# AutoPad-R1-RevA.net
KiCad netlist of a schematic drawn in EAGLE
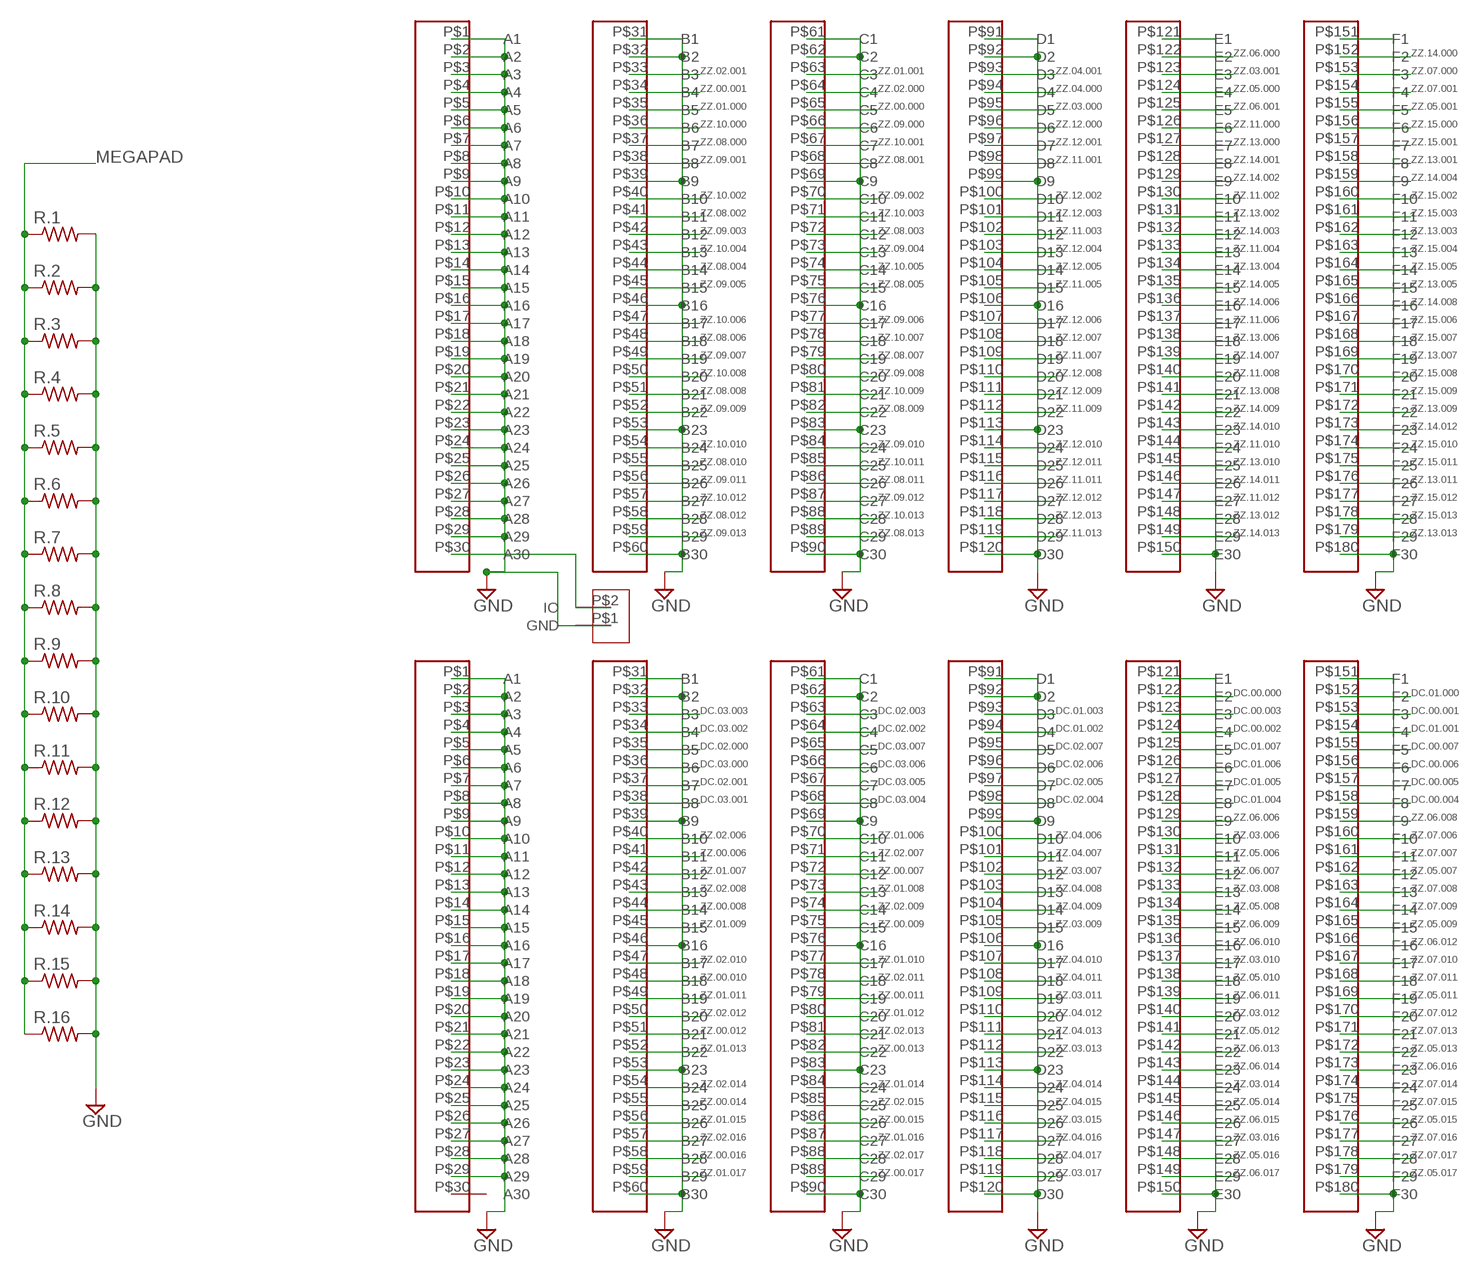
[diagram p0: schematic, sheet 1]
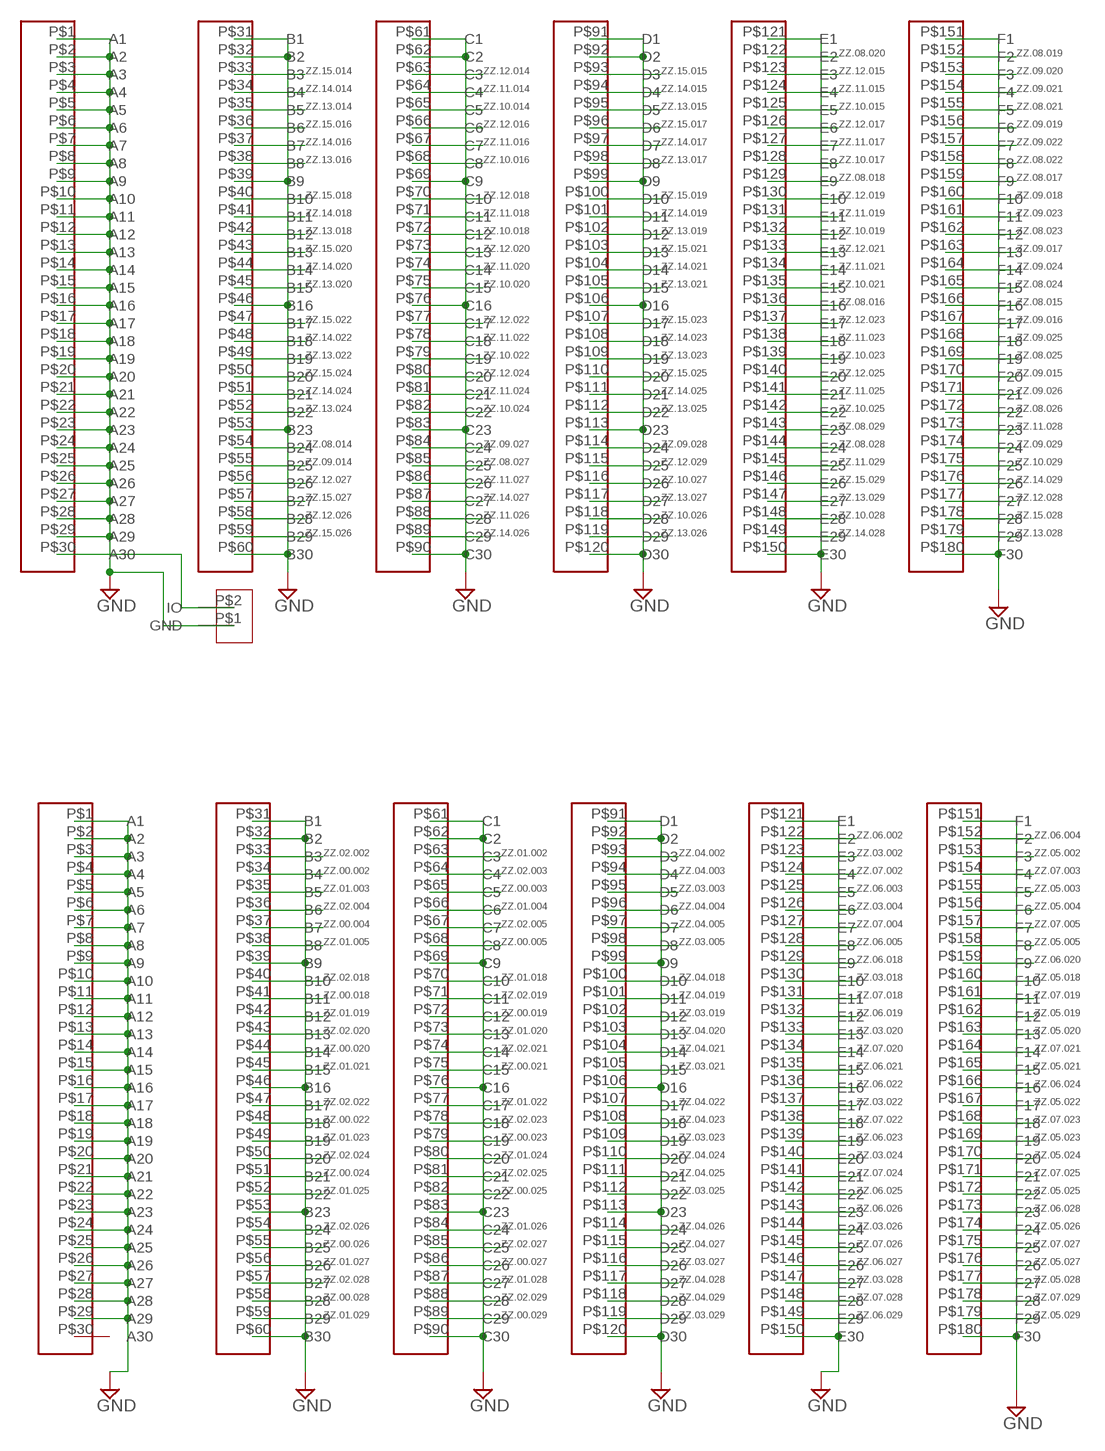
[diagram p1: schematic, sheet 2]
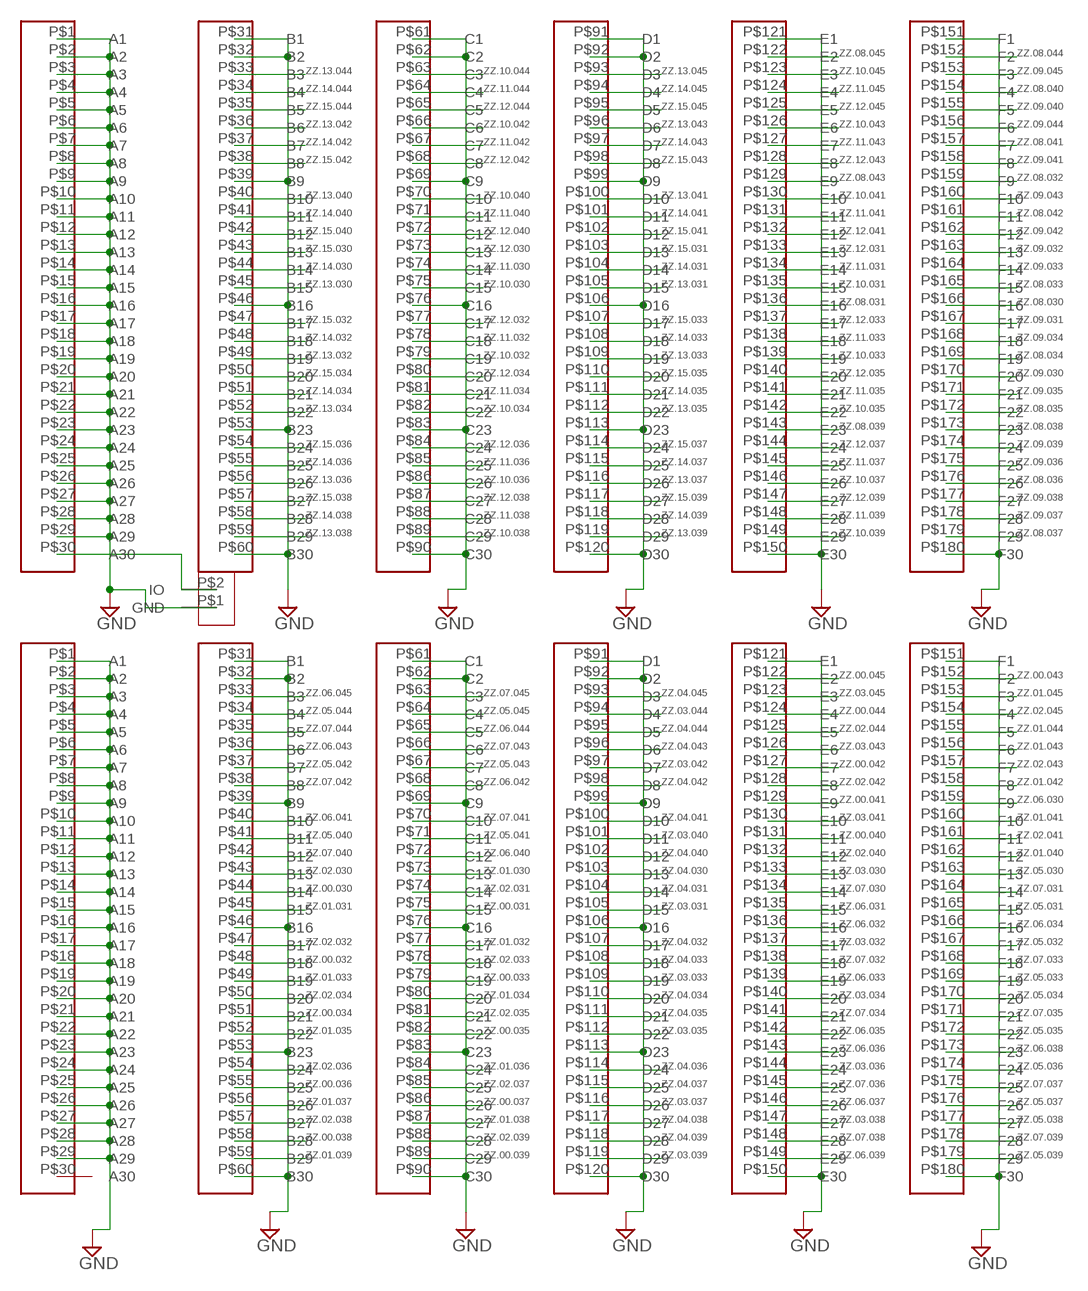
[diagram p2: schematic, sheet 3]
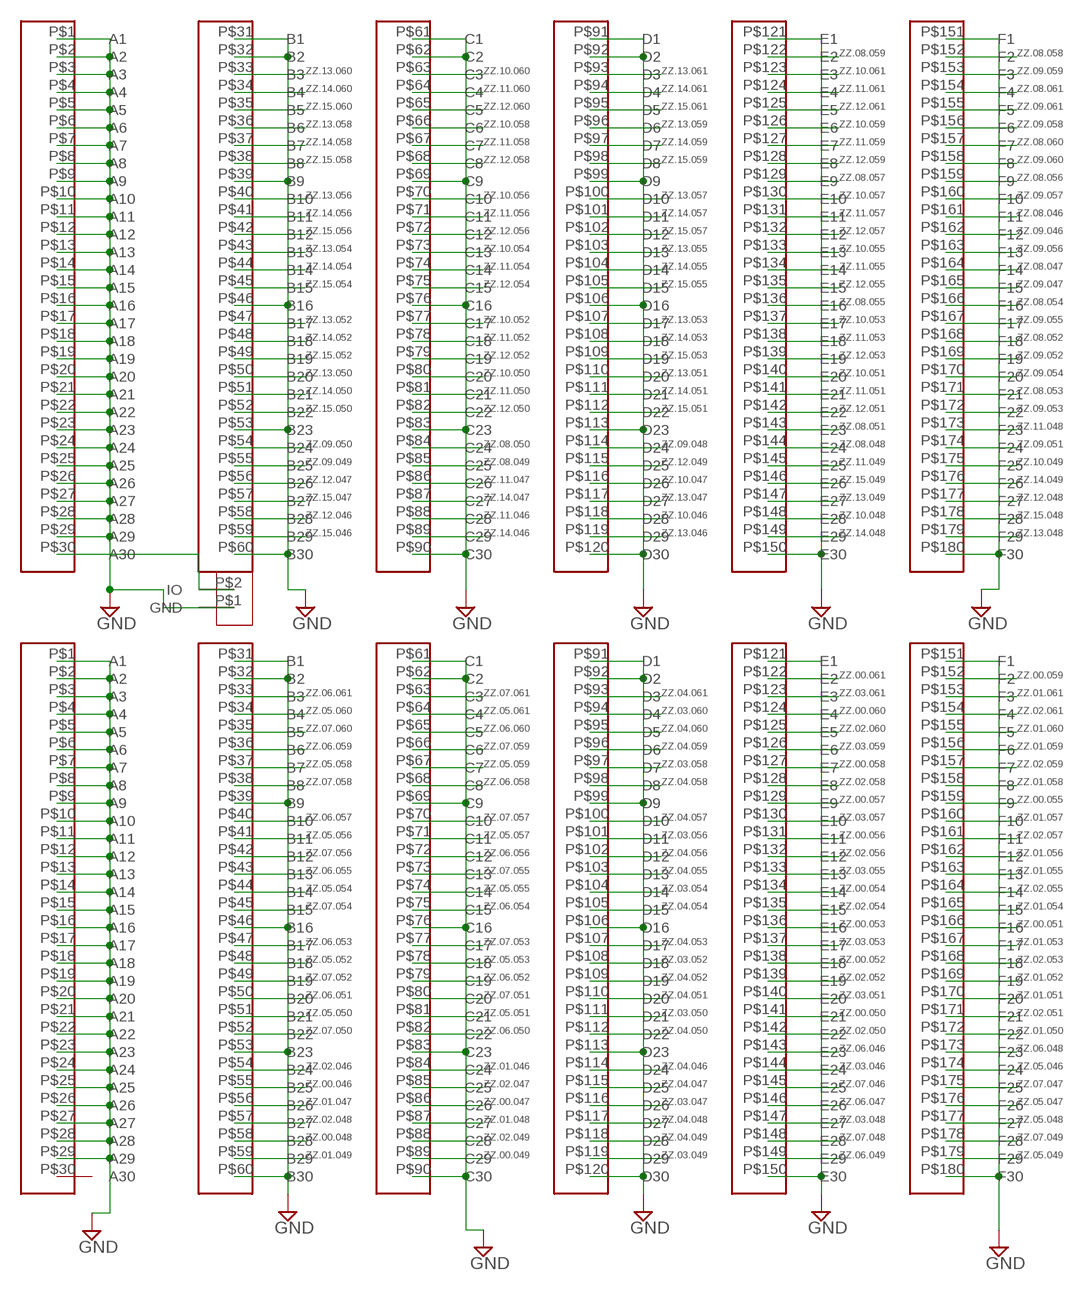
[diagram p3: schematic, sheet 4]
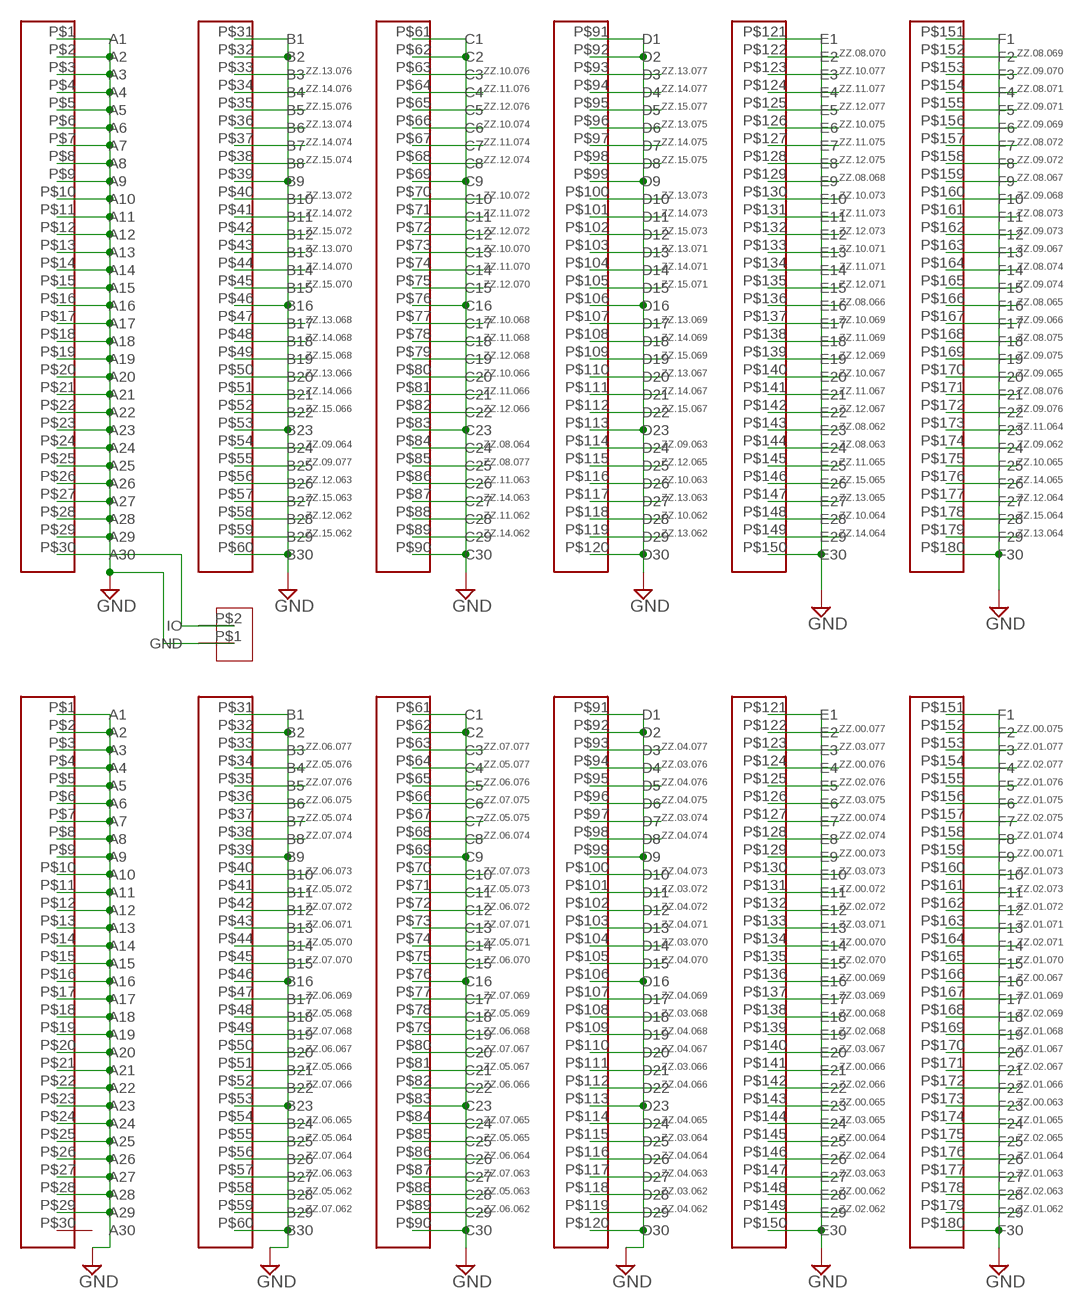
[diagram p4: schematic, sheet 5]
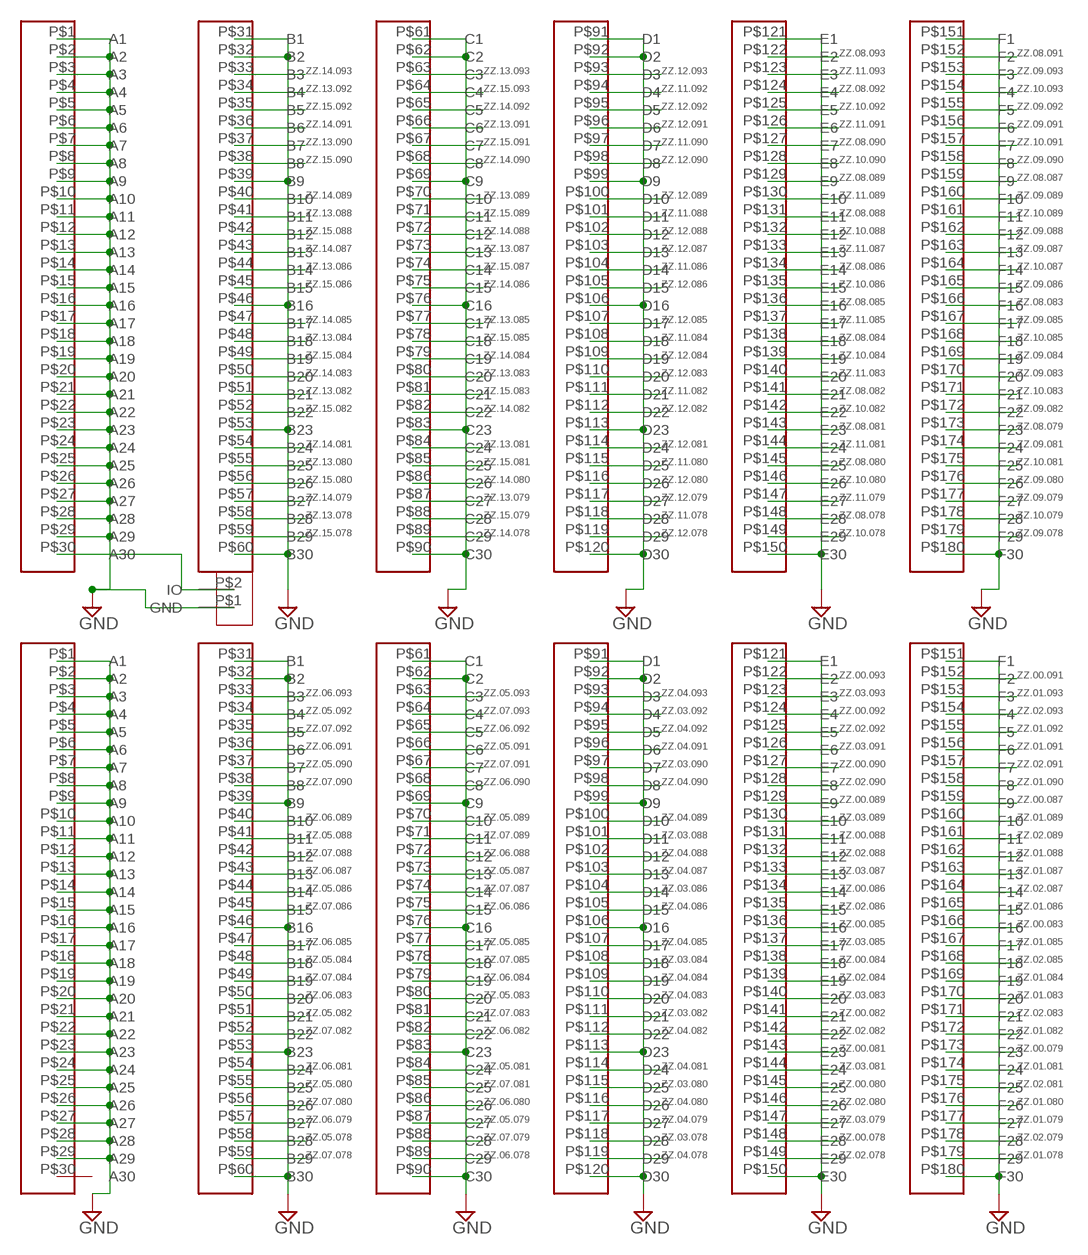
[diagram p5: schematic, sheet 6]

(export (version "E")
  (design (tool "Eeschema 10.0.6"))
  (components
    (comp (ref "U$5")
      (value "SEAM-30-02.0-L-06-1-A-K-TR")
      (footprint "eagle-import:SEAM-30-02.0-L-06-1-A-K-TR")
      (libsource (lib "eagle-import") (part "SEAM-30-02.0-L-06-1-A-K-TR"))
    )
    (comp (ref "U$6")
      (value "SEAM-30-02.0-L-06-1-A-K-TR")
      (footprint "eagle-import:SEAM-30-02.0-L-06-1-A-K-TR")
      (libsource (lib "eagle-import") (part "SEAM-30-02.0-L-06-1-A-K-TR"))
    )
    (comp (ref "U$15")
      (value "DS2431")
      (footprint "eagle-import:SD2431")
      (libsource (lib "eagle-import") (part "DS2431"))
    )
    (comp (ref "R.1")
      (value "R-US_R1206")
      (footprint "eagle-import:R1206")
      (libsource (lib "eagle-import") (part "R-US_R1206"))
    )
    (comp (ref "R.2")
      (value "R-US_R1206")
      (footprint "eagle-import:R1206")
      (libsource (lib "eagle-import") (part "R-US_R1206"))
    )
    (comp (ref "R.3")
      (value "R-US_R1206")
      (footprint "eagle-import:R1206")
      (libsource (lib "eagle-import") (part "R-US_R1206"))
    )
    (comp (ref "R.4")
      (value "R-US_R1206")
      (footprint "eagle-import:R1206")
      (libsource (lib "eagle-import") (part "R-US_R1206"))
    )
    (comp (ref "R.5")
      (value "R-US_R1206")
      (footprint "eagle-import:R1206")
      (libsource (lib "eagle-import") (part "R-US_R1206"))
    )
    (comp (ref "R.6")
      (value "R-US_R1206")
      (footprint "eagle-import:R1206")
      (libsource (lib "eagle-import") (part "R-US_R1206"))
    )
    (comp (ref "R.7")
      (value "R-US_R1206")
      (footprint "eagle-import:R1206")
      (libsource (lib "eagle-import") (part "R-US_R1206"))
    )
    (comp (ref "R.8")
      (value "R-US_R1206")
      (footprint "eagle-import:R1206")
      (libsource (lib "eagle-import") (part "R-US_R1206"))
    )
    (comp (ref "R.9")
      (value "R-US_R1206")
      (footprint "eagle-import:R1206")
      (libsource (lib "eagle-import") (part "R-US_R1206"))
    )
    (comp (ref "R.10")
      (value "R-US_R1206")
      (footprint "eagle-import:R1206")
      (libsource (lib "eagle-import") (part "R-US_R1206"))
    )
    (comp (ref "R.11")
      (value "R-US_R1206")
      (footprint "eagle-import:R1206")
      (libsource (lib "eagle-import") (part "R-US_R1206"))
    )
    (comp (ref "R.12")
      (value "R-US_R1206")
      (footprint "eagle-import:R1206")
      (libsource (lib "eagle-import") (part "R-US_R1206"))
    )
    (comp (ref "R.13")
      (value "R-US_R1206")
      (footprint "eagle-import:R1206")
      (libsource (lib "eagle-import") (part "R-US_R1206"))
    )
    (comp (ref "R.14")
      (value "R-US_R1206")
      (footprint "eagle-import:R1206")
      (libsource (lib "eagle-import") (part "R-US_R1206"))
    )
    (comp (ref "R.15")
      (value "R-US_R1206")
      (footprint "eagle-import:R1206")
      (libsource (lib "eagle-import") (part "R-US_R1206"))
    )
    (comp (ref "R.16")
      (value "R-US_R1206")
      (footprint "eagle-import:R1206")
      (libsource (lib "eagle-import") (part "R-US_R1206"))
    )
    (comp (ref "U$1")
      (value "SEAM-30-02.0-L-06-1-A-K-TR")
      (footprint "eagle-import:SEAM-30-02.0-L-06-1-A-K-TR")
      (libsource (lib "eagle-import") (part "SEAM-30-02.0-L-06-1-A-K-TR"))
    )
    (comp (ref "U$2")
      (value "SEAM-30-02.0-L-06-1-A-K-TR")
      (footprint "eagle-import:SEAM-30-02.0-L-06-1-A-K-TR")
      (libsource (lib "eagle-import") (part "SEAM-30-02.0-L-06-1-A-K-TR"))
    )
    (comp (ref "U$13")
      (value "DS2431")
      (footprint "eagle-import:SD2431")
      (libsource (lib "eagle-import") (part "DS2431"))
    )
    (comp (ref "U$3")
      (value "SEAM-30-02.0-L-06-1-A-K-TR")
      (footprint "eagle-import:SEAM-30-02.0-L-06-1-A-K-TR")
      (libsource (lib "eagle-import") (part "SEAM-30-02.0-L-06-1-A-K-TR"))
    )
    (comp (ref "U$4")
      (value "SEAM-30-02.0-L-06-1-A-K-TR")
      (footprint "eagle-import:SEAM-30-02.0-L-06-1-A-K-TR")
      (libsource (lib "eagle-import") (part "SEAM-30-02.0-L-06-1-A-K-TR"))
    )
    (comp (ref "U$14")
      (value "DS2431")
      (footprint "eagle-import:SD2431")
      (libsource (lib "eagle-import") (part "DS2431"))
    )
    (comp (ref "U$9")
      (value "SEAM-30-02.0-L-06-1-A-K-TR")
      (footprint "eagle-import:SEAM-30-02.0-L-06-1-A-K-TR")
      (libsource (lib "eagle-import") (part "SEAM-30-02.0-L-06-1-A-K-TR"))
    )
    (comp (ref "U$10")
      (value "SEAM-30-02.0-L-06-1-A-K-TR")
      (footprint "eagle-import:SEAM-30-02.0-L-06-1-A-K-TR")
      (libsource (lib "eagle-import") (part "SEAM-30-02.0-L-06-1-A-K-TR"))
    )
    (comp (ref "U$17")
      (value "DS2431")
      (footprint "eagle-import:SD2431")
      (libsource (lib "eagle-import") (part "DS2431"))
    )
    (comp (ref "U$7")
      (value "SEAM-30-02.0-L-06-1-A-K-TR")
      (footprint "eagle-import:SEAM-30-02.0-L-06-1-A-K-TR")
      (libsource (lib "eagle-import") (part "SEAM-30-02.0-L-06-1-A-K-TR"))
    )
    (comp (ref "U$8")
      (value "SEAM-30-02.0-L-06-1-A-K-TR")
      (footprint "eagle-import:SEAM-30-02.0-L-06-1-A-K-TR")
      (libsource (lib "eagle-import") (part "SEAM-30-02.0-L-06-1-A-K-TR"))
    )
    (comp (ref "U$16")
      (value "DS2431")
      (footprint "eagle-import:SD2431")
      (libsource (lib "eagle-import") (part "DS2431"))
    )
    (comp (ref "U$11")
      (value "SEAM-30-02.0-L-06-1-A-K-TR")
      (footprint "eagle-import:SEAM-30-02.0-L-06-1-A-K-TR")
      (libsource (lib "eagle-import") (part "SEAM-30-02.0-L-06-1-A-K-TR"))
    )
    (comp (ref "U$12")
      (value "SEAM-30-02.0-L-06-1-A-K-TR")
      (footprint "eagle-import:SEAM-30-02.0-L-06-1-A-K-TR")
      (libsource (lib "eagle-import") (part "SEAM-30-02.0-L-06-1-A-K-TR"))
    )
    (comp (ref "U$18")
      (value "DS2431")
      (footprint "eagle-import:SD2431")
      (libsource (lib "eagle-import") (part "DS2431"))
    )
  )
  (nets
    (net (code "1") (name "DC.00.000") (class "Default")
      (node (ref "U$2") (pin "P$122") (pinfunction "E2_P$122") (pintype "bidirectional"))
    )
    (net (code "2") (name "DC.00.001") (class "Default")
      (node (ref "U$2") (pin "P$153") (pinfunction "F3_P$153") (pintype "bidirectional"))
    )
    (net (code "3") (name "DC.00.002") (class "Default")
      (node (ref "U$2") (pin "P$124") (pinfunction "E4_P$124") (pintype "bidirectional"))
    )
    (net (code "4") (name "DC.00.003") (class "Default")
      (node (ref "U$2") (pin "P$123") (pinfunction "E3_P$123") (pintype "bidirectional"))
    )
    (net (code "5") (name "DC.00.004") (class "Default")
      (node (ref "U$2") (pin "P$158") (pinfunction "F8_P$158") (pintype "bidirectional"))
    )
    (net (code "6") (name "DC.00.005") (class "Default")
      (node (ref "U$2") (pin "P$157") (pinfunction "F7_P$157") (pintype "bidirectional"))
    )
    (net (code "7") (name "DC.00.006") (class "Default")
      (node (ref "U$2") (pin "P$156") (pinfunction "F6_P$156") (pintype "bidirectional"))
    )
    (net (code "8") (name "DC.00.007") (class "Default")
      (node (ref "U$2") (pin "P$155") (pinfunction "F5_P$155") (pintype "bidirectional"))
    )
    (net (code "9") (name "DC.01.000") (class "Default")
      (node (ref "U$2") (pin "P$152") (pinfunction "F2_P$152") (pintype "bidirectional"))
    )
    (net (code "10") (name "DC.01.001") (class "Default")
      (node (ref "U$2") (pin "P$154") (pinfunction "F4_P$154") (pintype "bidirectional"))
    )
    (net (code "11") (name "DC.01.002") (class "Default")
      (node (ref "U$2") (pin "P$94") (pinfunction "D4_P$94") (pintype "bidirectional"))
    )
    (net (code "12") (name "DC.01.003") (class "Default")
      (node (ref "U$2") (pin "P$93") (pinfunction "D3_P$93") (pintype "bidirectional"))
    )
    (net (code "13") (name "DC.01.004") (class "Default")
      (node (ref "U$2") (pin "P$128") (pinfunction "E8_P$128") (pintype "bidirectional"))
    )
    (net (code "14") (name "DC.01.005") (class "Default")
      (node (ref "U$2") (pin "P$127") (pinfunction "E7_P$127") (pintype "bidirectional"))
    )
    (net (code "15") (name "DC.01.006") (class "Default")
      (node (ref "U$2") (pin "P$126") (pinfunction "E6_P$126") (pintype "bidirectional"))
    )
    (net (code "16") (name "DC.01.007") (class "Default")
      (node (ref "U$2") (pin "P$125") (pinfunction "E5_P$125") (pintype "bidirectional"))
    )
    (net (code "17") (name "DC.02.000") (class "Default")
      (node (ref "U$2") (pin "P$35") (pinfunction "B5_P$35") (pintype "bidirectional"))
    )
    (net (code "18") (name "DC.02.001") (class "Default")
      (node (ref "U$2") (pin "P$37") (pinfunction "B7_P$37") (pintype "bidirectional"))
    )
    (net (code "19") (name "DC.02.002") (class "Default")
      (node (ref "U$2") (pin "P$64") (pinfunction "C4_P$64") (pintype "bidirectional"))
    )
    (net (code "20") (name "DC.02.003") (class "Default")
      (node (ref "U$2") (pin "P$63") (pinfunction "C3_P$63") (pintype "bidirectional"))
    )
    (net (code "21") (name "DC.02.004") (class "Default")
      (node (ref "U$2") (pin "P$98") (pinfunction "D8_P$98") (pintype "bidirectional"))
    )
    (net (code "22") (name "DC.02.005") (class "Default")
      (node (ref "U$2") (pin "P$97") (pinfunction "D7_P$97") (pintype "bidirectional"))
    )
    (net (code "23") (name "DC.02.006") (class "Default")
      (node (ref "U$2") (pin "P$96") (pinfunction "D6_P$96") (pintype "bidirectional"))
    )
    (net (code "24") (name "DC.02.007") (class "Default")
      (node (ref "U$2") (pin "P$95") (pinfunction "D5_P$95") (pintype "bidirectional"))
    )
    (net (code "25") (name "DC.03.000") (class "Default")
      (node (ref "U$2") (pin "P$36") (pinfunction "B6_P$36") (pintype "bidirectional"))
    )
    (net (code "26") (name "DC.03.001") (class "Default")
      (node (ref "U$2") (pin "P$38") (pinfunction "B8_P$38") (pintype "bidirectional"))
    )
    (net (code "27") (name "DC.03.002") (class "Default")
      (node (ref "U$2") (pin "P$34") (pinfunction "B4_P$34") (pintype "bidirectional"))
    )
    (net (code "28") (name "DC.03.003") (class "Default")
      (node (ref "U$2") (pin "P$33") (pinfunction "B3_P$33") (pintype "bidirectional"))
    )
    (net (code "29") (name "DC.03.004") (class "Default")
      (node (ref "U$2") (pin "P$68") (pinfunction "C8_P$68") (pintype "bidirectional"))
    )
    (net (code "30") (name "DC.03.005") (class "Default")
      (node (ref "U$2") (pin "P$67") (pinfunction "C7_P$67") (pintype "bidirectional"))
    )
    (net (code "31") (name "DC.03.006") (class "Default")
      (node (ref "U$2") (pin "P$66") (pinfunction "C6_P$66") (pintype "bidirectional"))
    )
    (net (code "32") (name "DC.03.007") (class "Default")
      (node (ref "U$2") (pin "P$65") (pinfunction "C5_P$65") (pintype "bidirectional"))
    )
    (net (code "33") (name "GND") (class "Default")
      (node (ref "R.1") (pin "2") (pinfunction "2_2") (pintype "passive"))
      (node (ref "R.10") (pin "2") (pinfunction "2_2") (pintype "passive"))
      (node (ref "R.11") (pin "2") (pinfunction "2_2") (pintype "passive"))
      (node (ref "R.12") (pin "2") (pinfunction "2_2") (pintype "passive"))
      (node (ref "R.13") (pin "2") (pinfunction "2_2") (pintype "passive"))
      (node (ref "R.14") (pin "2") (pinfunction "2_2") (pintype "passive"))
      (node (ref "R.15") (pin "2") (pinfunction "2_2") (pintype "passive"))
      (node (ref "R.16") (pin "2") (pinfunction "2_2") (pintype "passive"))
      (node (ref "R.2") (pin "2") (pinfunction "2_2") (pintype "passive"))
      (node (ref "R.3") (pin "2") (pinfunction "2_2") (pintype "passive"))
      (node (ref "R.4") (pin "2") (pinfunction "2_2") (pintype "passive"))
      (node (ref "R.5") (pin "2") (pinfunction "2_2") (pintype "passive"))
      (node (ref "R.6") (pin "2") (pinfunction "2_2") (pintype "passive"))
      (node (ref "R.7") (pin "2") (pinfunction "2_2") (pintype "passive"))
      (node (ref "R.8") (pin "2") (pinfunction "2_2") (pintype "passive"))
      (node (ref "R.9") (pin "2") (pinfunction "2_2") (pintype "passive"))
      (node (ref "U$1") (pin "P$1") (pinfunction "A1_P$1") (pintype "bidirectional"))
      (node (ref "U$1") (pin "P$10") (pinfunction "A10_P$10") (pintype "bidirectional"))
      (node (ref "U$1") (pin "P$106") (pinfunction "D16_P$106") (pintype "bidirectional"))
      (node (ref "U$1") (pin "P$11") (pinfunction "A11_P$11") (pintype "bidirectional"))
      (node (ref "U$1") (pin "P$113") (pinfunction "D23_P$113") (pintype "bidirectional"))
      (node (ref "U$1") (pin "P$12") (pinfunction "A12_P$12") (pintype "bidirectional"))
      (node (ref "U$1") (pin "P$120") (pinfunction "D30_P$120") (pintype "bidirectional"))
      (node (ref "U$1") (pin "P$121") (pinfunction "E1_P$121") (pintype "bidirectional"))
      (node (ref "U$1") (pin "P$13") (pinfunction "A13_P$13") (pintype "bidirectional"))
      (node (ref "U$1") (pin "P$14") (pinfunction "A14_P$14") (pintype "bidirectional"))
      (node (ref "U$1") (pin "P$15") (pinfunction "A15_P$15") (pintype "bidirectional"))
      (node (ref "U$1") (pin "P$150") (pinfunction "E30_P$150") (pintype "bidirectional"))
      (node (ref "U$1") (pin "P$151") (pinfunction "F1_P$151") (pintype "bidirectional"))
      (node (ref "U$1") (pin "P$16") (pinfunction "A16_P$16") (pintype "bidirectional"))
      (node (ref "U$1") (pin "P$17") (pinfunction "A17_P$17") (pintype "bidirectional"))
      (node (ref "U$1") (pin "P$18") (pinfunction "A18_P$18") (pintype "bidirectional"))
      (node (ref "U$1") (pin "P$180") (pinfunction "F30_P$180") (pintype "bidirectional"))
      (node (ref "U$1") (pin "P$19") (pinfunction "A19_P$19") (pintype "bidirectional"))
      (node (ref "U$1") (pin "P$2") (pinfunction "A2_P$2") (pintype "bidirectional"))
      (node (ref "U$1") (pin "P$20") (pinfunction "A20_P$20") (pintype "bidirectional"))
      (node (ref "U$1") (pin "P$21") (pinfunction "A21_P$21") (pintype "bidirectional"))
      (node (ref "U$1") (pin "P$22") (pinfunction "A22_P$22") (pintype "bidirectional"))
      (node (ref "U$1") (pin "P$23") (pinfunction "A23_P$23") (pintype "bidirectional"))
      (node (ref "U$1") (pin "P$24") (pinfunction "A24_P$24") (pintype "bidirectional"))
      (node (ref "U$1") (pin "P$25") (pinfunction "A25_P$25") (pintype "bidirectional"))
      (node (ref "U$1") (pin "P$26") (pinfunction "A26_P$26") (pintype "bidirectional"))
      (node (ref "U$1") (pin "P$27") (pinfunction "A27_P$27") (pintype "bidirectional"))
      (node (ref "U$1") (pin "P$28") (pinfunction "A28_P$28") (pintype "bidirectional"))
      (node (ref "U$1") (pin "P$29") (pinfunction "A29_P$29") (pintype "bidirectional"))
      (node (ref "U$1") (pin "P$3") (pinfunction "A3_P$3") (pintype "bidirectional"))
      (node (ref "U$1") (pin "P$31") (pinfunction "B1_P$31") (pintype "bidirectional"))
      (node (ref "U$1") (pin "P$32") (pinfunction "B2_P$32") (pintype "bidirectional"))
      (node (ref "U$1") (pin "P$39") (pinfunction "B9_P$39") (pintype "bidirectional"))
      (node (ref "U$1") (pin "P$4") (pinfunction "A4_P$4") (pintype "bidirectional"))
      (node (ref "U$1") (pin "P$46") (pinfunction "B16_P$46") (pintype "bidirectional"))
      (node (ref "U$1") (pin "P$5") (pinfunction "A5_P$5") (pintype "bidirectional"))
      (node (ref "U$1") (pin "P$53") (pinfunction "B23_P$53") (pintype "bidirectional"))
      (node (ref "U$1") (pin "P$6") (pinfunction "A6_P$6") (pintype "bidirectional"))
      (node (ref "U$1") (pin "P$60") (pinfunction "B30_P$60") (pintype "bidirectional"))
      (node (ref "U$1") (pin "P$61") (pinfunction "C1_P$61") (pintype "bidirectional"))
      (node (ref "U$1") (pin "P$62") (pinfunction "C2_P$62") (pintype "bidirectional"))
      (node (ref "U$1") (pin "P$69") (pinfunction "C9_P$69") (pintype "bidirectional"))
      (node (ref "U$1") (pin "P$7") (pinfunction "A7_P$7") (pintype "bidirectional"))
      (node (ref "U$1") (pin "P$76") (pinfunction "C16_P$76") (pintype "bidirectional"))
      (node (ref "U$1") (pin "P$8") (pinfunction "A8_P$8") (pintype "bidirectional"))
      (node (ref "U$1") (pin "P$83") (pinfunction "C23_P$83") (pintype "bidirectional"))
      (node (ref "U$1") (pin "P$9") (pinfunction "A9_P$9") (pintype "bidirectional"))
      (node (ref "U$1") (pin "P$90") (pinfunction "C30_P$90") (pintype "bidirectional"))
      (node (ref "U$1") (pin "P$91") (pinfunction "D1_P$91") (pintype "bidirectional"))
      (node (ref "U$1") (pin "P$92") (pinfunction "D2_P$92") (pintype "bidirectional"))
      (node (ref "U$1") (pin "P$99") (pinfunction "D9_P$99") (pintype "bidirectional"))
      (node (ref "U$10") (pin "P$1") (pinfunction "A1_P$1") (pintype "bidirectional"))
      (node (ref "U$10") (pin "P$10") (pinfunction "A10_P$10") (pintype "bidirectional"))
      (node (ref "U$10") (pin "P$106") (pinfunction "D16_P$106") (pintype "bidirectional"))
      (node (ref "U$10") (pin "P$11") (pinfunction "A11_P$11") (pintype "bidirectional"))
      (node (ref "U$10") (pin "P$113") (pinfunction "D23_P$113") (pintype "bidirectional"))
      (node (ref "U$10") (pin "P$12") (pinfunction "A12_P$12") (pintype "bidirectional"))
      (node (ref "U$10") (pin "P$120") (pinfunction "D30_P$120") (pintype "bidirectional"))
      (node (ref "U$10") (pin "P$121") (pinfunction "E1_P$121") (pintype "bidirectional"))
      (node (ref "U$10") (pin "P$13") (pinfunction "A13_P$13") (pintype "bidirectional"))
      (node (ref "U$10") (pin "P$14") (pinfunction "A14_P$14") (pintype "bidirectional"))
      (node (ref "U$10") (pin "P$15") (pinfunction "A15_P$15") (pintype "bidirectional"))
      (node (ref "U$10") (pin "P$150") (pinfunction "E30_P$150") (pintype "bidirectional"))
      (node (ref "U$10") (pin "P$151") (pinfunction "F1_P$151") (pintype "bidirectional"))
      (node (ref "U$10") (pin "P$16") (pinfunction "A16_P$16") (pintype "bidirectional"))
      (node (ref "U$10") (pin "P$17") (pinfunction "A17_P$17") (pintype "bidirectional"))
      (node (ref "U$10") (pin "P$18") (pinfunction "A18_P$18") (pintype "bidirectional"))
      (node (ref "U$10") (pin "P$180") (pinfunction "F30_P$180") (pintype "bidirectional"))
      (node (ref "U$10") (pin "P$19") (pinfunction "A19_P$19") (pintype "bidirectional"))
      (node (ref "U$10") (pin "P$2") (pinfunction "A2_P$2") (pintype "bidirectional"))
      (node (ref "U$10") (pin "P$20") (pinfunction "A20_P$20") (pintype "bidirectional"))
      (node (ref "U$10") (pin "P$21") (pinfunction "A21_P$21") (pintype "bidirectional"))
      (node (ref "U$10") (pin "P$22") (pinfunction "A22_P$22") (pintype "bidirectional"))
      (node (ref "U$10") (pin "P$23") (pinfunction "A23_P$23") (pintype "bidirectional"))
      (node (ref "U$10") (pin "P$24") (pinfunction "A24_P$24") (pintype "bidirectional"))
      (node (ref "U$10") (pin "P$25") (pinfunction "A25_P$25") (pintype "bidirectional"))
      (node (ref "U$10") (pin "P$26") (pinfunction "A26_P$26") (pintype "bidirectional"))
      (node (ref "U$10") (pin "P$27") (pinfunction "A27_P$27") (pintype "bidirectional"))
      (node (ref "U$10") (pin "P$28") (pinfunction "A28_P$28") (pintype "bidirectional"))
      (node (ref "U$10") (pin "P$29") (pinfunction "A29_P$29") (pintype "bidirectional"))
      (node (ref "U$10") (pin "P$3") (pinfunction "A3_P$3") (pintype "bidirectional"))
      (node (ref "U$10") (pin "P$31") (pinfunction "B1_P$31") (pintype "bidirectional"))
      (node (ref "U$10") (pin "P$32") (pinfunction "B2_P$32") (pintype "bidirectional"))
      (node (ref "U$10") (pin "P$39") (pinfunction "B9_P$39") (pintype "bidirectional"))
      (node (ref "U$10") (pin "P$4") (pinfunction "A4_P$4") (pintype "bidirectional"))
      (node (ref "U$10") (pin "P$46") (pinfunction "B16_P$46") (pintype "bidirectional"))
      (node (ref "U$10") (pin "P$5") (pinfunction "A5_P$5") (pintype "bidirectional"))
      (node (ref "U$10") (pin "P$53") (pinfunction "B23_P$53") (pintype "bidirectional"))
      (node (ref "U$10") (pin "P$6") (pinfunction "A6_P$6") (pintype "bidirectional"))
      (node (ref "U$10") (pin "P$60") (pinfunction "B30_P$60") (pintype "bidirectional"))
      (node (ref "U$10") (pin "P$61") (pinfunction "C1_P$61") (pintype "bidirectional"))
      (node (ref "U$10") (pin "P$62") (pinfunction "C2_P$62") (pintype "bidirectional"))
      (node (ref "U$10") (pin "P$69") (pinfunction "C9_P$69") (pintype "bidirectional"))
      (node (ref "U$10") (pin "P$7") (pinfunction "A7_P$7") (pintype "bidirectional"))
      (node (ref "U$10") (pin "P$76") (pinfunction "C16_P$76") (pintype "bidirectional"))
      (node (ref "U$10") (pin "P$8") (pinfunction "A8_P$8") (pintype "bidirectional"))
      (node (ref "U$10") (pin "P$83") (pinfunction "C23_P$83") (pintype "bidirectional"))
      (node (ref "U$10") (pin "P$9") (pinfunction "A9_P$9") (pintype "bidirectional"))
      (node (ref "U$10") (pin "P$90") (pinfunction "C30_P$90") (pintype "bidirectional"))
      (node (ref "U$10") (pin "P$91") (pinfunction "D1_P$91") (pintype "bidirectional"))
      (node (ref "U$10") (pin "P$92") (pinfunction "D2_P$92") (pintype "bidirectional"))
      (node (ref "U$10") (pin "P$99") (pinfunction "D9_P$99") (pintype "bidirectional"))
      (node (ref "U$11") (pin "P$1") (pinfunction "A1_P$1") (pintype "bidirectional"))
      (node (ref "U$11") (pin "P$10") (pinfunction "A10_P$10") (pintype "bidirectional"))
      (node (ref "U$11") (pin "P$106") (pinfunction "D16_P$106") (pintype "bidirectional"))
      (node (ref "U$11") (pin "P$11") (pinfunction "A11_P$11") (pintype "bidirectional"))
      (node (ref "U$11") (pin "P$113") (pinfunction "D23_P$113") (pintype "bidirectional"))
      (node (ref "U$11") (pin "P$12") (pinfunction "A12_P$12") (pintype "bidirectional"))
      (node (ref "U$11") (pin "P$120") (pinfunction "D30_P$120") (pintype "bidirectional"))
      (node (ref "U$11") (pin "P$121") (pinfunction "E1_P$121") (pintype "bidirectional"))
      (node (ref "U$11") (pin "P$13") (pinfunction "A13_P$13") (pintype "bidirectional"))
      (node (ref "U$11") (pin "P$14") (pinfunction "A14_P$14") (pintype "bidirectional"))
      (node (ref "U$11") (pin "P$15") (pinfunction "A15_P$15") (pintype "bidirectional"))
      (node (ref "U$11") (pin "P$150") (pinfunction "E30_P$150") (pintype "bidirectional"))
      (node (ref "U$11") (pin "P$151") (pinfunction "F1_P$151") (pintype "bidirectional"))
      (node (ref "U$11") (pin "P$16") (pinfunction "A16_P$16") (pintype "bidirectional"))
      (node (ref "U$11") (pin "P$17") (pinfunction "A17_P$17") (pintype "bidirectional"))
      (node (ref "U$11") (pin "P$18") (pinfunction "A18_P$18") (pintype "bidirectional"))
      (node (ref "U$11") (pin "P$180") (pinfunction "F30_P$180") (pintype "bidirectional"))
      (node (ref "U$11") (pin "P$19") (pinfunction "A19_P$19") (pintype "bidirectional"))
      (node (ref "U$11") (pin "P$2") (pinfunction "A2_P$2") (pintype "bidirectional"))
      (node (ref "U$11") (pin "P$20") (pinfunction "A20_P$20") (pintype "bidirectional"))
      (node (ref "U$11") (pin "P$21") (pinfunction "A21_P$21") (pintype "bidirectional"))
      (node (ref "U$11") (pin "P$22") (pinfunction "A22_P$22") (pintype "bidirectional"))
      (node (ref "U$11") (pin "P$23") (pinfunction "A23_P$23") (pintype "bidirectional"))
      (node (ref "U$11") (pin "P$24") (pinfunction "A24_P$24") (pintype "bidirectional"))
      (node (ref "U$11") (pin "P$25") (pinfunction "A25_P$25") (pintype "bidirectional"))
      (node (ref "U$11") (pin "P$26") (pinfunction "A26_P$26") (pintype "bidirectional"))
      (node (ref "U$11") (pin "P$27") (pinfunction "A27_P$27") (pintype "bidirectional"))
      (node (ref "U$11") (pin "P$28") (pinfunction "A28_P$28") (pintype "bidirectional"))
      (node (ref "U$11") (pin "P$29") (pinfunction "A29_P$29") (pintype "bidirectional"))
      (node (ref "U$11") (pin "P$3") (pinfunction "A3_P$3") (pintype "bidirectional"))
      (node (ref "U$11") (pin "P$31") (pinfunction "B1_P$31") (pintype "bidirectional"))
      (node (ref "U$11") (pin "P$32") (pinfunction "B2_P$32") (pintype "bidirectional"))
      (node (ref "U$11") (pin "P$39") (pinfunction "B9_P$39") (pintype "bidirectional"))
      (node (ref "U$11") (pin "P$4") (pinfunction "A4_P$4") (pintype "bidirectional"))
      (node (ref "U$11") (pin "P$46") (pinfunction "B16_P$46") (pintype "bidirectional"))
      (node (ref "U$11") (pin "P$5") (pinfunction "A5_P$5") (pintype "bidirectional"))
      (node (ref "U$11") (pin "P$53") (pinfunction "B23_P$53") (pintype "bidirectional"))
      (node (ref "U$11") (pin "P$6") (pinfunction "A6_P$6") (pintype "bidirectional"))
      (node (ref "U$11") (pin "P$60") (pinfunction "B30_P$60") (pintype "bidirectional"))
      (node (ref "U$11") (pin "P$61") (pinfunction "C1_P$61") (pintype "bidirectional"))
      (node (ref "U$11") (pin "P$62") (pinfunction "C2_P$62") (pintype "bidirectional"))
      (node (ref "U$11") (pin "P$69") (pinfunction "C9_P$69") (pintype "bidirectional"))
      (node (ref "U$11") (pin "P$7") (pinfunction "A7_P$7") (pintype "bidirectional"))
      (node (ref "U$11") (pin "P$76") (pinfunction "C16_P$76") (pintype "bidirectional"))
      (node (ref "U$11") (pin "P$8") (pinfunction "A8_P$8") (pintype "bidirectional"))
      (node (ref "U$11") (pin "P$83") (pinfunction "C23_P$83") (pintype "bidirectional"))
      (node (ref "U$11") (pin "P$9") (pinfunction "A9_P$9") (pintype "bidirectional"))
      (node (ref "U$11") (pin "P$90") (pinfunction "C30_P$90") (pintype "bidirectional"))
      (node (ref "U$11") (pin "P$91") (pinfunction "D1_P$91") (pintype "bidirectional"))
      (node (ref "U$11") (pin "P$92") (pinfunction "D2_P$92") (pintype "bidirectional"))
      (node (ref "U$11") (pin "P$99") (pinfunction "D9_P$99") (pintype "bidirectional"))
      (node (ref "U$12") (pin "P$1") (pinfunction "A1_P$1") (pintype "bidirectional"))
      (node (ref "U$12") (pin "P$10") (pinfunction "A10_P$10") (pintype "bidirectional"))
      (node (ref "U$12") (pin "P$106") (pinfunction "D16_P$106") (pintype "bidirectional"))
      (node (ref "U$12") (pin "P$11") (pinfunction "A11_P$11") (pintype "bidirectional"))
      (node (ref "U$12") (pin "P$113") (pinfunction "D23_P$113") (pintype "bidirectional"))
      (node (ref "U$12") (pin "P$12") (pinfunction "A12_P$12") (pintype "bidirectional"))
      (node (ref "U$12") (pin "P$120") (pinfunction "D30_P$120") (pintype "bidirectional"))
      (node (ref "U$12") (pin "P$121") (pinfunction "E1_P$121") (pintype "bidirectional"))
      (node (ref "U$12") (pin "P$13") (pinfunction "A13_P$13") (pintype "bidirectional"))
      (node (ref "U$12") (pin "P$14") (pinfunction "A14_P$14") (pintype "bidirectional"))
      (node (ref "U$12") (pin "P$15") (pinfunction "A15_P$15") (pintype "bidirectional"))
      (node (ref "U$12") (pin "P$150") (pinfunction "E30_P$150") (pintype "bidirectional"))
      (node (ref "U$12") (pin "P$151") (pinfunction "F1_P$151") (pintype "bidirectional"))
      (node (ref "U$12") (pin "P$16") (pinfunction "A16_P$16") (pintype "bidirectional"))
      (node (ref "U$12") (pin "P$17") (pinfunction "A17_P$17") (pintype "bidirectional"))
      (node (ref "U$12") (pin "P$18") (pinfunction "A18_P$18") (pintype "bidirectional"))
      (node (ref "U$12") (pin "P$180") (pinfunction "F30_P$180") (pintype "bidirectional"))
      (node (ref "U$12") (pin "P$19") (pinfunction "A19_P$19") (pintype "bidirectional"))
      (node (ref "U$12") (pin "P$2") (pinfunction "A2_P$2") (pintype "bidirectional"))
      (node (ref "U$12") (pin "P$20") (pinfunction "A20_P$20") (pintype "bidirectional"))
      (node (ref "U$12") (pin "P$21") (pinfunction "A21_P$21") (pintype "bidirectional"))
      (node (ref "U$12") (pin "P$22") (pinfunction "A22_P$22") (pintype "bidirectional"))
      (node (ref "U$12") (pin "P$23") (pinfunction "A23_P$23") (pintype "bidirectional"))
      (node (ref "U$12") (pin "P$24") (pinfunction "A24_P$24") (pintype "bidirectional"))
      (node (ref "U$12") (pin "P$25") (pinfunction "A25_P$25") (pintype "bidirectional"))
      (node (ref "U$12") (pin "P$26") (pinfunction "A26_P$26") (pintype "bidirectional"))
      (node (ref "U$12") (pin "P$27") (pinfunction "A27_P$27") (pintype "bidirectional"))
      (node (ref "U$12") (pin "P$28") (pinfunction "A28_P$28") (pintype "bidirectional"))
      (node (ref "U$12") (pin "P$29") (pinfunction "A29_P$29") (pintype "bidirectional"))
      (node (ref "U$12") (pin "P$3") (pinfunction "A3_P$3") (pintype "bidirectional"))
      (node (ref "U$12") (pin "P$31") (pinfunction "B1_P$31") (pintype "bidirectional"))
      (node (ref "U$12") (pin "P$32") (pinfunction "B2_P$32") (pintype "bidirectional"))
      (node (ref "U$12") (pin "P$39") (pinfunction "B9_P$39") (pintype "bidirectional"))
      (node (ref "U$12") (pin "P$4") (pinfunction "A4_P$4") (pintype "bidirectional"))
      (node (ref "U$12") (pin "P$46") (pinfunction "B16_P$46") (pintype "bidirectional"))
      (node (ref "U$12") (pin "P$5") (pinfunction "A5_P$5") (pintype "bidirectional"))
      (node (ref "U$12") (pin "P$53") (pinfunction "B23_P$53") (pintype "bidirectional"))
      (node (ref "U$12") (pin "P$6") (pinfunction "A6_P$6") (pintype "bidirectional"))
      (node (ref "U$12") (pin "P$60") (pinfunction "B30_P$60") (pintype "bidirectional"))
      (node (ref "U$12") (pin "P$61") (pinfunction "C1_P$61") (pintype "bidirectional"))
      (node (ref "U$12") (pin "P$62") (pinfunction "C2_P$62") (pintype "bidirectional"))
      (node (ref "U$12") (pin "P$69") (pinfunction "C9_P$69") (pintype "bidirectional"))
      (node (ref "U$12") (pin "P$7") (pinfunction "A7_P$7") (pintype "bidirectional"))
      (node (ref "U$12") (pin "P$76") (pinfunction "C16_P$76") (pintype "bidirectional"))
      (node (ref "U$12") (pin "P$8") (pinfunction "A8_P$8") (pintype "bidirectional"))
      (node (ref "U$12") (pin "P$83") (pinfunction "C23_P$83") (pintype "bidirectional"))
      (node (ref "U$12") (pin "P$9") (pinfunction "A9_P$9") (pintype "bidirectional"))
      (node (ref "U$12") (pin "P$90") (pinfunction "C30_P$90") (pintype "bidirectional"))
      (node (ref "U$12") (pin "P$91") (pinfunction "D1_P$91") (pintype "bidirectional"))
      (node (ref "U$12") (pin "P$92") (pinfunction "D2_P$92") (pintype "bidirectional"))
      (node (ref "U$12") (pin "P$99") (pinfunction "D9_P$99") (pintype "bidirectional"))
      (node (ref "U$13") (pin "P$1") (pinfunction "GND_P$1") (pintype "bidirectional"))
      (node (ref "U$14") (pin "P$1") (pinfunction "GND_P$1") (pintype "bidirectional"))
      (node (ref "U$15") (pin "P$1") (pinfunction "GND_P$1") (pintype "bidirectional"))
      (node (ref "U$16") (pin "P$1") (pinfunction "GND_P$1") (pintype "bidirectional"))
      (node (ref "U$17") (pin "P$1") (pinfunction "GND_P$1") (pintype "bidirectional"))
      (node (ref "U$18") (pin "P$1") (pinfunction "GND_P$1") (pintype "bidirectional"))
      (node (ref "U$2") (pin "P$1") (pinfunction "A1_P$1") (pintype "bidirectional"))
      (node (ref "U$2") (pin "P$10") (pinfunction "A10_P$10") (pintype "bidirectional"))
      (node (ref "U$2") (pin "P$106") (pinfunction "D16_P$106") (pintype "bidirectional"))
      (node (ref "U$2") (pin "P$11") (pinfunction "A11_P$11") (pintype "bidirectional"))
      (node (ref "U$2") (pin "P$113") (pinfunction "D23_P$113") (pintype "bidirectional"))
      (node (ref "U$2") (pin "P$12") (pinfunction "A12_P$12") (pintype "bidirectional"))
      (node (ref "U$2") (pin "P$120") (pinfunction "D30_P$120") (pintype "bidirectional"))
      (node (ref "U$2") (pin "P$121") (pinfunction "E1_P$121") (pintype "bidirectional"))
      (node (ref "U$2") (pin "P$13") (pinfunction "A13_P$13") (pintype "bidirectional"))
      (node (ref "U$2") (pin "P$14") (pinfunction "A14_P$14") (pintype "bidirectional"))
      (node (ref "U$2") (pin "P$15") (pinfunction "A15_P$15") (pintype "bidirectional"))
      (node (ref "U$2") (pin "P$150") (pinfunction "E30_P$150") (pintype "bidirectional"))
      (node (ref "U$2") (pin "P$151") (pinfunction "F1_P$151") (pintype "bidirectional"))
      (node (ref "U$2") (pin "P$16") (pinfunction "A16_P$16") (pintype "bidirectional"))
      (node (ref "U$2") (pin "P$17") (pinfunction "A17_P$17") (pintype "bidirectional"))
      (node (ref "U$2") (pin "P$18") (pinfunction "A18_P$18") (pintype "bidirectional"))
      (node (ref "U$2") (pin "P$180") (pinfunction "F30_P$180") (pintype "bidirectional"))
      (node (ref "U$2") (pin "P$19") (pinfunction "A19_P$19") (pintype "bidirectional"))
      (node (ref "U$2") (pin "P$2") (pinfunction "A2_P$2") (pintype "bidirectional"))
      (node (ref "U$2") (pin "P$20") (pinfunction "A20_P$20") (pintype "bidirectional"))
      (node (ref "U$2") (pin "P$21") (pinfunction "A21_P$21") (pintype "bidirectional"))
      (node (ref "U$2") (pin "P$22") (pinfunction "A22_P$22") (pintype "bidirectional"))
      (node (ref "U$2") (pin "P$23") (pinfunction "A23_P$23") (pintype "bidirectional"))
      (node (ref "U$2") (pin "P$24") (pinfunction "A24_P$24") (pintype "bidirectional"))
      (node (ref "U$2") (pin "P$25") (pinfunction "A25_P$25") (pintype "bidirectional"))
      (node (ref "U$2") (pin "P$26") (pinfunction "A26_P$26") (pintype "bidirectional"))
      (node (ref "U$2") (pin "P$27") (pinfunction "A27_P$27") (pintype "bidirectional"))
      (node (ref "U$2") (pin "P$28") (pinfunction "A28_P$28") (pintype "bidirectional"))
      (node (ref "U$2") (pin "P$29") (pinfunction "A29_P$29") (pintype "bidirectional"))
      (node (ref "U$2") (pin "P$3") (pinfunction "A3_P$3") (pintype "bidirectional"))
      (node (ref "U$2") (pin "P$31") (pinfunction "B1_P$31") (pintype "bidirectional"))
      (node (ref "U$2") (pin "P$32") (pinfunction "B2_P$32") (pintype "bidirectional"))
      (node (ref "U$2") (pin "P$39") (pinfunction "B9_P$39") (pintype "bidirectional"))
      (node (ref "U$2") (pin "P$4") (pinfunction "A4_P$4") (pintype "bidirectional"))
      (node (ref "U$2") (pin "P$46") (pinfunction "B16_P$46") (pintype "bidirectional"))
      (node (ref "U$2") (pin "P$5") (pinfunction "A5_P$5") (pintype "bidirectional"))
      (node (ref "U$2") (pin "P$53") (pinfunction "B23_P$53") (pintype "bidirectional"))
      (node (ref "U$2") (pin "P$6") (pinfunction "A6_P$6") (pintype "bidirectional"))
      (node (ref "U$2") (pin "P$60") (pinfunction "B30_P$60") (pintype "bidirectional"))
      (node (ref "U$2") (pin "P$61") (pinfunction "C1_P$61") (pintype "bidirectional"))
      (node (ref "U$2") (pin "P$62") (pinfunction "C2_P$62") (pintype "bidirectional"))
      (node (ref "U$2") (pin "P$69") (pinfunction "C9_P$69") (pintype "bidirectional"))
      (node (ref "U$2") (pin "P$7") (pinfunction "A7_P$7") (pintype "bidirectional"))
      (node (ref "U$2") (pin "P$76") (pinfunction "C16_P$76") (pintype "bidirectional"))
      (node (ref "U$2") (pin "P$8") (pinfunction "A8_P$8") (pintype "bidirectional"))
      (node (ref "U$2") (pin "P$83") (pinfunction "C23_P$83") (pintype "bidirectional"))
      (node (ref "U$2") (pin "P$9") (pinfunction "A9_P$9") (pintype "bidirectional"))
      (node (ref "U$2") (pin "P$90") (pinfunction "C30_P$90") (pintype "bidirectional"))
      (node (ref "U$2") (pin "P$91") (pinfunction "D1_P$91") (pintype "bidirectional"))
      (node (ref "U$2") (pin "P$92") (pinfunction "D2_P$92") (pintype "bidirectional"))
      (node (ref "U$2") (pin "P$99") (pinfunction "D9_P$99") (pintype "bidirectional"))
      (node (ref "U$3") (pin "P$1") (pinfunction "A1_P$1") (pintype "bidirectional"))
      (node (ref "U$3") (pin "P$10") (pinfunction "A10_P$10") (pintype "bidirectional"))
      (node (ref "U$3") (pin "P$106") (pinfunction "D16_P$106") (pintype "bidirectional"))
      (node (ref "U$3") (pin "P$11") (pinfunction "A11_P$11") (pintype "bidirectional"))
      (node (ref "U$3") (pin "P$113") (pinfunction "D23_P$113") (pintype "bidirectional"))
      (node (ref "U$3") (pin "P$12") (pinfunction "A12_P$12") (pintype "bidirectional"))
      (node (ref "U$3") (pin "P$120") (pinfunction "D30_P$120") (pintype "bidirectional"))
      (node (ref "U$3") (pin "P$121") (pinfunction "E1_P$121") (pintype "bidirectional"))
      (node (ref "U$3") (pin "P$13") (pinfunction "A13_P$13") (pintype "bidirectional"))
      (node (ref "U$3") (pin "P$14") (pinfunction "A14_P$14") (pintype "bidirectional"))
      (node (ref "U$3") (pin "P$15") (pinfunction "A15_P$15") (pintype "bidirectional"))
      (node (ref "U$3") (pin "P$150") (pinfunction "E30_P$150") (pintype "bidirectional"))
      (node (ref "U$3") (pin "P$151") (pinfunction "F1_P$151") (pintype "bidirectional"))
      (node (ref "U$3") (pin "P$16") (pinfunction "A16_P$16") (pintype "bidirectional"))
      (node (ref "U$3") (pin "P$17") (pinfunction "A17_P$17") (pintype "bidirectional"))
      (node (ref "U$3") (pin "P$18") (pinfunction "A18_P$18") (pintype "bidirectional"))
      (node (ref "U$3") (pin "P$180") (pinfunction "F30_P$180") (pintype "bidirectional"))
      (node (ref "U$3") (pin "P$19") (pinfunction "A19_P$19") (pintype "bidirectional"))
      (node (ref "U$3") (pin "P$2") (pinfunction "A2_P$2") (pintype "bidirectional"))
      (node (ref "U$3") (pin "P$20") (pinfunction "A20_P$20") (pintype "bidirectional"))
      (node (ref "U$3") (pin "P$21") (pinfunction "A21_P$21") (pintype "bidirectional"))
      (node (ref "U$3") (pin "P$22") (pinfunction "A22_P$22") (pintype "bidirectional"))
      (node (ref "U$3") (pin "P$23") (pinfunction "A23_P$23") (pintype "bidirectional"))
      (node (ref "U$3") (pin "P$24") (pinfunction "A24_P$24") (pintype "bidirectional"))
      (node (ref "U$3") (pin "P$25") (pinfunction "A25_P$25") (pintype "bidirectional"))
      (node (ref "U$3") (pin "P$26") (pinfunction "A26_P$26") (pintype "bidirectional"))
      (node (ref "U$3") (pin "P$27") (pinfunction "A27_P$27") (pintype "bidirectional"))
      (node (ref "U$3") (pin "P$28") (pinfunction "A28_P$28") (pintype "bidirectional"))
      (node (ref "U$3") (pin "P$29") (pinfunction "A29_P$29") (pintype "bidirectional"))
      (node (ref "U$3") (pin "P$3") (pinfunction "A3_P$3") (pintype "bidirectional"))
      (node (ref "U$3") (pin "P$31") (pinfunction "B1_P$31") (pintype "bidirectional"))
      (node (ref "U$3") (pin "P$32") (pinfunction "B2_P$32") (pintype "bidirectional"))
      (node (ref "U$3") (pin "P$39") (pinfunction "B9_P$39") (pintype "bidirectional"))
      (node (ref "U$3") (pin "P$4") (pinfunction "A4_P$4") (pintype "bidirectional"))
      (node (ref "U$3") (pin "P$46") (pinfunction "B16_P$46") (pintype "bidirectional"))
      (node (ref "U$3") (pin "P$5") (pinfunction "A5_P$5") (pintype "bidirectional"))
      (node (ref "U$3") (pin "P$53") (pinfunction "B23_P$53") (pintype "bidirectional"))
      (node (ref "U$3") (pin "P$6") (pinfunction "A6_P$6") (pintype "bidirectional"))
      (node (ref "U$3") (pin "P$60") (pinfunction "B30_P$60") (pintype "bidirectional"))
      (node (ref "U$3") (pin "P$61") (pinfunction "C1_P$61") (pintype "bidirectional"))
      (node (ref "U$3") (pin "P$62") (pinfunction "C2_P$62") (pintype "bidirectional"))
      (node (ref "U$3") (pin "P$69") (pinfunction "C9_P$69") (pintype "bidirectional"))
      (node (ref "U$3") (pin "P$7") (pinfunction "A7_P$7") (pintype "bidirectional"))
      (node (ref "U$3") (pin "P$76") (pinfunction "C16_P$76") (pintype "bidirectional"))
      (node (ref "U$3") (pin "P$8") (pinfunction "A8_P$8") (pintype "bidirectional"))
      (node (ref "U$3") (pin "P$83") (pinfunction "C23_P$83") (pintype "bidirectional"))
      (node (ref "U$3") (pin "P$9") (pinfunction "A9_P$9") (pintype "bidirectional"))
      (node (ref "U$3") (pin "P$90") (pinfunction "C30_P$90") (pintype "bidirectional"))
      (node (ref "U$3") (pin "P$91") (pinfunction "D1_P$91") (pintype "bidirectional"))
      (node (ref "U$3") (pin "P$92") (pinfunction "D2_P$92") (pintype "bidirectional"))
      (node (ref "U$3") (pin "P$99") (pinfunction "D9_P$99") (pintype "bidirectional"))
      (node (ref "U$4") (pin "P$1") (pinfunction "A1_P$1") (pintype "bidirectional"))
      (node (ref "U$4") (pin "P$10") (pinfunction "A10_P$10") (pintype "bidirectional"))
      (node (ref "U$4") (pin "P$106") (pinfunction "D16_P$106") (pintype "bidirectional"))
      (node (ref "U$4") (pin "P$11") (pinfunction "A11_P$11") (pintype "bidirectional"))
      (node (ref "U$4") (pin "P$113") (pinfunction "D23_P$113") (pintype "bidirectional"))
      (node (ref "U$4") (pin "P$12") (pinfunction "A12_P$12") (pintype "bidirectional"))
      (node (ref "U$4") (pin "P$120") (pinfunction "D30_P$120") (pintype "bidirectional"))
      (node (ref "U$4") (pin "P$121") (pinfunction "E1_P$121") (pintype "bidirectional"))
      (node (ref "U$4") (pin "P$13") (pinfunction "A13_P$13") (pintype "bidirectional"))
      (node (ref "U$4") (pin "P$14") (pinfunction "A14_P$14") (pintype "bidirectional"))
      (node (ref "U$4") (pin "P$15") (pinfunction "A15_P$15") (pintype "bidirectional"))
      (node (ref "U$4") (pin "P$150") (pinfunction "E30_P$150") (pintype "bidirectional"))
      (node (ref "U$4") (pin "P$151") (pinfunction "F1_P$151") (pintype "bidirectional"))
      (node (ref "U$4") (pin "P$16") (pinfunction "A16_P$16") (pintype "bidirectional"))
      (node (ref "U$4") (pin "P$17") (pinfunction "A17_P$17") (pintype "bidirectional"))
      (node (ref "U$4") (pin "P$18") (pinfunction "A18_P$18") (pintype "bidirectional"))
      (node (ref "U$4") (pin "P$180") (pinfunction "F30_P$180") (pintype "bidirectional"))
      (node (ref "U$4") (pin "P$19") (pinfunction "A19_P$19") (pintype "bidirectional"))
      (node (ref "U$4") (pin "P$2") (pinfunction "A2_P$2") (pintype "bidirectional"))
      (node (ref "U$4") (pin "P$20") (pinfunction "A20_P$20") (pintype "bidirectional"))
      (node (ref "U$4") (pin "P$21") (pinfunction "A21_P$21") (pintype "bidirectional"))
      (node (ref "U$4") (pin "P$22") (pinfunction "A22_P$22") (pintype "bidirectional"))
      (node (ref "U$4") (pin "P$23") (pinfunction "A23_P$23") (pintype "bidirectional"))
      (node (ref "U$4") (pin "P$24") (pinfunction "A24_P$24") (pintype "bidirectional"))
      (node (ref "U$4") (pin "P$25") (pinfunction "A25_P$25") (pintype "bidirectional"))
      (node (ref "U$4") (pin "P$26") (pinfunction "A26_P$26") (pintype "bidirectional"))
      (node (ref "U$4") (pin "P$27") (pinfunction "A27_P$27") (pintype "bidirectional"))
      (node (ref "U$4") (pin "P$28") (pinfunction "A28_P$28") (pintype "bidirectional"))
      (node (ref "U$4") (pin "P$29") (pinfunction "A29_P$29") (pintype "bidirectional"))
      (node (ref "U$4") (pin "P$3") (pinfunction "A3_P$3") (pintype "bidirectional"))
      (node (ref "U$4") (pin "P$31") (pinfunction "B1_P$31") (pintype "bidirectional"))
      (node (ref "U$4") (pin "P$32") (pinfunction "B2_P$32") (pintype "bidirectional"))
      (node (ref "U$4") (pin "P$39") (pinfunction "B9_P$39") (pintype "bidirectional"))
      (node (ref "U$4") (pin "P$4") (pinfunction "A4_P$4") (pintype "bidirectional"))
      (node (ref "U$4") (pin "P$46") (pinfunction "B16_P$46") (pintype "bidirectional"))
      (node (ref "U$4") (pin "P$5") (pinfunction "A5_P$5") (pintype "bidirectional"))
      (node (ref "U$4") (pin "P$53") (pinfunction "B23_P$53") (pintype "bidirectional"))
      (node (ref "U$4") (pin "P$6") (pinfunction "A6_P$6") (pintype "bidirectional"))
      (node (ref "U$4") (pin "P$60") (pinfunction "B30_P$60") (pintype "bidirectional"))
      (node (ref "U$4") (pin "P$61") (pinfunction "C1_P$61") (pintype "bidirectional"))
      (node (ref "U$4") (pin "P$62") (pinfunction "C2_P$62") (pintype "bidirectional"))
      (node (ref "U$4") (pin "P$69") (pinfunction "C9_P$69") (pintype "bidirectional"))
      (node (ref "U$4") (pin "P$7") (pinfunction "A7_P$7") (pintype "bidirectional"))
      (node (ref "U$4") (pin "P$76") (pinfunction "C16_P$76") (pintype "bidirectional"))
      (node (ref "U$4") (pin "P$8") (pinfunction "A8_P$8") (pintype "bidirectional"))
      (node (ref "U$4") (pin "P$83") (pinfunction "C23_P$83") (pintype "bidirectional"))
      (node (ref "U$4") (pin "P$9") (pinfunction "A9_P$9") (pintype "bidirectional"))
      (node (ref "U$4") (pin "P$90") (pinfunction "C30_P$90") (pintype "bidirectional"))
      (node (ref "U$4") (pin "P$91") (pinfunction "D1_P$91") (pintype "bidirectional"))
      (node (ref "U$4") (pin "P$92") (pinfunction "D2_P$92") (pintype "bidirectional"))
      (node (ref "U$4") (pin "P$99") (pinfunction "D9_P$99") (pintype "bidirectional"))
      (node (ref "U$5") (pin "P$1") (pinfunction "A1_P$1") (pintype "bidirectional"))
      (node (ref "U$5") (pin "P$10") (pinfunction "A10_P$10") (pintype "bidirectional"))
      (node (ref "U$5") (pin "P$106") (pinfunction "D16_P$106") (pintype "bidirectional"))
      (node (ref "U$5") (pin "P$11") (pinfunction "A11_P$11") (pintype "bidirectional"))
      (node (ref "U$5") (pin "P$113") (pinfunction "D23_P$113") (pintype "bidirectional"))
      (node (ref "U$5") (pin "P$12") (pinfunction "A12_P$12") (pintype "bidirectional"))
      (node (ref "U$5") (pin "P$120") (pinfunction "D30_P$120") (pintype "bidirectional"))
      (node (ref "U$5") (pin "P$121") (pinfunction "E1_P$121") (pintype "bidirectional"))
      (node (ref "U$5") (pin "P$13") (pinfunction "A13_P$13") (pintype "bidirectional"))
      (node (ref "U$5") (pin "P$14") (pinfunction "A14_P$14") (pintype "bidirectional"))
      (node (ref "U$5") (pin "P$15") (pinfunction "A15_P$15") (pintype "bidirectional"))
      (node (ref "U$5") (pin "P$150") (pinfunction "E30_P$150") (pintype "bidirectional"))
      (node (ref "U$5") (pin "P$151") (pinfunction "F1_P$151") (pintype "bidirectional"))
      (node (ref "U$5") (pin "P$16") (pinfunction "A16_P$16") (pintype "bidirectional"))
      (node (ref "U$5") (pin "P$17") (pinfunction "A17_P$17") (pintype "bidirectional"))
      (node (ref "U$5") (pin "P$18") (pinfunction "A18_P$18") (pintype "bidirectional"))
      (node (ref "U$5") (pin "P$180") (pinfunction "F30_P$180") (pintype "bidirectional"))
      (node (ref "U$5") (pin "P$19") (pinfunction "A19_P$19") (pintype "bidirectional"))
      (node (ref "U$5") (pin "P$2") (pinfunction "A2_P$2") (pintype "bidirectional"))
      (node (ref "U$5") (pin "P$20") (pinfunction "A20_P$20") (pintype "bidirectional"))
      (node (ref "U$5") (pin "P$21") (pinfunction "A21_P$21") (pintype "bidirectional"))
      (node (ref "U$5") (pin "P$22") (pinfunction "A22_P$22") (pintype "bidirectional"))
      (node (ref "U$5") (pin "P$23") (pinfunction "A23_P$23") (pintype "bidirectional"))
      (node (ref "U$5") (pin "P$24") (pinfunction "A24_P$24") (pintype "bidirectional"))
      (node (ref "U$5") (pin "P$25") (pinfunction "A25_P$25") (pintype "bidirectional"))
      (node (ref "U$5") (pin "P$26") (pinfunction "A26_P$26") (pintype "bidirectional"))
      (node (ref "U$5") (pin "P$27") (pinfunction "A27_P$27") (pintype "bidirectional"))
      (node (ref "U$5") (pin "P$28") (pinfunction "A28_P$28") (pintype "bidirectional"))
      (node (ref "U$5") (pin "P$29") (pinfunction "A29_P$29") (pintype "bidirectional"))
      (node (ref "U$5") (pin "P$3") (pinfunction "A3_P$3") (pintype "bidirectional"))
      (node (ref "U$5") (pin "P$31") (pinfunction "B1_P$31") (pintype "bidirectional"))
      (node (ref "U$5") (pin "P$32") (pinfunction "B2_P$32") (pintype "bidirectional"))
      (node (ref "U$5") (pin "P$39") (pinfunction "B9_P$39") (pintype "bidirectional"))
      (node (ref "U$5") (pin "P$4") (pinfunction "A4_P$4") (pintype "bidirectional"))
      (node (ref "U$5") (pin "P$46") (pinfunction "B16_P$46") (pintype "bidirectional"))
      (node (ref "U$5") (pin "P$5") (pinfunction "A5_P$5") (pintype "bidirectional"))
      (node (ref "U$5") (pin "P$53") (pinfunction "B23_P$53") (pintype "bidirectional"))
      (node (ref "U$5") (pin "P$6") (pinfunction "A6_P$6") (pintype "bidirectional"))
      (node (ref "U$5") (pin "P$60") (pinfunction "B30_P$60") (pintype "bidirectional"))
      (node (ref "U$5") (pin "P$61") (pinfunction "C1_P$61") (pintype "bidirectional"))
      (node (ref "U$5") (pin "P$62") (pinfunction "C2_P$62") (pintype "bidirectional"))
      (node (ref "U$5") (pin "P$69") (pinfunction "C9_P$69") (pintype "bidirectional"))
      (node (ref "U$5") (pin "P$7") (pinfunction "A7_P$7") (pintype "bidirectional"))
      (node (ref "U$5") (pin "P$76") (pinfunction "C16_P$76") (pintype "bidirectional"))
      (node (ref "U$5") (pin "P$8") (pinfunction "A8_P$8") (pintype "bidirectional"))
      (node (ref "U$5") (pin "P$83") (pinfunction "C23_P$83") (pintype "bidirectional"))
      (node (ref "U$5") (pin "P$9") (pinfunction "A9_P$9") (pintype "bidirectional"))
      (node (ref "U$5") (pin "P$90") (pinfunction "C30_P$90") (pintype "bidirectional"))
      (node (ref "U$5") (pin "P$91") (pinfunction "D1_P$91") (pintype "bidirectional"))
      (node (ref "U$5") (pin "P$92") (pinfunction "D2_P$92") (pintype "bidirectional"))
      (node (ref "U$5") (pin "P$99") (pinfunction "D9_P$99") (pintype "bidirectional"))
      (node (ref "U$6") (pin "P$1") (pinfunction "A1_P$1") (pintype "bidirectional"))
      (node (ref "U$6") (pin "P$10") (pinfunction "A10_P$10") (pintype "bidirectional"))
      (node (ref "U$6") (pin "P$106") (pinfunction "D16_P$106") (pintype "bidirectional"))
      (node (ref "U$6") (pin "P$11") (pinfunction "A11_P$11") (pintype "bidirectional"))
      (node (ref "U$6") (pin "P$113") (pinfunction "D23_P$113") (pintype "bidirectional"))
      (node (ref "U$6") (pin "P$12") (pinfunction "A12_P$12") (pintype "bidirectional"))
      (node (ref "U$6") (pin "P$120") (pinfunction "D30_P$120") (pintype "bidirectional"))
      (node (ref "U$6") (pin "P$121") (pinfunction "E1_P$121") (pintype "bidirectional"))
      (node (ref "U$6") (pin "P$13") (pinfunction "A13_P$13") (pintype "bidirectional"))
      (node (ref "U$6") (pin "P$14") (pinfunction "A14_P$14") (pintype "bidirectional"))
      (node (ref "U$6") (pin "P$15") (pinfunction "A15_P$15") (pintype "bidirectional"))
      (node (ref "U$6") (pin "P$150") (pinfunction "E30_P$150") (pintype "bidirectional"))
      (node (ref "U$6") (pin "P$151") (pinfunction "F1_P$151") (pintype "bidirectional"))
      (node (ref "U$6") (pin "P$16") (pinfunction "A16_P$16") (pintype "bidirectional"))
      (node (ref "U$6") (pin "P$17") (pinfunction "A17_P$17") (pintype "bidirectional"))
      (node (ref "U$6") (pin "P$18") (pinfunction "A18_P$18") (pintype "bidirectional"))
      (node (ref "U$6") (pin "P$180") (pinfunction "F30_P$180") (pintype "bidirectional"))
      (node (ref "U$6") (pin "P$19") (pinfunction "A19_P$19") (pintype "bidirectional"))
      (node (ref "U$6") (pin "P$2") (pinfunction "A2_P$2") (pintype "bidirectional"))
      (node (ref "U$6") (pin "P$20") (pinfunction "A20_P$20") (pintype "bidirectional"))
      (node (ref "U$6") (pin "P$21") (pinfunction "A21_P$21") (pintype "bidirectional"))
      (node (ref "U$6") (pin "P$22") (pinfunction "A22_P$22") (pintype "bidirectional"))
      (node (ref "U$6") (pin "P$23") (pinfunction "A23_P$23") (pintype "bidirectional"))
      (node (ref "U$6") (pin "P$24") (pinfunction "A24_P$24") (pintype "bidirectional"))
      (node (ref "U$6") (pin "P$25") (pinfunction "A25_P$25") (pintype "bidirectional"))
      (node (ref "U$6") (pin "P$26") (pinfunction "A26_P$26") (pintype "bidirectional"))
      (node (ref "U$6") (pin "P$27") (pinfunction "A27_P$27") (pintype "bidirectional"))
      (node (ref "U$6") (pin "P$28") (pinfunction "A28_P$28") (pintype "bidirectional"))
      (node (ref "U$6") (pin "P$29") (pinfunction "A29_P$29") (pintype "bidirectional"))
      (node (ref "U$6") (pin "P$3") (pinfunction "A3_P$3") (pintype "bidirectional"))
      (node (ref "U$6") (pin "P$31") (pinfunction "B1_P$31") (pintype "bidirectional"))
      (node (ref "U$6") (pin "P$32") (pinfunction "B2_P$32") (pintype "bidirectional"))
      (node (ref "U$6") (pin "P$39") (pinfunction "B9_P$39") (pintype "bidirectional"))
      (node (ref "U$6") (pin "P$4") (pinfunction "A4_P$4") (pintype "bidirectional"))
      (node (ref "U$6") (pin "P$46") (pinfunction "B16_P$46") (pintype "bidirectional"))
      (node (ref "U$6") (pin "P$5") (pinfunction "A5_P$5") (pintype "bidirectional"))
      (node (ref "U$6") (pin "P$53") (pinfunction "B23_P$53") (pintype "bidirectional"))
      (node (ref "U$6") (pin "P$6") (pinfunction "A6_P$6") (pintype "bidirectional"))
      (node (ref "U$6") (pin "P$60") (pinfunction "B30_P$60") (pintype "bidirectional"))
      (node (ref "U$6") (pin "P$61") (pinfunction "C1_P$61") (pintype "bidirectional"))
      (node (ref "U$6") (pin "P$62") (pinfunction "C2_P$62") (pintype "bidirectional"))
      (node (ref "U$6") (pin "P$69") (pinfunction "C9_P$69") (pintype "bidirectional"))
      (node (ref "U$6") (pin "P$7") (pinfunction "A7_P$7") (pintype "bidirectional"))
      (node (ref "U$6") (pin "P$76") (pinfunction "C16_P$76") (pintype "bidirectional"))
      (node (ref "U$6") (pin "P$8") (pinfunction "A8_P$8") (pintype "bidirectional"))
      (node (ref "U$6") (pin "P$83") (pinfunction "C23_P$83") (pintype "bidirectional"))
      (node (ref "U$6") (pin "P$9") (pinfunction "A9_P$9") (pintype "bidirectional"))
      (node (ref "U$6") (pin "P$90") (pinfunction "C30_P$90") (pintype "bidirectional"))
      (node (ref "U$6") (pin "P$91") (pinfunction "D1_P$91") (pintype "bidirectional"))
      (node (ref "U$6") (pin "P$92") (pinfunction "D2_P$92") (pintype "bidirectional"))
      (node (ref "U$6") (pin "P$99") (pinfunction "D9_P$99") (pintype "bidirectional"))
      (node (ref "U$7") (pin "P$1") (pinfunction "A1_P$1") (pintype "bidirectional"))
      (node (ref "U$7") (pin "P$10") (pinfunction "A10_P$10") (pintype "bidirectional"))
      (node (ref "U$7") (pin "P$106") (pinfunction "D16_P$106") (pintype "bidirectional"))
      (node (ref "U$7") (pin "P$11") (pinfunction "A11_P$11") (pintype "bidirectional"))
      (node (ref "U$7") (pin "P$113") (pinfunction "D23_P$113") (pintype "bidirectional"))
      (node (ref "U$7") (pin "P$12") (pinfunction "A12_P$12") (pintype "bidirectional"))
      (node (ref "U$7") (pin "P$120") (pinfunction "D30_P$120") (pintype "bidirectional"))
      (node (ref "U$7") (pin "P$121") (pinfunction "E1_P$121") (pintype "bidirectional"))
      (node (ref "U$7") (pin "P$13") (pinfunction "A13_P$13") (pintype "bidirectional"))
      (node (ref "U$7") (pin "P$14") (pinfunction "A14_P$14") (pintype "bidirectional"))
      (node (ref "U$7") (pin "P$15") (pinfunction "A15_P$15") (pintype "bidirectional"))
      (node (ref "U$7") (pin "P$150") (pinfunction "E30_P$150") (pintype "bidirectional"))
      (node (ref "U$7") (pin "P$151") (pinfunction "F1_P$151") (pintype "bidirectional"))
      (node (ref "U$7") (pin "P$16") (pinfunction "A16_P$16") (pintype "bidirectional"))
      (node (ref "U$7") (pin "P$17") (pinfunction "A17_P$17") (pintype "bidirectional"))
      (node (ref "U$7") (pin "P$18") (pinfunction "A18_P$18") (pintype "bidirectional"))
      (node (ref "U$7") (pin "P$180") (pinfunction "F30_P$180") (pintype "bidirectional"))
      (node (ref "U$7") (pin "P$19") (pinfunction "A19_P$19") (pintype "bidirectional"))
      (node (ref "U$7") (pin "P$2") (pinfunction "A2_P$2") (pintype "bidirectional"))
      (node (ref "U$7") (pin "P$20") (pinfunction "A20_P$20") (pintype "bidirectional"))
      (node (ref "U$7") (pin "P$21") (pinfunction "A21_P$21") (pintype "bidirectional"))
      (node (ref "U$7") (pin "P$22") (pinfunction "A22_P$22") (pintype "bidirectional"))
      (node (ref "U$7") (pin "P$23") (pinfunction "A23_P$23") (pintype "bidirectional"))
      (node (ref "U$7") (pin "P$24") (pinfunction "A24_P$24") (pintype "bidirectional"))
      (node (ref "U$7") (pin "P$25") (pinfunction "A25_P$25") (pintype "bidirectional"))
      (node (ref "U$7") (pin "P$26") (pinfunction "A26_P$26") (pintype "bidirectional"))
      (node (ref "U$7") (pin "P$27") (pinfunction "A27_P$27") (pintype "bidirectional"))
      (node (ref "U$7") (pin "P$28") (pinfunction "A28_P$28") (pintype "bidirectional"))
      (node (ref "U$7") (pin "P$29") (pinfunction "A29_P$29") (pintype "bidirectional"))
      (node (ref "U$7") (pin "P$3") (pinfunction "A3_P$3") (pintype "bidirectional"))
      (node (ref "U$7") (pin "P$31") (pinfunction "B1_P$31") (pintype "bidirectional"))
      (node (ref "U$7") (pin "P$32") (pinfunction "B2_P$32") (pintype "bidirectional"))
      (node (ref "U$7") (pin "P$39") (pinfunction "B9_P$39") (pintype "bidirectional"))
      (node (ref "U$7") (pin "P$4") (pinfunction "A4_P$4") (pintype "bidirectional"))
      (node (ref "U$7") (pin "P$46") (pinfunction "B16_P$46") (pintype "bidirectional"))
      (node (ref "U$7") (pin "P$5") (pinfunction "A5_P$5") (pintype "bidirectional"))
      (node (ref "U$7") (pin "P$53") (pinfunction "B23_P$53") (pintype "bidirectional"))
      (node (ref "U$7") (pin "P$6") (pinfunction "A6_P$6") (pintype "bidirectional"))
      (node (ref "U$7") (pin "P$60") (pinfunction "B30_P$60") (pintype "bidirectional"))
      (node (ref "U$7") (pin "P$61") (pinfunction "C1_P$61") (pintype "bidirectional"))
      (node (ref "U$7") (pin "P$62") (pinfunction "C2_P$62") (pintype "bidirectional"))
      (node (ref "U$7") (pin "P$69") (pinfunction "C9_P$69") (pintype "bidirectional"))
      (node (ref "U$7") (pin "P$7") (pinfunction "A7_P$7") (pintype "bidirectional"))
      (node (ref "U$7") (pin "P$76") (pinfunction "C16_P$76") (pintype "bidirectional"))
      (node (ref "U$7") (pin "P$8") (pinfunction "A8_P$8") (pintype "bidirectional"))
      (node (ref "U$7") (pin "P$83") (pinfunction "C23_P$83") (pintype "bidirectional"))
      (node (ref "U$7") (pin "P$9") (pinfunction "A9_P$9") (pintype "bidirectional"))
      (node (ref "U$7") (pin "P$90") (pinfunction "C30_P$90") (pintype "bidirectional"))
      (node (ref "U$7") (pin "P$91") (pinfunction "D1_P$91") (pintype "bidirectional"))
      (node (ref "U$7") (pin "P$92") (pinfunction "D2_P$92") (pintype "bidirectional"))
      (node (ref "U$7") (pin "P$99") (pinfunction "D9_P$99") (pintype "bidirectional"))
      (node (ref "U$8") (pin "P$1") (pinfunction "A1_P$1") (pintype "bidirectional"))
      (node (ref "U$8") (pin "P$10") (pinfunction "A10_P$10") (pintype "bidirectional"))
      (node (ref "U$8") (pin "P$106") (pinfunction "D16_P$106") (pintype "bidirectional"))
      (node (ref "U$8") (pin "P$11") (pinfunction "A11_P$11") (pintype "bidirectional"))
      (node (ref "U$8") (pin "P$113") (pinfunction "D23_P$113") (pintype "bidirectional"))
      (node (ref "U$8") (pin "P$12") (pinfunction "A12_P$12") (pintype "bidirectional"))
      (node (ref "U$8") (pin "P$120") (pinfunction "D30_P$120") (pintype "bidirectional"))
      (node (ref "U$8") (pin "P$121") (pinfunction "E1_P$121") (pintype "bidirectional"))
      (node (ref "U$8") (pin "P$13") (pinfunction "A13_P$13") (pintype "bidirectional"))
      (node (ref "U$8") (pin "P$14") (pinfunction "A14_P$14") (pintype "bidirectional"))
      (node (ref "U$8") (pin "P$15") (pinfunction "A15_P$15") (pintype "bidirectional"))
      (node (ref "U$8") (pin "P$150") (pinfunction "E30_P$150") (pintype "bidirectional"))
      (node (ref "U$8") (pin "P$151") (pinfunction "F1_P$151") (pintype "bidirectional"))
      (node (ref "U$8") (pin "P$16") (pinfunction "A16_P$16") (pintype "bidirectional"))
      (node (ref "U$8") (pin "P$17") (pinfunction "A17_P$17") (pintype "bidirectional"))
      (node (ref "U$8") (pin "P$18") (pinfunction "A18_P$18") (pintype "bidirectional"))
      (node (ref "U$8") (pin "P$180") (pinfunction "F30_P$180") (pintype "bidirectional"))
      (node (ref "U$8") (pin "P$19") (pinfunction "A19_P$19") (pintype "bidirectional"))
      (node (ref "U$8") (pin "P$2") (pinfunction "A2_P$2") (pintype "bidirectional"))
      (node (ref "U$8") (pin "P$20") (pinfunction "A20_P$20") (pintype "bidirectional"))
      (node (ref "U$8") (pin "P$21") (pinfunction "A21_P$21") (pintype "bidirectional"))
      (node (ref "U$8") (pin "P$22") (pinfunction "A22_P$22") (pintype "bidirectional"))
      (node (ref "U$8") (pin "P$23") (pinfunction "A23_P$23") (pintype "bidirectional"))
      (node (ref "U$8") (pin "P$24") (pinfunction "A24_P$24") (pintype "bidirectional"))
      (node (ref "U$8") (pin "P$25") (pinfunction "A25_P$25") (pintype "bidirectional"))
      (node (ref "U$8") (pin "P$26") (pinfunction "A26_P$26") (pintype "bidirectional"))
      (node (ref "U$8") (pin "P$27") (pinfunction "A27_P$27") (pintype "bidirectional"))
      (node (ref "U$8") (pin "P$28") (pinfunction "A28_P$28") (pintype "bidirectional"))
      (node (ref "U$8") (pin "P$29") (pinfunction "A29_P$29") (pintype "bidirectional"))
      (node (ref "U$8") (pin "P$3") (pinfunction "A3_P$3") (pintype "bidirectional"))
      (node (ref "U$8") (pin "P$31") (pinfunction "B1_P$31") (pintype "bidirectional"))
      (node (ref "U$8") (pin "P$32") (pinfunction "B2_P$32") (pintype "bidirectional"))
      (node (ref "U$8") (pin "P$39") (pinfunction "B9_P$39") (pintype "bidirectional"))
      (node (ref "U$8") (pin "P$4") (pinfunction "A4_P$4") (pintype "bidirectional"))
      (node (ref "U$8") (pin "P$46") (pinfunction "B16_P$46") (pintype "bidirectional"))
      (node (ref "U$8") (pin "P$5") (pinfunction "A5_P$5") (pintype "bidirectional"))
      (node (ref "U$8") (pin "P$53") (pinfunction "B23_P$53") (pintype "bidirectional"))
      (node (ref "U$8") (pin "P$6") (pinfunction "A6_P$6") (pintype "bidirectional"))
      (node (ref "U$8") (pin "P$60") (pinfunction "B30_P$60") (pintype "bidirectional"))
      (node (ref "U$8") (pin "P$61") (pinfunction "C1_P$61") (pintype "bidirectional"))
      (node (ref "U$8") (pin "P$62") (pinfunction "C2_P$62") (pintype "bidirectional"))
      (node (ref "U$8") (pin "P$69") (pinfunction "C9_P$69") (pintype "bidirectional"))
      (node (ref "U$8") (pin "P$7") (pinfunction "A7_P$7") (pintype "bidirectional"))
      (node (ref "U$8") (pin "P$76") (pinfunction "C16_P$76") (pintype "bidirectional"))
      (node (ref "U$8") (pin "P$8") (pinfunction "A8_P$8") (pintype "bidirectional"))
      (node (ref "U$8") (pin "P$83") (pinfunction "C23_P$83") (pintype "bidirectional"))
      (node (ref "U$8") (pin "P$9") (pinfunction "A9_P$9") (pintype "bidirectional"))
      (node (ref "U$8") (pin "P$90") (pinfunction "C30_P$90") (pintype "bidirectional"))
      (node (ref "U$8") (pin "P$91") (pinfunction "D1_P$91") (pintype "bidirectional"))
      (node (ref "U$8") (pin "P$92") (pinfunction "D2_P$92") (pintype "bidirectional"))
      (node (ref "U$8") (pin "P$99") (pinfunction "D9_P$99") (pintype "bidirectional"))
      (node (ref "U$9") (pin "P$1") (pinfunction "A1_P$1") (pintype "bidirectional"))
      (node (ref "U$9") (pin "P$10") (pinfunction "A10_P$10") (pintype "bidirectional"))
      (node (ref "U$9") (pin "P$106") (pinfunction "D16_P$106") (pintype "bidirectional"))
      (node (ref "U$9") (pin "P$11") (pinfunction "A11_P$11") (pintype "bidirectional"))
      (node (ref "U$9") (pin "P$113") (pinfunction "D23_P$113") (pintype "bidirectional"))
      (node (ref "U$9") (pin "P$12") (pinfunction "A12_P$12") (pintype "bidirectional"))
      (node (ref "U$9") (pin "P$120") (pinfunction "D30_P$120") (pintype "bidirectional"))
      (node (ref "U$9") (pin "P$121") (pinfunction "E1_P$121") (pintype "bidirectional"))
      (node (ref "U$9") (pin "P$13") (pinfunction "A13_P$13") (pintype "bidirectional"))
      (node (ref "U$9") (pin "P$14") (pinfunction "A14_P$14") (pintype "bidirectional"))
      (node (ref "U$9") (pin "P$15") (pinfunction "A15_P$15") (pintype "bidirectional"))
      (node (ref "U$9") (pin "P$150") (pinfunction "E30_P$150") (pintype "bidirectional"))
      (node (ref "U$9") (pin "P$151") (pinfunction "F1_P$151") (pintype "bidirectional"))
      (node (ref "U$9") (pin "P$16") (pinfunction "A16_P$16") (pintype "bidirectional"))
      (node (ref "U$9") (pin "P$17") (pinfunction "A17_P$17") (pintype "bidirectional"))
      (node (ref "U$9") (pin "P$18") (pinfunction "A18_P$18") (pintype "bidirectional"))
      (node (ref "U$9") (pin "P$180") (pinfunction "F30_P$180") (pintype "bidirectional"))
      (node (ref "U$9") (pin "P$19") (pinfunction "A19_P$19") (pintype "bidirectional"))
      (node (ref "U$9") (pin "P$2") (pinfunction "A2_P$2") (pintype "bidirectional"))
      (node (ref "U$9") (pin "P$20") (pinfunction "A20_P$20") (pintype "bidirectional"))
      (node (ref "U$9") (pin "P$21") (pinfunction "A21_P$21") (pintype "bidirectional"))
      (node (ref "U$9") (pin "P$22") (pinfunction "A22_P$22") (pintype "bidirectional"))
      (node (ref "U$9") (pin "P$23") (pinfunction "A23_P$23") (pintype "bidirectional"))
      (node (ref "U$9") (pin "P$24") (pinfunction "A24_P$24") (pintype "bidirectional"))
      (node (ref "U$9") (pin "P$25") (pinfunction "A25_P$25") (pintype "bidirectional"))
      (node (ref "U$9") (pin "P$26") (pinfunction "A26_P$26") (pintype "bidirectional"))
      (node (ref "U$9") (pin "P$27") (pinfunction "A27_P$27") (pintype "bidirectional"))
      (node (ref "U$9") (pin "P$28") (pinfunction "A28_P$28") (pintype "bidirectional"))
      (node (ref "U$9") (pin "P$29") (pinfunction "A29_P$29") (pintype "bidirectional"))
      (node (ref "U$9") (pin "P$3") (pinfunction "A3_P$3") (pintype "bidirectional"))
      (node (ref "U$9") (pin "P$31") (pinfunction "B1_P$31") (pintype "bidirectional"))
      (node (ref "U$9") (pin "P$32") (pinfunction "B2_P$32") (pintype "bidirectional"))
      (node (ref "U$9") (pin "P$39") (pinfunction "B9_P$39") (pintype "bidirectional"))
      (node (ref "U$9") (pin "P$4") (pinfunction "A4_P$4") (pintype "bidirectional"))
      (node (ref "U$9") (pin "P$46") (pinfunction "B16_P$46") (pintype "bidirectional"))
      (node (ref "U$9") (pin "P$5") (pinfunction "A5_P$5") (pintype "bidirectional"))
      (node (ref "U$9") (pin "P$53") (pinfunction "B23_P$53") (pintype "bidirectional"))
      (node (ref "U$9") (pin "P$6") (pinfunction "A6_P$6") (pintype "bidirectional"))
      (node (ref "U$9") (pin "P$60") (pinfunction "B30_P$60") (pintype "bidirectional"))
      (node (ref "U$9") (pin "P$61") (pinfunction "C1_P$61") (pintype "bidirectional"))
      (node (ref "U$9") (pin "P$62") (pinfunction "C2_P$62") (pintype "bidirectional"))
      (node (ref "U$9") (pin "P$69") (pinfunction "C9_P$69") (pintype "bidirectional"))
      (node (ref "U$9") (pin "P$7") (pinfunction "A7_P$7") (pintype "bidirectional"))
      (node (ref "U$9") (pin "P$76") (pinfunction "C16_P$76") (pintype "bidirectional"))
      (node (ref "U$9") (pin "P$8") (pinfunction "A8_P$8") (pintype "bidirectional"))
      (node (ref "U$9") (pin "P$83") (pinfunction "C23_P$83") (pintype "bidirectional"))
      (node (ref "U$9") (pin "P$9") (pinfunction "A9_P$9") (pintype "bidirectional"))
      (node (ref "U$9") (pin "P$90") (pinfunction "C30_P$90") (pintype "bidirectional"))
      (node (ref "U$9") (pin "P$91") (pinfunction "D1_P$91") (pintype "bidirectional"))
      (node (ref "U$9") (pin "P$92") (pinfunction "D2_P$92") (pintype "bidirectional"))
      (node (ref "U$9") (pin "P$99") (pinfunction "D9_P$99") (pintype "bidirectional"))
    )
    (net (code "34") (name "MEGAPAD") (class "Default")
      (node (ref "R.1") (pin "1") (pinfunction "1_1") (pintype "passive"))
      (node (ref "R.10") (pin "1") (pinfunction "1_1") (pintype "passive"))
      (node (ref "R.11") (pin "1") (pinfunction "1_1") (pintype "passive"))
      (node (ref "R.12") (pin "1") (pinfunction "1_1") (pintype "passive"))
      (node (ref "R.13") (pin "1") (pinfunction "1_1") (pintype "passive"))
      (node (ref "R.14") (pin "1") (pinfunction "1_1") (pintype "passive"))
      (node (ref "R.15") (pin "1") (pinfunction "1_1") (pintype "passive"))
      (node (ref "R.16") (pin "1") (pinfunction "1_1") (pintype "passive"))
      (node (ref "R.2") (pin "1") (pinfunction "1_1") (pintype "passive"))
      (node (ref "R.3") (pin "1") (pinfunction "1_1") (pintype "passive"))
      (node (ref "R.4") (pin "1") (pinfunction "1_1") (pintype "passive"))
      (node (ref "R.5") (pin "1") (pinfunction "1_1") (pintype "passive"))
      (node (ref "R.6") (pin "1") (pinfunction "1_1") (pintype "passive"))
      (node (ref "R.7") (pin "1") (pinfunction "1_1") (pintype "passive"))
      (node (ref "R.8") (pin "1") (pinfunction "1_1") (pintype "passive"))
      (node (ref "R.9") (pin "1") (pinfunction "1_1") (pintype "passive"))
    )
    (net (code "35") (name "Net-(U$1-A30)") (class "Default")
      (node (ref "U$1") (pin "P$30") (pinfunction "A30_P$30") (pintype "bidirectional"))
      (node (ref "U$13") (pin "P$2") (pinfunction "IO_P$2") (pintype "bidirectional"))
    )
    (net (code "36") (name "Net-(U$11-A30)") (class "Default")
      (node (ref "U$11") (pin "P$30") (pinfunction "A30_P$30") (pintype "bidirectional"))
      (node (ref "U$18") (pin "P$2") (pinfunction "IO_P$2") (pintype "bidirectional"))
    )
    (net (code "37") (name "Net-(U$14-IO)") (class "Default")
      (node (ref "U$14") (pin "P$2") (pinfunction "IO_P$2") (pintype "bidirectional"))
      (node (ref "U$3") (pin "P$30") (pinfunction "A30_P$30") (pintype "bidirectional"))
    )
    (net (code "38") (name "Net-(U$15-IO)") (class "Default")
      (node (ref "U$15") (pin "P$2") (pinfunction "IO_P$2") (pintype "bidirectional"))
      (node (ref "U$5") (pin "P$30") (pinfunction "A30_P$30") (pintype "bidirectional"))
    )
    (net (code "39") (name "Net-(U$16-IO)") (class "Default")
      (node (ref "U$16") (pin "P$2") (pinfunction "IO_P$2") (pintype "bidirectional"))
      (node (ref "U$7") (pin "P$30") (pinfunction "A30_P$30") (pintype "bidirectional"))
    )
    (net (code "40") (name "Net-(U$17-IO)") (class "Default")
      (node (ref "U$17") (pin "P$2") (pinfunction "IO_P$2") (pintype "bidirectional"))
      (node (ref "U$9") (pin "P$30") (pinfunction "A30_P$30") (pintype "bidirectional"))
    )
    (net (code "41") (name "ZZ.00.000") (class "Default")
      (node (ref "U$1") (pin "P$65") (pinfunction "C5_P$65") (pintype "bidirectional"))
    )
    (net (code "42") (name "ZZ.00.001") (class "Default")
      (node (ref "U$1") (pin "P$34") (pinfunction "B4_P$34") (pintype "bidirectional"))
    )
    (net (code "43") (name "ZZ.00.002") (class "Default")
      (node (ref "U$4") (pin "P$34") (pinfunction "B4_P$34") (pintype "bidirectional"))
    )
    (net (code "44") (name "ZZ.00.003") (class "Default")
      (node (ref "U$4") (pin "P$65") (pinfunction "C5_P$65") (pintype "bidirectional"))
    )
    (net (code "45") (name "ZZ.00.004") (class "Default")
      (node (ref "U$4") (pin "P$37") (pinfunction "B7_P$37") (pintype "bidirectional"))
    )
    (net (code "46") (name "ZZ.00.005") (class "Default")
      (node (ref "U$4") (pin "P$68") (pinfunction "C8_P$68") (pintype "bidirectional"))
    )
    (net (code "47") (name "ZZ.00.006") (class "Default")
      (node (ref "U$2") (pin "P$41") (pinfunction "B11_P$41") (pintype "bidirectional"))
    )
    (net (code "48") (name "ZZ.00.007") (class "Default")
      (node (ref "U$2") (pin "P$72") (pinfunction "C12_P$72") (pintype "bidirectional"))
    )
    (net (code "49") (name "ZZ.00.008") (class "Default")
      (node (ref "U$2") (pin "P$44") (pinfunction "B14_P$44") (pintype "bidirectional"))
    )
    (net (code "50") (name "ZZ.00.009") (class "Default")
      (node (ref "U$2") (pin "P$75") (pinfunction "C15_P$75") (pintype "bidirectional"))
    )
    (net (code "51") (name "ZZ.00.010") (class "Default")
      (node (ref "U$2") (pin "P$48") (pinfunction "B18_P$48") (pintype "bidirectional"))
    )
    (net (code "52") (name "ZZ.00.011") (class "Default")
      (node (ref "U$2") (pin "P$79") (pinfunction "C19_P$79") (pintype "bidirectional"))
    )
    (net (code "53") (name "ZZ.00.012") (class "Default")
      (node (ref "U$2") (pin "P$51") (pinfunction "B21_P$51") (pintype "bidirectional"))
    )
    (net (code "54") (name "ZZ.00.013") (class "Default")
      (node (ref "U$2") (pin "P$82") (pinfunction "C22_P$82") (pintype "bidirectional"))
    )
    (net (code "55") (name "ZZ.00.014") (class "Default")
      (node (ref "U$2") (pin "P$55") (pinfunction "B25_P$55") (pintype "bidirectional"))
    )
    (net (code "56") (name "ZZ.00.015") (class "Default")
      (node (ref "U$2") (pin "P$86") (pinfunction "C26_P$86") (pintype "bidirectional"))
    )
    (net (code "57") (name "ZZ.00.016") (class "Default")
      (node (ref "U$2") (pin "P$58") (pinfunction "B28_P$58") (pintype "bidirectional"))
    )
    (net (code "58") (name "ZZ.00.017") (class "Default")
      (node (ref "U$2") (pin "P$89") (pinfunction "C29_P$89") (pintype "bidirectional"))
    )
    (net (code "59") (name "ZZ.00.018") (class "Default")
      (node (ref "U$4") (pin "P$41") (pinfunction "B11_P$41") (pintype "bidirectional"))
    )
    (net (code "60") (name "ZZ.00.019") (class "Default")
      (node (ref "U$4") (pin "P$72") (pinfunction "C12_P$72") (pintype "bidirectional"))
    )
    (net (code "61") (name "ZZ.00.020") (class "Default")
      (node (ref "U$4") (pin "P$44") (pinfunction "B14_P$44") (pintype "bidirectional"))
    )
    (net (code "62") (name "ZZ.00.021") (class "Default")
      (node (ref "U$4") (pin "P$75") (pinfunction "C15_P$75") (pintype "bidirectional"))
    )
    (net (code "63") (name "ZZ.00.022") (class "Default")
      (node (ref "U$4") (pin "P$48") (pinfunction "B18_P$48") (pintype "bidirectional"))
    )
    (net (code "64") (name "ZZ.00.023") (class "Default")
      (node (ref "U$4") (pin "P$79") (pinfunction "C19_P$79") (pintype "bidirectional"))
    )
    (net (code "65") (name "ZZ.00.024") (class "Default")
      (node (ref "U$4") (pin "P$51") (pinfunction "B21_P$51") (pintype "bidirectional"))
    )
    (net (code "66") (name "ZZ.00.025") (class "Default")
      (node (ref "U$4") (pin "P$82") (pinfunction "C22_P$82") (pintype "bidirectional"))
    )
    (net (code "67") (name "ZZ.00.026") (class "Default")
      (node (ref "U$4") (pin "P$55") (pinfunction "B25_P$55") (pintype "bidirectional"))
    )
    (net (code "68") (name "ZZ.00.027") (class "Default")
      (node (ref "U$4") (pin "P$86") (pinfunction "C26_P$86") (pintype "bidirectional"))
    )
    (net (code "69") (name "ZZ.00.028") (class "Default")
      (node (ref "U$4") (pin "P$58") (pinfunction "B28_P$58") (pintype "bidirectional"))
    )
    (net (code "70") (name "ZZ.00.029") (class "Default")
      (node (ref "U$4") (pin "P$89") (pinfunction "C29_P$89") (pintype "bidirectional"))
    )
    (net (code "71") (name "ZZ.00.030") (class "Default")
      (node (ref "U$6") (pin "P$44") (pinfunction "B14_P$44") (pintype "bidirectional"))
    )
    (net (code "72") (name "ZZ.00.031") (class "Default")
      (node (ref "U$6") (pin "P$75") (pinfunction "C15_P$75") (pintype "bidirectional"))
    )
    (net (code "73") (name "ZZ.00.032") (class "Default")
      (node (ref "U$6") (pin "P$48") (pinfunction "B18_P$48") (pintype "bidirectional"))
    )
    (net (code "74") (name "ZZ.00.033") (class "Default")
      (node (ref "U$6") (pin "P$79") (pinfunction "C19_P$79") (pintype "bidirectional"))
    )
    (net (code "75") (name "ZZ.00.034") (class "Default")
      (node (ref "U$6") (pin "P$51") (pinfunction "B21_P$51") (pintype "bidirectional"))
    )
    (net (code "76") (name "ZZ.00.035") (class "Default")
      (node (ref "U$6") (pin "P$82") (pinfunction "C22_P$82") (pintype "bidirectional"))
    )
    (net (code "77") (name "ZZ.00.036") (class "Default")
      (node (ref "U$6") (pin "P$55") (pinfunction "B25_P$55") (pintype "bidirectional"))
    )
    (net (code "78") (name "ZZ.00.037") (class "Default")
      (node (ref "U$6") (pin "P$86") (pinfunction "C26_P$86") (pintype "bidirectional"))
    )
    (net (code "79") (name "ZZ.00.038") (class "Default")
      (node (ref "U$6") (pin "P$58") (pinfunction "B28_P$58") (pintype "bidirectional"))
    )
    (net (code "80") (name "ZZ.00.039") (class "Default")
      (node (ref "U$6") (pin "P$89") (pinfunction "C29_P$89") (pintype "bidirectional"))
    )
    (net (code "81") (name "ZZ.00.040") (class "Default")
      (node (ref "U$6") (pin "P$131") (pinfunction "E11_P$131") (pintype "bidirectional"))
    )
    (net (code "82") (name "ZZ.00.041") (class "Default")
      (node (ref "U$6") (pin "P$129") (pinfunction "E9_P$129") (pintype "bidirectional"))
    )
    (net (code "83") (name "ZZ.00.042") (class "Default")
      (node (ref "U$6") (pin "P$127") (pinfunction "E7_P$127") (pintype "bidirectional"))
    )
    (net (code "84") (name "ZZ.00.043") (class "Default")
      (node (ref "U$6") (pin "P$152") (pinfunction "F2_P$152") (pintype "bidirectional"))
    )
    (net (code "85") (name "ZZ.00.044") (class "Default")
      (node (ref "U$6") (pin "P$124") (pinfunction "E4_P$124") (pintype "bidirectional"))
    )
    (net (code "86") (name "ZZ.00.045") (class "Default")
      (node (ref "U$6") (pin "P$122") (pinfunction "E2_P$122") (pintype "bidirectional"))
    )
    (net (code "87") (name "ZZ.00.046") (class "Default")
      (node (ref "U$8") (pin "P$55") (pinfunction "B25_P$55") (pintype "bidirectional"))
    )
    (net (code "88") (name "ZZ.00.047") (class "Default")
      (node (ref "U$8") (pin "P$86") (pinfunction "C26_P$86") (pintype "bidirectional"))
    )
    (net (code "89") (name "ZZ.00.048") (class "Default")
      (node (ref "U$8") (pin "P$58") (pinfunction "B28_P$58") (pintype "bidirectional"))
    )
    (net (code "90") (name "ZZ.00.049") (class "Default")
      (node (ref "U$8") (pin "P$89") (pinfunction "C29_P$89") (pintype "bidirectional"))
    )
    (net (code "91") (name "ZZ.00.050") (class "Default")
      (node (ref "U$8") (pin "P$141") (pinfunction "E21_P$141") (pintype "bidirectional"))
    )
    (net (code "92") (name "ZZ.00.051") (class "Default")
      (node (ref "U$8") (pin "P$166") (pinfunction "F16_P$166") (pintype "bidirectional"))
    )
    (net (code "93") (name "ZZ.00.052") (class "Default")
      (node (ref "U$8") (pin "P$138") (pinfunction "E18_P$138") (pintype "bidirectional"))
    )
    (net (code "94") (name "ZZ.00.053") (class "Default")
      (node (ref "U$8") (pin "P$136") (pinfunction "E16_P$136") (pintype "bidirectional"))
    )
    (net (code "95") (name "ZZ.00.054") (class "Default")
      (node (ref "U$8") (pin "P$134") (pinfunction "E14_P$134") (pintype "bidirectional"))
    )
    (net (code "96") (name "ZZ.00.055") (class "Default")
      (node (ref "U$8") (pin "P$159") (pinfunction "F9_P$159") (pintype "bidirectional"))
    )
    (net (code "97") (name "ZZ.00.056") (class "Default")
      (node (ref "U$8") (pin "P$131") (pinfunction "E11_P$131") (pintype "bidirectional"))
    )
    (net (code "98") (name "ZZ.00.057") (class "Default")
      (node (ref "U$8") (pin "P$129") (pinfunction "E9_P$129") (pintype "bidirectional"))
    )
    (net (code "99") (name "ZZ.00.058") (class "Default")
      (node (ref "U$8") (pin "P$127") (pinfunction "E7_P$127") (pintype "bidirectional"))
    )
    (net (code "100") (name "ZZ.00.059") (class "Default")
      (node (ref "U$8") (pin "P$152") (pinfunction "F2_P$152") (pintype "bidirectional"))
    )
    (net (code "101") (name "ZZ.00.060") (class "Default")
      (node (ref "U$8") (pin "P$124") (pinfunction "E4_P$124") (pintype "bidirectional"))
    )
    (net (code "102") (name "ZZ.00.061") (class "Default")
      (node (ref "U$8") (pin "P$122") (pinfunction "E2_P$122") (pintype "bidirectional"))
    )
    (net (code "103") (name "ZZ.00.062") (class "Default")
      (node (ref "U$10") (pin "P$148") (pinfunction "E28_P$148") (pintype "bidirectional"))
    )
    (net (code "104") (name "ZZ.00.063") (class "Default")
      (node (ref "U$10") (pin "P$173") (pinfunction "F23_P$173") (pintype "bidirectional"))
    )
    (net (code "105") (name "ZZ.00.064") (class "Default")
      (node (ref "U$10") (pin "P$145") (pinfunction "E25_P$145") (pintype "bidirectional"))
    )
    (net (code "106") (name "ZZ.00.065") (class "Default")
      (node (ref "U$10") (pin "P$143") (pinfunction "E23_P$143") (pintype "bidirectional"))
    )
    (net (code "107") (name "ZZ.00.066") (class "Default")
      (node (ref "U$10") (pin "P$141") (pinfunction "E21_P$141") (pintype "bidirectional"))
    )
    (net (code "108") (name "ZZ.00.067") (class "Default")
      (node (ref "U$10") (pin "P$166") (pinfunction "F16_P$166") (pintype "bidirectional"))
    )
    (net (code "109") (name "ZZ.00.068") (class "Default")
      (node (ref "U$10") (pin "P$138") (pinfunction "E18_P$138") (pintype "bidirectional"))
    )
    (net (code "110") (name "ZZ.00.069") (class "Default")
      (node (ref "U$10") (pin "P$136") (pinfunction "E16_P$136") (pintype "bidirectional"))
    )
    (net (code "111") (name "ZZ.00.070") (class "Default")
      (node (ref "U$10") (pin "P$134") (pinfunction "E14_P$134") (pintype "bidirectional"))
    )
    (net (code "112") (name "ZZ.00.071") (class "Default")
      (node (ref "U$10") (pin "P$159") (pinfunction "F9_P$159") (pintype "bidirectional"))
    )
    (net (code "113") (name "ZZ.00.072") (class "Default")
      (node (ref "U$10") (pin "P$131") (pinfunction "E11_P$131") (pintype "bidirectional"))
    )
    (net (code "114") (name "ZZ.00.073") (class "Default")
      (node (ref "U$10") (pin "P$129") (pinfunction "E9_P$129") (pintype "bidirectional"))
    )
    (net (code "115") (name "ZZ.00.074") (class "Default")
      (node (ref "U$10") (pin "P$127") (pinfunction "E7_P$127") (pintype "bidirectional"))
    )
    (net (code "116") (name "ZZ.00.075") (class "Default")
      (node (ref "U$10") (pin "P$152") (pinfunction "F2_P$152") (pintype "bidirectional"))
    )
    (net (code "117") (name "ZZ.00.076") (class "Default")
      (node (ref "U$10") (pin "P$124") (pinfunction "E4_P$124") (pintype "bidirectional"))
    )
    (net (code "118") (name "ZZ.00.077") (class "Default")
      (node (ref "U$10") (pin "P$122") (pinfunction "E2_P$122") (pintype "bidirectional"))
    )
    (net (code "119") (name "ZZ.00.078") (class "Default")
      (node (ref "U$12") (pin "P$148") (pinfunction "E28_P$148") (pintype "bidirectional"))
    )
    (net (code "120") (name "ZZ.00.079") (class "Default")
      (node (ref "U$12") (pin "P$173") (pinfunction "F23_P$173") (pintype "bidirectional"))
    )
    (net (code "121") (name "ZZ.00.080") (class "Default")
      (node (ref "U$12") (pin "P$145") (pinfunction "E25_P$145") (pintype "bidirectional"))
    )
    (net (code "122") (name "ZZ.00.081") (class "Default")
      (node (ref "U$12") (pin "P$143") (pinfunction "E23_P$143") (pintype "bidirectional"))
    )
    (net (code "123") (name "ZZ.00.082") (class "Default")
      (node (ref "U$12") (pin "P$141") (pinfunction "E21_P$141") (pintype "bidirectional"))
    )
    (net (code "124") (name "ZZ.00.083") (class "Default")
      (node (ref "U$12") (pin "P$166") (pinfunction "F16_P$166") (pintype "bidirectional"))
    )
    (net (code "125") (name "ZZ.00.084") (class "Default")
      (node (ref "U$12") (pin "P$138") (pinfunction "E18_P$138") (pintype "bidirectional"))
    )
    (net (code "126") (name "ZZ.00.085") (class "Default")
      (node (ref "U$12") (pin "P$136") (pinfunction "E16_P$136") (pintype "bidirectional"))
    )
    (net (code "127") (name "ZZ.00.086") (class "Default")
      (node (ref "U$12") (pin "P$134") (pinfunction "E14_P$134") (pintype "bidirectional"))
    )
    (net (code "128") (name "ZZ.00.087") (class "Default")
      (node (ref "U$12") (pin "P$159") (pinfunction "F9_P$159") (pintype "bidirectional"))
    )
    (net (code "129") (name "ZZ.00.088") (class "Default")
      (node (ref "U$12") (pin "P$131") (pinfunction "E11_P$131") (pintype "bidirectional"))
    )
    (net (code "130") (name "ZZ.00.089") (class "Default")
      (node (ref "U$12") (pin "P$129") (pinfunction "E9_P$129") (pintype "bidirectional"))
    )
    (net (code "131") (name "ZZ.00.090") (class "Default")
      (node (ref "U$12") (pin "P$127") (pinfunction "E7_P$127") (pintype "bidirectional"))
    )
    (net (code "132") (name "ZZ.00.091") (class "Default")
      (node (ref "U$12") (pin "P$152") (pinfunction "F2_P$152") (pintype "bidirectional"))
    )
    (net (code "133") (name "ZZ.00.092") (class "Default")
      (node (ref "U$12") (pin "P$124") (pinfunction "E4_P$124") (pintype "bidirectional"))
    )
    (net (code "134") (name "ZZ.00.093") (class "Default")
      (node (ref "U$12") (pin "P$122") (pinfunction "E2_P$122") (pintype "bidirectional"))
    )
    (net (code "135") (name "ZZ.01.000") (class "Default")
      (node (ref "U$1") (pin "P$35") (pinfunction "B5_P$35") (pintype "bidirectional"))
    )
    (net (code "136") (name "ZZ.01.001") (class "Default")
      (node (ref "U$1") (pin "P$63") (pinfunction "C3_P$63") (pintype "bidirectional"))
    )
    (net (code "137") (name "ZZ.01.002") (class "Default")
      (node (ref "U$4") (pin "P$63") (pinfunction "C3_P$63") (pintype "bidirectional"))
    )
    (net (code "138") (name "ZZ.01.003") (class "Default")
      (node (ref "U$4") (pin "P$35") (pinfunction "B5_P$35") (pintype "bidirectional"))
    )
    (net (code "139") (name "ZZ.01.004") (class "Default")
      (node (ref "U$4") (pin "P$66") (pinfunction "C6_P$66") (pintype "bidirectional"))
    )
    (net (code "140") (name "ZZ.01.005") (class "Default")
      (node (ref "U$4") (pin "P$38") (pinfunction "B8_P$38") (pintype "bidirectional"))
    )
    (net (code "141") (name "ZZ.01.006") (class "Default")
      (node (ref "U$2") (pin "P$70") (pinfunction "C10_P$70") (pintype "bidirectional"))
    )
    (net (code "142") (name "ZZ.01.007") (class "Default")
      (node (ref "U$2") (pin "P$42") (pinfunction "B12_P$42") (pintype "bidirectional"))
    )
    (net (code "143") (name "ZZ.01.008") (class "Default")
      (node (ref "U$2") (pin "P$73") (pinfunction "C13_P$73") (pintype "bidirectional"))
    )
    (net (code "144") (name "ZZ.01.009") (class "Default")
      (node (ref "U$2") (pin "P$45") (pinfunction "B15_P$45") (pintype "bidirectional"))
    )
    (net (code "145") (name "ZZ.01.010") (class "Default")
      (node (ref "U$2") (pin "P$77") (pinfunction "C17_P$77") (pintype "bidirectional"))
    )
    (net (code "146") (name "ZZ.01.011") (class "Default")
      (node (ref "U$2") (pin "P$49") (pinfunction "B19_P$49") (pintype "bidirectional"))
    )
    (net (code "147") (name "ZZ.01.012") (class "Default")
      (node (ref "U$2") (pin "P$80") (pinfunction "C20_P$80") (pintype "bidirectional"))
    )
    (net (code "148") (name "ZZ.01.013") (class "Default")
      (node (ref "U$2") (pin "P$52") (pinfunction "B22_P$52") (pintype "bidirectional"))
    )
    (net (code "149") (name "ZZ.01.014") (class "Default")
      (node (ref "U$2") (pin "P$84") (pinfunction "C24_P$84") (pintype "bidirectional"))
    )
    (net (code "150") (name "ZZ.01.015") (class "Default")
      (node (ref "U$2") (pin "P$56") (pinfunction "B26_P$56") (pintype "bidirectional"))
    )
    (net (code "151") (name "ZZ.01.016") (class "Default")
      (node (ref "U$2") (pin "P$87") (pinfunction "C27_P$87") (pintype "bidirectional"))
    )
    (net (code "152") (name "ZZ.01.017") (class "Default")
      (node (ref "U$2") (pin "P$59") (pinfunction "B29_P$59") (pintype "bidirectional"))
    )
    (net (code "153") (name "ZZ.01.018") (class "Default")
      (node (ref "U$4") (pin "P$70") (pinfunction "C10_P$70") (pintype "bidirectional"))
    )
    (net (code "154") (name "ZZ.01.019") (class "Default")
      (node (ref "U$4") (pin "P$42") (pinfunction "B12_P$42") (pintype "bidirectional"))
    )
    (net (code "155") (name "ZZ.01.020") (class "Default")
      (node (ref "U$4") (pin "P$73") (pinfunction "C13_P$73") (pintype "bidirectional"))
    )
    (net (code "156") (name "ZZ.01.021") (class "Default")
      (node (ref "U$4") (pin "P$45") (pinfunction "B15_P$45") (pintype "bidirectional"))
    )
    (net (code "157") (name "ZZ.01.022") (class "Default")
      (node (ref "U$4") (pin "P$77") (pinfunction "C17_P$77") (pintype "bidirectional"))
    )
    (net (code "158") (name "ZZ.01.023") (class "Default")
      (node (ref "U$4") (pin "P$49") (pinfunction "B19_P$49") (pintype "bidirectional"))
    )
    (net (code "159") (name "ZZ.01.024") (class "Default")
      (node (ref "U$4") (pin "P$80") (pinfunction "C20_P$80") (pintype "bidirectional"))
    )
    (net (code "160") (name "ZZ.01.025") (class "Default")
      (node (ref "U$4") (pin "P$52") (pinfunction "B22_P$52") (pintype "bidirectional"))
    )
    (net (code "161") (name "ZZ.01.026") (class "Default")
      (node (ref "U$4") (pin "P$84") (pinfunction "C24_P$84") (pintype "bidirectional"))
    )
    (net (code "162") (name "ZZ.01.027") (class "Default")
      (node (ref "U$4") (pin "P$56") (pinfunction "B26_P$56") (pintype "bidirectional"))
    )
    (net (code "163") (name "ZZ.01.028") (class "Default")
      (node (ref "U$4") (pin "P$87") (pinfunction "C27_P$87") (pintype "bidirectional"))
    )
    (net (code "164") (name "ZZ.01.029") (class "Default")
      (node (ref "U$4") (pin "P$59") (pinfunction "B29_P$59") (pintype "bidirectional"))
    )
    (net (code "165") (name "ZZ.01.030") (class "Default")
      (node (ref "U$6") (pin "P$73") (pinfunction "C13_P$73") (pintype "bidirectional"))
    )
    (net (code "166") (name "ZZ.01.031") (class "Default")
      (node (ref "U$6") (pin "P$45") (pinfunction "B15_P$45") (pintype "bidirectional"))
    )
    (net (code "167") (name "ZZ.01.032") (class "Default")
      (node (ref "U$6") (pin "P$77") (pinfunction "C17_P$77") (pintype "bidirectional"))
    )
    (net (code "168") (name "ZZ.01.033") (class "Default")
      (node (ref "U$6") (pin "P$49") (pinfunction "B19_P$49") (pintype "bidirectional"))
    )
    (net (code "169") (name "ZZ.01.034") (class "Default")
      (node (ref "U$6") (pin "P$80") (pinfunction "C20_P$80") (pintype "bidirectional"))
    )
    (net (code "170") (name "ZZ.01.035") (class "Default")
      (node (ref "U$6") (pin "P$52") (pinfunction "B22_P$52") (pintype "bidirectional"))
    )
    (net (code "171") (name "ZZ.01.036") (class "Default")
      (node (ref "U$6") (pin "P$84") (pinfunction "C24_P$84") (pintype "bidirectional"))
    )
    (net (code "172") (name "ZZ.01.037") (class "Default")
      (node (ref "U$6") (pin "P$56") (pinfunction "B26_P$56") (pintype "bidirectional"))
    )
    (net (code "173") (name "ZZ.01.038") (class "Default")
      (node (ref "U$6") (pin "P$87") (pinfunction "C27_P$87") (pintype "bidirectional"))
    )
    (net (code "174") (name "ZZ.01.039") (class "Default")
      (node (ref "U$6") (pin "P$59") (pinfunction "B29_P$59") (pintype "bidirectional"))
    )
    (net (code "175") (name "ZZ.01.040") (class "Default")
      (node (ref "U$6") (pin "P$162") (pinfunction "F12_P$162") (pintype "bidirectional"))
    )
    (net (code "176") (name "ZZ.01.041") (class "Default")
      (node (ref "U$6") (pin "P$160") (pinfunction "F10_P$160") (pintype "bidirectional"))
    )
    (net (code "177") (name "ZZ.01.042") (class "Default")
      (node (ref "U$6") (pin "P$158") (pinfunction "F8_P$158") (pintype "bidirectional"))
    )
    (net (code "178") (name "ZZ.01.043") (class "Default")
      (node (ref "U$6") (pin "P$156") (pinfunction "F6_P$156") (pintype "bidirectional"))
    )
    (net (code "179") (name "ZZ.01.044") (class "Default")
      (node (ref "U$6") (pin "P$155") (pinfunction "F5_P$155") (pintype "bidirectional"))
    )
    (net (code "180") (name "ZZ.01.045") (class "Default")
      (node (ref "U$6") (pin "P$153") (pinfunction "F3_P$153") (pintype "bidirectional"))
    )
    (net (code "181") (name "ZZ.01.046") (class "Default")
      (node (ref "U$8") (pin "P$84") (pinfunction "C24_P$84") (pintype "bidirectional"))
    )
    (net (code "182") (name "ZZ.01.047") (class "Default")
      (node (ref "U$8") (pin "P$56") (pinfunction "B26_P$56") (pintype "bidirectional"))
    )
    (net (code "183") (name "ZZ.01.048") (class "Default")
      (node (ref "U$8") (pin "P$87") (pinfunction "C27_P$87") (pintype "bidirectional"))
    )
    (net (code "184") (name "ZZ.01.049") (class "Default")
      (node (ref "U$8") (pin "P$59") (pinfunction "B29_P$59") (pintype "bidirectional"))
    )
    (net (code "185") (name "ZZ.01.050") (class "Default")
      (node (ref "U$8") (pin "P$172") (pinfunction "F22_P$172") (pintype "bidirectional"))
    )
    (net (code "186") (name "ZZ.01.051") (class "Default")
      (node (ref "U$8") (pin "P$170") (pinfunction "F20_P$170") (pintype "bidirectional"))
    )
    (net (code "187") (name "ZZ.01.052") (class "Default")
      (node (ref "U$8") (pin "P$169") (pinfunction "F19_P$169") (pintype "bidirectional"))
    )
    (net (code "188") (name "ZZ.01.053") (class "Default")
      (node (ref "U$8") (pin "P$167") (pinfunction "F17_P$167") (pintype "bidirectional"))
    )
    (net (code "189") (name "ZZ.01.054") (class "Default")
      (node (ref "U$8") (pin "P$165") (pinfunction "F15_P$165") (pintype "bidirectional"))
    )
    (net (code "190") (name "ZZ.01.055") (class "Default")
      (node (ref "U$8") (pin "P$163") (pinfunction "F13_P$163") (pintype "bidirectional"))
    )
    (net (code "191") (name "ZZ.01.056") (class "Default")
      (node (ref "U$8") (pin "P$162") (pinfunction "F12_P$162") (pintype "bidirectional"))
    )
    (net (code "192") (name "ZZ.01.057") (class "Default")
      (node (ref "U$8") (pin "P$160") (pinfunction "F10_P$160") (pintype "bidirectional"))
    )
    (net (code "193") (name "ZZ.01.058") (class "Default")
      (node (ref "U$8") (pin "P$158") (pinfunction "F8_P$158") (pintype "bidirectional"))
    )
    (net (code "194") (name "ZZ.01.059") (class "Default")
      (node (ref "U$8") (pin "P$156") (pinfunction "F6_P$156") (pintype "bidirectional"))
    )
    (net (code "195") (name "ZZ.01.060") (class "Default")
      (node (ref "U$8") (pin "P$155") (pinfunction "F5_P$155") (pintype "bidirectional"))
    )
    (net (code "196") (name "ZZ.01.061") (class "Default")
      (node (ref "U$8") (pin "P$153") (pinfunction "F3_P$153") (pintype "bidirectional"))
    )
    (net (code "197") (name "ZZ.01.062") (class "Default")
      (node (ref "U$10") (pin "P$179") (pinfunction "F29_P$179") (pintype "bidirectional"))
    )
    (net (code "198") (name "ZZ.01.063") (class "Default")
      (node (ref "U$10") (pin "P$177") (pinfunction "F27_P$177") (pintype "bidirectional"))
    )
    (net (code "199") (name "ZZ.01.064") (class "Default")
      (node (ref "U$10") (pin "P$176") (pinfunction "F26_P$176") (pintype "bidirectional"))
    )
    (net (code "200") (name "ZZ.01.065") (class "Default")
      (node (ref "U$10") (pin "P$174") (pinfunction "F24_P$174") (pintype "bidirectional"))
    )
    (net (code "201") (name "ZZ.01.066") (class "Default")
      (node (ref "U$10") (pin "P$172") (pinfunction "F22_P$172") (pintype "bidirectional"))
    )
    (net (code "202") (name "ZZ.01.067") (class "Default")
      (node (ref "U$10") (pin "P$170") (pinfunction "F20_P$170") (pintype "bidirectional"))
    )
    (net (code "203") (name "ZZ.01.068") (class "Default")
      (node (ref "U$10") (pin "P$169") (pinfunction "F19_P$169") (pintype "bidirectional"))
    )
    (net (code "204") (name "ZZ.01.069") (class "Default")
      (node (ref "U$10") (pin "P$167") (pinfunction "F17_P$167") (pintype "bidirectional"))
    )
    (net (code "205") (name "ZZ.01.070") (class "Default")
      (node (ref "U$10") (pin "P$165") (pinfunction "F15_P$165") (pintype "bidirectional"))
    )
    (net (code "206") (name "ZZ.01.071") (class "Default")
      (node (ref "U$10") (pin "P$163") (pinfunction "F13_P$163") (pintype "bidirectional"))
    )
    (net (code "207") (name "ZZ.01.072") (class "Default")
      (node (ref "U$10") (pin "P$162") (pinfunction "F12_P$162") (pintype "bidirectional"))
    )
    (net (code "208") (name "ZZ.01.073") (class "Default")
      (node (ref "U$10") (pin "P$160") (pinfunction "F10_P$160") (pintype "bidirectional"))
    )
    (net (code "209") (name "ZZ.01.074") (class "Default")
      (node (ref "U$10") (pin "P$158") (pinfunction "F8_P$158") (pintype "bidirectional"))
    )
    (net (code "210") (name "ZZ.01.075") (class "Default")
      (node (ref "U$10") (pin "P$156") (pinfunction "F6_P$156") (pintype "bidirectional"))
    )
    (net (code "211") (name "ZZ.01.076") (class "Default")
      (node (ref "U$10") (pin "P$155") (pinfunction "F5_P$155") (pintype "bidirectional"))
    )
    (net (code "212") (name "ZZ.01.077") (class "Default")
      (node (ref "U$10") (pin "P$153") (pinfunction "F3_P$153") (pintype "bidirectional"))
    )
    (net (code "213") (name "ZZ.01.078") (class "Default")
      (node (ref "U$12") (pin "P$179") (pinfunction "F29_P$179") (pintype "bidirectional"))
    )
    (net (code "214") (name "ZZ.01.079") (class "Default")
      (node (ref "U$12") (pin "P$177") (pinfunction "F27_P$177") (pintype "bidirectional"))
    )
    (net (code "215") (name "ZZ.01.080") (class "Default")
      (node (ref "U$12") (pin "P$176") (pinfunction "F26_P$176") (pintype "bidirectional"))
    )
    (net (code "216") (name "ZZ.01.081") (class "Default")
      (node (ref "U$12") (pin "P$174") (pinfunction "F24_P$174") (pintype "bidirectional"))
    )
    (net (code "217") (name "ZZ.01.082") (class "Default")
      (node (ref "U$12") (pin "P$172") (pinfunction "F22_P$172") (pintype "bidirectional"))
    )
    (net (code "218") (name "ZZ.01.083") (class "Default")
      (node (ref "U$12") (pin "P$170") (pinfunction "F20_P$170") (pintype "bidirectional"))
    )
    (net (code "219") (name "ZZ.01.084") (class "Default")
      (node (ref "U$12") (pin "P$169") (pinfunction "F19_P$169") (pintype "bidirectional"))
    )
    (net (code "220") (name "ZZ.01.085") (class "Default")
      (node (ref "U$12") (pin "P$167") (pinfunction "F17_P$167") (pintype "bidirectional"))
    )
    (net (code "221") (name "ZZ.01.086") (class "Default")
      (node (ref "U$12") (pin "P$165") (pinfunction "F15_P$165") (pintype "bidirectional"))
    )
    (net (code "222") (name "ZZ.01.087") (class "Default")
      (node (ref "U$12") (pin "P$163") (pinfunction "F13_P$163") (pintype "bidirectional"))
    )
    (net (code "223") (name "ZZ.01.088") (class "Default")
      (node (ref "U$12") (pin "P$162") (pinfunction "F12_P$162") (pintype "bidirectional"))
    )
    (net (code "224") (name "ZZ.01.089") (class "Default")
      (node (ref "U$12") (pin "P$160") (pinfunction "F10_P$160") (pintype "bidirectional"))
    )
    (net (code "225") (name "ZZ.01.090") (class "Default")
      (node (ref "U$12") (pin "P$158") (pinfunction "F8_P$158") (pintype "bidirectional"))
    )
    (net (code "226") (name "ZZ.01.091") (class "Default")
      (node (ref "U$12") (pin "P$156") (pinfunction "F6_P$156") (pintype "bidirectional"))
    )
    (net (code "227") (name "ZZ.01.092") (class "Default")
      (node (ref "U$12") (pin "P$155") (pinfunction "F5_P$155") (pintype "bidirectional"))
    )
    (net (code "228") (name "ZZ.01.093") (class "Default")
      (node (ref "U$12") (pin "P$153") (pinfunction "F3_P$153") (pintype "bidirectional"))
    )
    (net (code "229") (name "ZZ.02.000") (class "Default")
      (node (ref "U$1") (pin "P$64") (pinfunction "C4_P$64") (pintype "bidirectional"))
    )
    (net (code "230") (name "ZZ.02.001") (class "Default")
      (node (ref "U$1") (pin "P$33") (pinfunction "B3_P$33") (pintype "bidirectional"))
    )
    (net (code "231") (name "ZZ.02.002") (class "Default")
      (node (ref "U$4") (pin "P$33") (pinfunction "B3_P$33") (pintype "bidirectional"))
    )
    (net (code "232") (name "ZZ.02.003") (class "Default")
      (node (ref "U$4") (pin "P$64") (pinfunction "C4_P$64") (pintype "bidirectional"))
    )
    (net (code "233") (name "ZZ.02.004") (class "Default")
      (node (ref "U$4") (pin "P$36") (pinfunction "B6_P$36") (pintype "bidirectional"))
    )
    (net (code "234") (name "ZZ.02.005") (class "Default")
      (node (ref "U$4") (pin "P$67") (pinfunction "C7_P$67") (pintype "bidirectional"))
    )
    (net (code "235") (name "ZZ.02.006") (class "Default")
      (node (ref "U$2") (pin "P$40") (pinfunction "B10_P$40") (pintype "bidirectional"))
    )
    (net (code "236") (name "ZZ.02.007") (class "Default")
      (node (ref "U$2") (pin "P$71") (pinfunction "C11_P$71") (pintype "bidirectional"))
    )
    (net (code "237") (name "ZZ.02.008") (class "Default")
      (node (ref "U$2") (pin "P$43") (pinfunction "B13_P$43") (pintype "bidirectional"))
    )
    (net (code "238") (name "ZZ.02.009") (class "Default")
      (node (ref "U$2") (pin "P$74") (pinfunction "C14_P$74") (pintype "bidirectional"))
    )
    (net (code "239") (name "ZZ.02.010") (class "Default")
      (node (ref "U$2") (pin "P$47") (pinfunction "B17_P$47") (pintype "bidirectional"))
    )
    (net (code "240") (name "ZZ.02.011") (class "Default")
      (node (ref "U$2") (pin "P$78") (pinfunction "C18_P$78") (pintype "bidirectional"))
    )
    (net (code "241") (name "ZZ.02.012") (class "Default")
      (node (ref "U$2") (pin "P$50") (pinfunction "B20_P$50") (pintype "bidirectional"))
    )
    (net (code "242") (name "ZZ.02.013") (class "Default")
      (node (ref "U$2") (pin "P$81") (pinfunction "C21_P$81") (pintype "bidirectional"))
    )
    (net (code "243") (name "ZZ.02.014") (class "Default")
      (node (ref "U$2") (pin "P$54") (pinfunction "B24_P$54") (pintype "bidirectional"))
    )
    (net (code "244") (name "ZZ.02.015") (class "Default")
      (node (ref "U$2") (pin "P$85") (pinfunction "C25_P$85") (pintype "bidirectional"))
    )
    (net (code "245") (name "ZZ.02.016") (class "Default")
      (node (ref "U$2") (pin "P$57") (pinfunction "B27_P$57") (pintype "bidirectional"))
    )
    (net (code "246") (name "ZZ.02.017") (class "Default")
      (node (ref "U$2") (pin "P$88") (pinfunction "C28_P$88") (pintype "bidirectional"))
    )
    (net (code "247") (name "ZZ.02.018") (class "Default")
      (node (ref "U$4") (pin "P$40") (pinfunction "B10_P$40") (pintype "bidirectional"))
    )
    (net (code "248") (name "ZZ.02.019") (class "Default")
      (node (ref "U$4") (pin "P$71") (pinfunction "C11_P$71") (pintype "bidirectional"))
    )
    (net (code "249") (name "ZZ.02.020") (class "Default")
      (node (ref "U$4") (pin "P$43") (pinfunction "B13_P$43") (pintype "bidirectional"))
    )
    (net (code "250") (name "ZZ.02.021") (class "Default")
      (node (ref "U$4") (pin "P$74") (pinfunction "C14_P$74") (pintype "bidirectional"))
    )
    (net (code "251") (name "ZZ.02.022") (class "Default")
      (node (ref "U$4") (pin "P$47") (pinfunction "B17_P$47") (pintype "bidirectional"))
    )
    (net (code "252") (name "ZZ.02.023") (class "Default")
      (node (ref "U$4") (pin "P$78") (pinfunction "C18_P$78") (pintype "bidirectional"))
    )
    (net (code "253") (name "ZZ.02.024") (class "Default")
      (node (ref "U$4") (pin "P$50") (pinfunction "B20_P$50") (pintype "bidirectional"))
    )
    (net (code "254") (name "ZZ.02.025") (class "Default")
      (node (ref "U$4") (pin "P$81") (pinfunction "C21_P$81") (pintype "bidirectional"))
    )
    (net (code "255") (name "ZZ.02.026") (class "Default")
      (node (ref "U$4") (pin "P$54") (pinfunction "B24_P$54") (pintype "bidirectional"))
    )
    (net (code "256") (name "ZZ.02.027") (class "Default")
      (node (ref "U$4") (pin "P$85") (pinfunction "C25_P$85") (pintype "bidirectional"))
    )
    (net (code "257") (name "ZZ.02.028") (class "Default")
      (node (ref "U$4") (pin "P$57") (pinfunction "B27_P$57") (pintype "bidirectional"))
    )
    (net (code "258") (name "ZZ.02.029") (class "Default")
      (node (ref "U$4") (pin "P$88") (pinfunction "C28_P$88") (pintype "bidirectional"))
    )
    (net (code "259") (name "ZZ.02.030") (class "Default")
      (node (ref "U$6") (pin "P$43") (pinfunction "B13_P$43") (pintype "bidirectional"))
    )
    (net (code "260") (name "ZZ.02.031") (class "Default")
      (node (ref "U$6") (pin "P$74") (pinfunction "C14_P$74") (pintype "bidirectional"))
    )
    (net (code "261") (name "ZZ.02.032") (class "Default")
      (node (ref "U$6") (pin "P$47") (pinfunction "B17_P$47") (pintype "bidirectional"))
    )
    (net (code "262") (name "ZZ.02.033") (class "Default")
      (node (ref "U$6") (pin "P$78") (pinfunction "C18_P$78") (pintype "bidirectional"))
    )
    (net (code "263") (name "ZZ.02.034") (class "Default")
      (node (ref "U$6") (pin "P$50") (pinfunction "B20_P$50") (pintype "bidirectional"))
    )
    (net (code "264") (name "ZZ.02.035") (class "Default")
      (node (ref "U$6") (pin "P$81") (pinfunction "C21_P$81") (pintype "bidirectional"))
    )
    (net (code "265") (name "ZZ.02.036") (class "Default")
      (node (ref "U$6") (pin "P$54") (pinfunction "B24_P$54") (pintype "bidirectional"))
    )
    (net (code "266") (name "ZZ.02.037") (class "Default")
      (node (ref "U$6") (pin "P$85") (pinfunction "C25_P$85") (pintype "bidirectional"))
    )
    (net (code "267") (name "ZZ.02.038") (class "Default")
      (node (ref "U$6") (pin "P$57") (pinfunction "B27_P$57") (pintype "bidirectional"))
    )
    (net (code "268") (name "ZZ.02.039") (class "Default")
      (node (ref "U$6") (pin "P$88") (pinfunction "C28_P$88") (pintype "bidirectional"))
    )
    (net (code "269") (name "ZZ.02.040") (class "Default")
      (node (ref "U$6") (pin "P$132") (pinfunction "E12_P$132") (pintype "bidirectional"))
    )
    (net (code "270") (name "ZZ.02.041") (class "Default")
      (node (ref "U$6") (pin "P$161") (pinfunction "F11_P$161") (pintype "bidirectional"))
    )
    (net (code "271") (name "ZZ.02.042") (class "Default")
      (node (ref "U$6") (pin "P$128") (pinfunction "E8_P$128") (pintype "bidirectional"))
    )
    (net (code "272") (name "ZZ.02.043") (class "Default")
      (node (ref "U$6") (pin "P$157") (pinfunction "F7_P$157") (pintype "bidirectional"))
    )
    (net (code "273") (name "ZZ.02.044") (class "Default")
      (node (ref "U$6") (pin "P$125") (pinfunction "E5_P$125") (pintype "bidirectional"))
    )
    (net (code "274") (name "ZZ.02.045") (class "Default")
      (node (ref "U$6") (pin "P$154") (pinfunction "F4_P$154") (pintype "bidirectional"))
    )
    (net (code "275") (name "ZZ.02.046") (class "Default")
      (node (ref "U$8") (pin "P$54") (pinfunction "B24_P$54") (pintype "bidirectional"))
    )
    (net (code "276") (name "ZZ.02.047") (class "Default")
      (node (ref "U$8") (pin "P$85") (pinfunction "C25_P$85") (pintype "bidirectional"))
    )
    (net (code "277") (name "ZZ.02.048") (class "Default")
      (node (ref "U$8") (pin "P$57") (pinfunction "B27_P$57") (pintype "bidirectional"))
    )
    (net (code "278") (name "ZZ.02.049") (class "Default")
      (node (ref "U$8") (pin "P$88") (pinfunction "C28_P$88") (pintype "bidirectional"))
    )
    (net (code "279") (name "ZZ.02.050") (class "Default")
      (node (ref "U$8") (pin "P$142") (pinfunction "E22_P$142") (pintype "bidirectional"))
    )
    (net (code "280") (name "ZZ.02.051") (class "Default")
      (node (ref "U$8") (pin "P$171") (pinfunction "F21_P$171") (pintype "bidirectional"))
    )
    (net (code "281") (name "ZZ.02.052") (class "Default")
      (node (ref "U$8") (pin "P$139") (pinfunction "E19_P$139") (pintype "bidirectional"))
    )
    (net (code "282") (name "ZZ.02.053") (class "Default")
      (node (ref "U$8") (pin "P$168") (pinfunction "F18_P$168") (pintype "bidirectional"))
    )
    (net (code "283") (name "ZZ.02.054") (class "Default")
      (node (ref "U$8") (pin "P$135") (pinfunction "E15_P$135") (pintype "bidirectional"))
    )
    (net (code "284") (name "ZZ.02.055") (class "Default")
      (node (ref "U$8") (pin "P$164") (pinfunction "F14_P$164") (pintype "bidirectional"))
    )
    (net (code "285") (name "ZZ.02.056") (class "Default")
      (node (ref "U$8") (pin "P$132") (pinfunction "E12_P$132") (pintype "bidirectional"))
    )
    (net (code "286") (name "ZZ.02.057") (class "Default")
      (node (ref "U$8") (pin "P$161") (pinfunction "F11_P$161") (pintype "bidirectional"))
    )
    (net (code "287") (name "ZZ.02.058") (class "Default")
      (node (ref "U$8") (pin "P$128") (pinfunction "E8_P$128") (pintype "bidirectional"))
    )
    (net (code "288") (name "ZZ.02.059") (class "Default")
      (node (ref "U$8") (pin "P$157") (pinfunction "F7_P$157") (pintype "bidirectional"))
    )
    (net (code "289") (name "ZZ.02.060") (class "Default")
      (node (ref "U$8") (pin "P$125") (pinfunction "E5_P$125") (pintype "bidirectional"))
    )
    (net (code "290") (name "ZZ.02.061") (class "Default")
      (node (ref "U$8") (pin "P$154") (pinfunction "F4_P$154") (pintype "bidirectional"))
    )
    (net (code "291") (name "ZZ.02.062") (class "Default")
      (node (ref "U$10") (pin "P$149") (pinfunction "E29_P$149") (pintype "bidirectional"))
    )
    (net (code "292") (name "ZZ.02.063") (class "Default")
      (node (ref "U$10") (pin "P$178") (pinfunction "F28_P$178") (pintype "bidirectional"))
    )
    (net (code "293") (name "ZZ.02.064") (class "Default")
      (node (ref "U$10") (pin "P$146") (pinfunction "E26_P$146") (pintype "bidirectional"))
    )
    (net (code "294") (name "ZZ.02.065") (class "Default")
      (node (ref "U$10") (pin "P$175") (pinfunction "F25_P$175") (pintype "bidirectional"))
    )
    (net (code "295") (name "ZZ.02.066") (class "Default")
      (node (ref "U$10") (pin "P$142") (pinfunction "E22_P$142") (pintype "bidirectional"))
    )
    (net (code "296") (name "ZZ.02.067") (class "Default")
      (node (ref "U$10") (pin "P$171") (pinfunction "F21_P$171") (pintype "bidirectional"))
    )
    (net (code "297") (name "ZZ.02.068") (class "Default")
      (node (ref "U$10") (pin "P$139") (pinfunction "E19_P$139") (pintype "bidirectional"))
    )
    (net (code "298") (name "ZZ.02.069") (class "Default")
      (node (ref "U$10") (pin "P$168") (pinfunction "F18_P$168") (pintype "bidirectional"))
    )
    (net (code "299") (name "ZZ.02.070") (class "Default")
      (node (ref "U$10") (pin "P$135") (pinfunction "E15_P$135") (pintype "bidirectional"))
    )
    (net (code "300") (name "ZZ.02.071") (class "Default")
      (node (ref "U$10") (pin "P$164") (pinfunction "F14_P$164") (pintype "bidirectional"))
    )
    (net (code "301") (name "ZZ.02.072") (class "Default")
      (node (ref "U$10") (pin "P$132") (pinfunction "E12_P$132") (pintype "bidirectional"))
    )
    (net (code "302") (name "ZZ.02.073") (class "Default")
      (node (ref "U$10") (pin "P$161") (pinfunction "F11_P$161") (pintype "bidirectional"))
    )
    (net (code "303") (name "ZZ.02.074") (class "Default")
      (node (ref "U$10") (pin "P$128") (pinfunction "E8_P$128") (pintype "bidirectional"))
    )
    (net (code "304") (name "ZZ.02.075") (class "Default")
      (node (ref "U$10") (pin "P$157") (pinfunction "F7_P$157") (pintype "bidirectional"))
    )
    (net (code "305") (name "ZZ.02.076") (class "Default")
      (node (ref "U$10") (pin "P$125") (pinfunction "E5_P$125") (pintype "bidirectional"))
    )
    (net (code "306") (name "ZZ.02.077") (class "Default")
      (node (ref "U$10") (pin "P$154") (pinfunction "F4_P$154") (pintype "bidirectional"))
    )
    (net (code "307") (name "ZZ.02.078") (class "Default")
      (node (ref "U$12") (pin "P$149") (pinfunction "E29_P$149") (pintype "bidirectional"))
    )
    (net (code "308") (name "ZZ.02.079") (class "Default")
      (node (ref "U$12") (pin "P$178") (pinfunction "F28_P$178") (pintype "bidirectional"))
    )
    (net (code "309") (name "ZZ.02.080") (class "Default")
      (node (ref "U$12") (pin "P$146") (pinfunction "E26_P$146") (pintype "bidirectional"))
    )
    (net (code "310") (name "ZZ.02.081") (class "Default")
      (node (ref "U$12") (pin "P$175") (pinfunction "F25_P$175") (pintype "bidirectional"))
    )
    (net (code "311") (name "ZZ.02.082") (class "Default")
      (node (ref "U$12") (pin "P$142") (pinfunction "E22_P$142") (pintype "bidirectional"))
    )
    (net (code "312") (name "ZZ.02.083") (class "Default")
      (node (ref "U$12") (pin "P$171") (pinfunction "F21_P$171") (pintype "bidirectional"))
    )
    (net (code "313") (name "ZZ.02.084") (class "Default")
      (node (ref "U$12") (pin "P$139") (pinfunction "E19_P$139") (pintype "bidirectional"))
    )
    (net (code "314") (name "ZZ.02.085") (class "Default")
      (node (ref "U$12") (pin "P$168") (pinfunction "F18_P$168") (pintype "bidirectional"))
    )
    (net (code "315") (name "ZZ.02.086") (class "Default")
      (node (ref "U$12") (pin "P$135") (pinfunction "E15_P$135") (pintype "bidirectional"))
    )
    (net (code "316") (name "ZZ.02.087") (class "Default")
      (node (ref "U$12") (pin "P$164") (pinfunction "F14_P$164") (pintype "bidirectional"))
    )
    (net (code "317") (name "ZZ.02.088") (class "Default")
      (node (ref "U$12") (pin "P$132") (pinfunction "E12_P$132") (pintype "bidirectional"))
    )
    (net (code "318") (name "ZZ.02.089") (class "Default")
      (node (ref "U$12") (pin "P$161") (pinfunction "F11_P$161") (pintype "bidirectional"))
    )
    (net (code "319") (name "ZZ.02.090") (class "Default")
      (node (ref "U$12") (pin "P$128") (pinfunction "E8_P$128") (pintype "bidirectional"))
    )
    (net (code "320") (name "ZZ.02.091") (class "Default")
      (node (ref "U$12") (pin "P$157") (pinfunction "F7_P$157") (pintype "bidirectional"))
    )
    (net (code "321") (name "ZZ.02.092") (class "Default")
      (node (ref "U$12") (pin "P$125") (pinfunction "E5_P$125") (pintype "bidirectional"))
    )
    (net (code "322") (name "ZZ.02.093") (class "Default")
      (node (ref "U$12") (pin "P$154") (pinfunction "F4_P$154") (pintype "bidirectional"))
    )
    (net (code "323") (name "ZZ.03.000") (class "Default")
      (node (ref "U$1") (pin "P$95") (pinfunction "D5_P$95") (pintype "bidirectional"))
    )
    (net (code "324") (name "ZZ.03.001") (class "Default")
      (node (ref "U$1") (pin "P$123") (pinfunction "E3_P$123") (pintype "bidirectional"))
    )
    (net (code "325") (name "ZZ.03.002") (class "Default")
      (node (ref "U$4") (pin "P$123") (pinfunction "E3_P$123") (pintype "bidirectional"))
    )
    (net (code "326") (name "ZZ.03.003") (class "Default")
      (node (ref "U$4") (pin "P$95") (pinfunction "D5_P$95") (pintype "bidirectional"))
    )
    (net (code "327") (name "ZZ.03.004") (class "Default")
      (node (ref "U$4") (pin "P$126") (pinfunction "E6_P$126") (pintype "bidirectional"))
    )
    (net (code "328") (name "ZZ.03.005") (class "Default")
      (node (ref "U$4") (pin "P$98") (pinfunction "D8_P$98") (pintype "bidirectional"))
    )
    (net (code "329") (name "ZZ.03.006") (class "Default")
      (node (ref "U$2") (pin "P$130") (pinfunction "E10_P$130") (pintype "bidirectional"))
    )
    (net (code "330") (name "ZZ.03.007") (class "Default")
      (node (ref "U$2") (pin "P$102") (pinfunction "D12_P$102") (pintype "bidirectional"))
    )
    (net (code "331") (name "ZZ.03.008") (class "Default")
      (node (ref "U$2") (pin "P$133") (pinfunction "E13_P$133") (pintype "bidirectional"))
    )
    (net (code "332") (name "ZZ.03.009") (class "Default")
      (node (ref "U$2") (pin "P$105") (pinfunction "D15_P$105") (pintype "bidirectional"))
    )
    (net (code "333") (name "ZZ.03.010") (class "Default")
      (node (ref "U$2") (pin "P$137") (pinfunction "E17_P$137") (pintype "bidirectional"))
    )
    (net (code "334") (name "ZZ.03.011") (class "Default")
      (node (ref "U$2") (pin "P$109") (pinfunction "D19_P$109") (pintype "bidirectional"))
    )
    (net (code "335") (name "ZZ.03.012") (class "Default")
      (node (ref "U$2") (pin "P$140") (pinfunction "E20_P$140") (pintype "bidirectional"))
    )
    (net (code "336") (name "ZZ.03.013") (class "Default")
      (node (ref "U$2") (pin "P$112") (pinfunction "D22_P$112") (pintype "bidirectional"))
    )
    (net (code "337") (name "ZZ.03.014") (class "Default")
      (node (ref "U$2") (pin "P$144") (pinfunction "E24_P$144") (pintype "bidirectional"))
    )
    (net (code "338") (name "ZZ.03.015") (class "Default")
      (node (ref "U$2") (pin "P$116") (pinfunction "D26_P$116") (pintype "bidirectional"))
    )
    (net (code "339") (name "ZZ.03.016") (class "Default")
      (node (ref "U$2") (pin "P$147") (pinfunction "E27_P$147") (pintype "bidirectional"))
    )
    (net (code "340") (name "ZZ.03.017") (class "Default")
      (node (ref "U$2") (pin "P$119") (pinfunction "D29_P$119") (pintype "bidirectional"))
    )
    (net (code "341") (name "ZZ.03.018") (class "Default")
      (node (ref "U$4") (pin "P$130") (pinfunction "E10_P$130") (pintype "bidirectional"))
    )
    (net (code "342") (name "ZZ.03.019") (class "Default")
      (node (ref "U$4") (pin "P$102") (pinfunction "D12_P$102") (pintype "bidirectional"))
    )
    (net (code "343") (name "ZZ.03.020") (class "Default")
      (node (ref "U$4") (pin "P$133") (pinfunction "E13_P$133") (pintype "bidirectional"))
    )
    (net (code "344") (name "ZZ.03.021") (class "Default")
      (node (ref "U$4") (pin "P$105") (pinfunction "D15_P$105") (pintype "bidirectional"))
    )
    (net (code "345") (name "ZZ.03.022") (class "Default")
      (node (ref "U$4") (pin "P$137") (pinfunction "E17_P$137") (pintype "bidirectional"))
    )
    (net (code "346") (name "ZZ.03.023") (class "Default")
      (node (ref "U$4") (pin "P$109") (pinfunction "D19_P$109") (pintype "bidirectional"))
    )
    (net (code "347") (name "ZZ.03.024") (class "Default")
      (node (ref "U$4") (pin "P$140") (pinfunction "E20_P$140") (pintype "bidirectional"))
    )
    (net (code "348") (name "ZZ.03.025") (class "Default")
      (node (ref "U$4") (pin "P$112") (pinfunction "D22_P$112") (pintype "bidirectional"))
    )
    (net (code "349") (name "ZZ.03.026") (class "Default")
      (node (ref "U$4") (pin "P$144") (pinfunction "E24_P$144") (pintype "bidirectional"))
    )
    (net (code "350") (name "ZZ.03.027") (class "Default")
      (node (ref "U$4") (pin "P$116") (pinfunction "D26_P$116") (pintype "bidirectional"))
    )
    (net (code "351") (name "ZZ.03.028") (class "Default")
      (node (ref "U$4") (pin "P$147") (pinfunction "E27_P$147") (pintype "bidirectional"))
    )
    (net (code "352") (name "ZZ.03.029") (class "Default")
      (node (ref "U$4") (pin "P$119") (pinfunction "D29_P$119") (pintype "bidirectional"))
    )
    (net (code "353") (name "ZZ.03.030") (class "Default")
      (node (ref "U$6") (pin "P$133") (pinfunction "E13_P$133") (pintype "bidirectional"))
    )
    (net (code "354") (name "ZZ.03.031") (class "Default")
      (node (ref "U$6") (pin "P$105") (pinfunction "D15_P$105") (pintype "bidirectional"))
    )
    (net (code "355") (name "ZZ.03.032") (class "Default")
      (node (ref "U$6") (pin "P$137") (pinfunction "E17_P$137") (pintype "bidirectional"))
    )
    (net (code "356") (name "ZZ.03.033") (class "Default")
      (node (ref "U$6") (pin "P$109") (pinfunction "D19_P$109") (pintype "bidirectional"))
    )
    (net (code "357") (name "ZZ.03.034") (class "Default")
      (node (ref "U$6") (pin "P$140") (pinfunction "E20_P$140") (pintype "bidirectional"))
    )
    (net (code "358") (name "ZZ.03.035") (class "Default")
      (node (ref "U$6") (pin "P$112") (pinfunction "D22_P$112") (pintype "bidirectional"))
    )
    (net (code "359") (name "ZZ.03.036") (class "Default")
      (node (ref "U$6") (pin "P$144") (pinfunction "E24_P$144") (pintype "bidirectional"))
    )
    (net (code "360") (name "ZZ.03.037") (class "Default")
      (node (ref "U$6") (pin "P$116") (pinfunction "D26_P$116") (pintype "bidirectional"))
    )
    (net (code "361") (name "ZZ.03.038") (class "Default")
      (node (ref "U$6") (pin "P$147") (pinfunction "E27_P$147") (pintype "bidirectional"))
    )
    (net (code "362") (name "ZZ.03.039") (class "Default")
      (node (ref "U$6") (pin "P$119") (pinfunction "D29_P$119") (pintype "bidirectional"))
    )
    (net (code "363") (name "ZZ.03.040") (class "Default")
      (node (ref "U$6") (pin "P$101") (pinfunction "D11_P$101") (pintype "bidirectional"))
    )
    (net (code "364") (name "ZZ.03.041") (class "Default")
      (node (ref "U$6") (pin "P$130") (pinfunction "E10_P$130") (pintype "bidirectional"))
    )
    (net (code "365") (name "ZZ.03.042") (class "Default")
      (node (ref "U$6") (pin "P$97") (pinfunction "D7_P$97") (pintype "bidirectional"))
    )
    (net (code "366") (name "ZZ.03.043") (class "Default")
      (node (ref "U$6") (pin "P$126") (pinfunction "E6_P$126") (pintype "bidirectional"))
    )
    (net (code "367") (name "ZZ.03.044") (class "Default")
      (node (ref "U$6") (pin "P$94") (pinfunction "D4_P$94") (pintype "bidirectional"))
    )
    (net (code "368") (name "ZZ.03.045") (class "Default")
      (node (ref "U$6") (pin "P$123") (pinfunction "E3_P$123") (pintype "bidirectional"))
    )
    (net (code "369") (name "ZZ.03.046") (class "Default")
      (node (ref "U$8") (pin "P$144") (pinfunction "E24_P$144") (pintype "bidirectional"))
    )
    (net (code "370") (name "ZZ.03.047") (class "Default")
      (node (ref "U$8") (pin "P$116") (pinfunction "D26_P$116") (pintype "bidirectional"))
    )
    (net (code "371") (name "ZZ.03.048") (class "Default")
      (node (ref "U$8") (pin "P$147") (pinfunction "E27_P$147") (pintype "bidirectional"))
    )
    (net (code "372") (name "ZZ.03.049") (class "Default")
      (node (ref "U$8") (pin "P$119") (pinfunction "D29_P$119") (pintype "bidirectional"))
    )
    (net (code "373") (name "ZZ.03.050") (class "Default")
      (node (ref "U$8") (pin "P$111") (pinfunction "D21_P$111") (pintype "bidirectional"))
    )
    (net (code "374") (name "ZZ.03.051") (class "Default")
      (node (ref "U$8") (pin "P$140") (pinfunction "E20_P$140") (pintype "bidirectional"))
    )
    (net (code "375") (name "ZZ.03.052") (class "Default")
      (node (ref "U$8") (pin "P$108") (pinfunction "D18_P$108") (pintype "bidirectional"))
    )
    (net (code "376") (name "ZZ.03.053") (class "Default")
      (node (ref "U$8") (pin "P$137") (pinfunction "E17_P$137") (pintype "bidirectional"))
    )
    (net (code "377") (name "ZZ.03.054") (class "Default")
      (node (ref "U$8") (pin "P$104") (pinfunction "D14_P$104") (pintype "bidirectional"))
    )
    (net (code "378") (name "ZZ.03.055") (class "Default")
      (node (ref "U$8") (pin "P$133") (pinfunction "E13_P$133") (pintype "bidirectional"))
    )
    (net (code "379") (name "ZZ.03.056") (class "Default")
      (node (ref "U$8") (pin "P$101") (pinfunction "D11_P$101") (pintype "bidirectional"))
    )
    (net (code "380") (name "ZZ.03.057") (class "Default")
      (node (ref "U$8") (pin "P$130") (pinfunction "E10_P$130") (pintype "bidirectional"))
    )
    (net (code "381") (name "ZZ.03.058") (class "Default")
      (node (ref "U$8") (pin "P$97") (pinfunction "D7_P$97") (pintype "bidirectional"))
    )
    (net (code "382") (name "ZZ.03.059") (class "Default")
      (node (ref "U$8") (pin "P$126") (pinfunction "E6_P$126") (pintype "bidirectional"))
    )
    (net (code "383") (name "ZZ.03.060") (class "Default")
      (node (ref "U$8") (pin "P$94") (pinfunction "D4_P$94") (pintype "bidirectional"))
    )
    (net (code "384") (name "ZZ.03.061") (class "Default")
      (node (ref "U$8") (pin "P$123") (pinfunction "E3_P$123") (pintype "bidirectional"))
    )
    (net (code "385") (name "ZZ.03.062") (class "Default")
      (node (ref "U$10") (pin "P$118") (pinfunction "D28_P$118") (pintype "bidirectional"))
    )
    (net (code "386") (name "ZZ.03.063") (class "Default")
      (node (ref "U$10") (pin "P$147") (pinfunction "E27_P$147") (pintype "bidirectional"))
    )
    (net (code "387") (name "ZZ.03.064") (class "Default")
      (node (ref "U$10") (pin "P$115") (pinfunction "D25_P$115") (pintype "bidirectional"))
    )
    (net (code "388") (name "ZZ.03.065") (class "Default")
      (node (ref "U$10") (pin "P$144") (pinfunction "E24_P$144") (pintype "bidirectional"))
    )
    (net (code "389") (name "ZZ.03.066") (class "Default")
      (node (ref "U$10") (pin "P$111") (pinfunction "D21_P$111") (pintype "bidirectional"))
    )
    (net (code "390") (name "ZZ.03.067") (class "Default")
      (node (ref "U$10") (pin "P$140") (pinfunction "E20_P$140") (pintype "bidirectional"))
    )
    (net (code "391") (name "ZZ.03.068") (class "Default")
      (node (ref "U$10") (pin "P$108") (pinfunction "D18_P$108") (pintype "bidirectional"))
    )
    (net (code "392") (name "ZZ.03.069") (class "Default")
      (node (ref "U$10") (pin "P$137") (pinfunction "E17_P$137") (pintype "bidirectional"))
    )
    (net (code "393") (name "ZZ.03.070") (class "Default")
      (node (ref "U$10") (pin "P$104") (pinfunction "D14_P$104") (pintype "bidirectional"))
    )
    (net (code "394") (name "ZZ.03.071") (class "Default")
      (node (ref "U$10") (pin "P$133") (pinfunction "E13_P$133") (pintype "bidirectional"))
    )
    (net (code "395") (name "ZZ.03.072") (class "Default")
      (node (ref "U$10") (pin "P$101") (pinfunction "D11_P$101") (pintype "bidirectional"))
    )
    (net (code "396") (name "ZZ.03.073") (class "Default")
      (node (ref "U$10") (pin "P$130") (pinfunction "E10_P$130") (pintype "bidirectional"))
    )
    (net (code "397") (name "ZZ.03.074") (class "Default")
      (node (ref "U$10") (pin "P$97") (pinfunction "D7_P$97") (pintype "bidirectional"))
    )
    (net (code "398") (name "ZZ.03.075") (class "Default")
      (node (ref "U$10") (pin "P$126") (pinfunction "E6_P$126") (pintype "bidirectional"))
    )
    (net (code "399") (name "ZZ.03.076") (class "Default")
      (node (ref "U$10") (pin "P$94") (pinfunction "D4_P$94") (pintype "bidirectional"))
    )
    (net (code "400") (name "ZZ.03.077") (class "Default")
      (node (ref "U$10") (pin "P$123") (pinfunction "E3_P$123") (pintype "bidirectional"))
    )
    (net (code "401") (name "ZZ.03.078") (class "Default")
      (node (ref "U$12") (pin "P$118") (pinfunction "D28_P$118") (pintype "bidirectional"))
    )
    (net (code "402") (name "ZZ.03.079") (class "Default")
      (node (ref "U$12") (pin "P$147") (pinfunction "E27_P$147") (pintype "bidirectional"))
    )
    (net (code "403") (name "ZZ.03.080") (class "Default")
      (node (ref "U$12") (pin "P$115") (pinfunction "D25_P$115") (pintype "bidirectional"))
    )
    (net (code "404") (name "ZZ.03.081") (class "Default")
      (node (ref "U$12") (pin "P$144") (pinfunction "E24_P$144") (pintype "bidirectional"))
    )
    (net (code "405") (name "ZZ.03.082") (class "Default")
      (node (ref "U$12") (pin "P$111") (pinfunction "D21_P$111") (pintype "bidirectional"))
    )
    (net (code "406") (name "ZZ.03.083") (class "Default")
      (node (ref "U$12") (pin "P$140") (pinfunction "E20_P$140") (pintype "bidirectional"))
    )
    (net (code "407") (name "ZZ.03.084") (class "Default")
      (node (ref "U$12") (pin "P$108") (pinfunction "D18_P$108") (pintype "bidirectional"))
    )
    (net (code "408") (name "ZZ.03.085") (class "Default")
      (node (ref "U$12") (pin "P$137") (pinfunction "E17_P$137") (pintype "bidirectional"))
    )
    (net (code "409") (name "ZZ.03.086") (class "Default")
      (node (ref "U$12") (pin "P$104") (pinfunction "D14_P$104") (pintype "bidirectional"))
    )
    (net (code "410") (name "ZZ.03.087") (class "Default")
      (node (ref "U$12") (pin "P$133") (pinfunction "E13_P$133") (pintype "bidirectional"))
    )
    (net (code "411") (name "ZZ.03.088") (class "Default")
      (node (ref "U$12") (pin "P$101") (pinfunction "D11_P$101") (pintype "bidirectional"))
    )
    (net (code "412") (name "ZZ.03.089") (class "Default")
      (node (ref "U$12") (pin "P$130") (pinfunction "E10_P$130") (pintype "bidirectional"))
    )
    (net (code "413") (name "ZZ.03.090") (class "Default")
      (node (ref "U$12") (pin "P$97") (pinfunction "D7_P$97") (pintype "bidirectional"))
    )
    (net (code "414") (name "ZZ.03.091") (class "Default")
      (node (ref "U$12") (pin "P$126") (pinfunction "E6_P$126") (pintype "bidirectional"))
    )
    (net (code "415") (name "ZZ.03.092") (class "Default")
      (node (ref "U$12") (pin "P$94") (pinfunction "D4_P$94") (pintype "bidirectional"))
    )
    (net (code "416") (name "ZZ.03.093") (class "Default")
      (node (ref "U$12") (pin "P$123") (pinfunction "E3_P$123") (pintype "bidirectional"))
    )
    (net (code "417") (name "ZZ.04.000") (class "Default")
      (node (ref "U$1") (pin "P$94") (pinfunction "D4_P$94") (pintype "bidirectional"))
    )
    (net (code "418") (name "ZZ.04.001") (class "Default")
      (node (ref "U$1") (pin "P$93") (pinfunction "D3_P$93") (pintype "bidirectional"))
    )
    (net (code "419") (name "ZZ.04.002") (class "Default")
      (node (ref "U$4") (pin "P$93") (pinfunction "D3_P$93") (pintype "bidirectional"))
    )
    (net (code "420") (name "ZZ.04.003") (class "Default")
      (node (ref "U$4") (pin "P$94") (pinfunction "D4_P$94") (pintype "bidirectional"))
    )
    (net (code "421") (name "ZZ.04.004") (class "Default")
      (node (ref "U$4") (pin "P$96") (pinfunction "D6_P$96") (pintype "bidirectional"))
    )
    (net (code "422") (name "ZZ.04.005") (class "Default")
      (node (ref "U$4") (pin "P$97") (pinfunction "D7_P$97") (pintype "bidirectional"))
    )
    (net (code "423") (name "ZZ.04.006") (class "Default")
      (node (ref "U$2") (pin "P$100") (pinfunction "D10_P$100") (pintype "bidirectional"))
    )
    (net (code "424") (name "ZZ.04.007") (class "Default")
      (node (ref "U$2") (pin "P$101") (pinfunction "D11_P$101") (pintype "bidirectional"))
    )
    (net (code "425") (name "ZZ.04.008") (class "Default")
      (node (ref "U$2") (pin "P$103") (pinfunction "D13_P$103") (pintype "bidirectional"))
    )
    (net (code "426") (name "ZZ.04.009") (class "Default")
      (node (ref "U$2") (pin "P$104") (pinfunction "D14_P$104") (pintype "bidirectional"))
    )
    (net (code "427") (name "ZZ.04.010") (class "Default")
      (node (ref "U$2") (pin "P$107") (pinfunction "D17_P$107") (pintype "bidirectional"))
    )
    (net (code "428") (name "ZZ.04.011") (class "Default")
      (node (ref "U$2") (pin "P$108") (pinfunction "D18_P$108") (pintype "bidirectional"))
    )
    (net (code "429") (name "ZZ.04.012") (class "Default")
      (node (ref "U$2") (pin "P$110") (pinfunction "D20_P$110") (pintype "bidirectional"))
    )
    (net (code "430") (name "ZZ.04.013") (class "Default")
      (node (ref "U$2") (pin "P$111") (pinfunction "D21_P$111") (pintype "bidirectional"))
    )
    (net (code "431") (name "ZZ.04.014") (class "Default")
      (node (ref "U$2") (pin "P$114") (pinfunction "D24_P$114") (pintype "bidirectional"))
    )
    (net (code "432") (name "ZZ.04.015") (class "Default")
      (node (ref "U$2") (pin "P$115") (pinfunction "D25_P$115") (pintype "bidirectional"))
    )
    (net (code "433") (name "ZZ.04.016") (class "Default")
      (node (ref "U$2") (pin "P$117") (pinfunction "D27_P$117") (pintype "bidirectional"))
    )
    (net (code "434") (name "ZZ.04.017") (class "Default")
      (node (ref "U$2") (pin "P$118") (pinfunction "D28_P$118") (pintype "bidirectional"))
    )
    (net (code "435") (name "ZZ.04.018") (class "Default")
      (node (ref "U$4") (pin "P$100") (pinfunction "D10_P$100") (pintype "bidirectional"))
    )
    (net (code "436") (name "ZZ.04.019") (class "Default")
      (node (ref "U$4") (pin "P$101") (pinfunction "D11_P$101") (pintype "bidirectional"))
    )
    (net (code "437") (name "ZZ.04.020") (class "Default")
      (node (ref "U$4") (pin "P$103") (pinfunction "D13_P$103") (pintype "bidirectional"))
    )
    (net (code "438") (name "ZZ.04.021") (class "Default")
      (node (ref "U$4") (pin "P$104") (pinfunction "D14_P$104") (pintype "bidirectional"))
    )
    (net (code "439") (name "ZZ.04.022") (class "Default")
      (node (ref "U$4") (pin "P$107") (pinfunction "D17_P$107") (pintype "bidirectional"))
    )
    (net (code "440") (name "ZZ.04.023") (class "Default")
      (node (ref "U$4") (pin "P$108") (pinfunction "D18_P$108") (pintype "bidirectional"))
    )
    (net (code "441") (name "ZZ.04.024") (class "Default")
      (node (ref "U$4") (pin "P$110") (pinfunction "D20_P$110") (pintype "bidirectional"))
    )
    (net (code "442") (name "ZZ.04.025") (class "Default")
      (node (ref "U$4") (pin "P$111") (pinfunction "D21_P$111") (pintype "bidirectional"))
    )
    (net (code "443") (name "ZZ.04.026") (class "Default")
      (node (ref "U$4") (pin "P$114") (pinfunction "D24_P$114") (pintype "bidirectional"))
    )
    (net (code "444") (name "ZZ.04.027") (class "Default")
      (node (ref "U$4") (pin "P$115") (pinfunction "D25_P$115") (pintype "bidirectional"))
    )
    (net (code "445") (name "ZZ.04.028") (class "Default")
      (node (ref "U$4") (pin "P$117") (pinfunction "D27_P$117") (pintype "bidirectional"))
    )
    (net (code "446") (name "ZZ.04.029") (class "Default")
      (node (ref "U$4") (pin "P$118") (pinfunction "D28_P$118") (pintype "bidirectional"))
    )
    (net (code "447") (name "ZZ.04.030") (class "Default")
      (node (ref "U$6") (pin "P$103") (pinfunction "D13_P$103") (pintype "bidirectional"))
    )
    (net (code "448") (name "ZZ.04.031") (class "Default")
      (node (ref "U$6") (pin "P$104") (pinfunction "D14_P$104") (pintype "bidirectional"))
    )
    (net (code "449") (name "ZZ.04.032") (class "Default")
      (node (ref "U$6") (pin "P$107") (pinfunction "D17_P$107") (pintype "bidirectional"))
    )
    (net (code "450") (name "ZZ.04.033") (class "Default")
      (node (ref "U$6") (pin "P$108") (pinfunction "D18_P$108") (pintype "bidirectional"))
    )
    (net (code "451") (name "ZZ.04.034") (class "Default")
      (node (ref "U$6") (pin "P$110") (pinfunction "D20_P$110") (pintype "bidirectional"))
    )
    (net (code "452") (name "ZZ.04.035") (class "Default")
      (node (ref "U$6") (pin "P$111") (pinfunction "D21_P$111") (pintype "bidirectional"))
    )
    (net (code "453") (name "ZZ.04.036") (class "Default")
      (node (ref "U$6") (pin "P$114") (pinfunction "D24_P$114") (pintype "bidirectional"))
    )
    (net (code "454") (name "ZZ.04.037") (class "Default")
      (node (ref "U$6") (pin "P$115") (pinfunction "D25_P$115") (pintype "bidirectional"))
    )
    (net (code "455") (name "ZZ.04.038") (class "Default")
      (node (ref "U$6") (pin "P$117") (pinfunction "D27_P$117") (pintype "bidirectional"))
    )
    (net (code "456") (name "ZZ.04.039") (class "Default")
      (node (ref "U$6") (pin "P$118") (pinfunction "D28_P$118") (pintype "bidirectional"))
    )
    (net (code "457") (name "ZZ.04.040") (class "Default")
      (node (ref "U$6") (pin "P$102") (pinfunction "D12_P$102") (pintype "bidirectional"))
    )
    (net (code "458") (name "ZZ.04.041") (class "Default")
      (node (ref "U$6") (pin "P$100") (pinfunction "D10_P$100") (pintype "bidirectional"))
    )
    (net (code "459") (name "ZZ.04.042") (class "Default")
      (node (ref "U$6") (pin "P$98") (pinfunction "D8_P$98") (pintype "bidirectional"))
    )
    (net (code "460") (name "ZZ.04.043") (class "Default")
      (node (ref "U$6") (pin "P$96") (pinfunction "D6_P$96") (pintype "bidirectional"))
    )
    (net (code "461") (name "ZZ.04.044") (class "Default")
      (node (ref "U$6") (pin "P$95") (pinfunction "D5_P$95") (pintype "bidirectional"))
    )
    (net (code "462") (name "ZZ.04.045") (class "Default")
      (node (ref "U$6") (pin "P$93") (pinfunction "D3_P$93") (pintype "bidirectional"))
    )
    (net (code "463") (name "ZZ.04.046") (class "Default")
      (node (ref "U$8") (pin "P$114") (pinfunction "D24_P$114") (pintype "bidirectional"))
    )
    (net (code "464") (name "ZZ.04.047") (class "Default")
      (node (ref "U$8") (pin "P$115") (pinfunction "D25_P$115") (pintype "bidirectional"))
    )
    (net (code "465") (name "ZZ.04.048") (class "Default")
      (node (ref "U$8") (pin "P$117") (pinfunction "D27_P$117") (pintype "bidirectional"))
    )
    (net (code "466") (name "ZZ.04.049") (class "Default")
      (node (ref "U$8") (pin "P$118") (pinfunction "D28_P$118") (pintype "bidirectional"))
    )
    (net (code "467") (name "ZZ.04.050") (class "Default")
      (node (ref "U$8") (pin "P$112") (pinfunction "D22_P$112") (pintype "bidirectional"))
    )
    (net (code "468") (name "ZZ.04.051") (class "Default")
      (node (ref "U$8") (pin "P$110") (pinfunction "D20_P$110") (pintype "bidirectional"))
    )
    (net (code "469") (name "ZZ.04.052") (class "Default")
      (node (ref "U$8") (pin "P$109") (pinfunction "D19_P$109") (pintype "bidirectional"))
    )
    (net (code "470") (name "ZZ.04.053") (class "Default")
      (node (ref "U$8") (pin "P$107") (pinfunction "D17_P$107") (pintype "bidirectional"))
    )
    (net (code "471") (name "ZZ.04.054") (class "Default")
      (node (ref "U$8") (pin "P$105") (pinfunction "D15_P$105") (pintype "bidirectional"))
    )
    (net (code "472") (name "ZZ.04.055") (class "Default")
      (node (ref "U$8") (pin "P$103") (pinfunction "D13_P$103") (pintype "bidirectional"))
    )
    (net (code "473") (name "ZZ.04.056") (class "Default")
      (node (ref "U$8") (pin "P$102") (pinfunction "D12_P$102") (pintype "bidirectional"))
    )
    (net (code "474") (name "ZZ.04.057") (class "Default")
      (node (ref "U$8") (pin "P$100") (pinfunction "D10_P$100") (pintype "bidirectional"))
    )
    (net (code "475") (name "ZZ.04.058") (class "Default")
      (node (ref "U$8") (pin "P$98") (pinfunction "D8_P$98") (pintype "bidirectional"))
    )
    (net (code "476") (name "ZZ.04.059") (class "Default")
      (node (ref "U$8") (pin "P$96") (pinfunction "D6_P$96") (pintype "bidirectional"))
    )
    (net (code "477") (name "ZZ.04.060") (class "Default")
      (node (ref "U$8") (pin "P$95") (pinfunction "D5_P$95") (pintype "bidirectional"))
    )
    (net (code "478") (name "ZZ.04.061") (class "Default")
      (node (ref "U$8") (pin "P$93") (pinfunction "D3_P$93") (pintype "bidirectional"))
    )
    (net (code "479") (name "ZZ.04.062") (class "Default")
      (node (ref "U$10") (pin "P$119") (pinfunction "D29_P$119") (pintype "bidirectional"))
    )
    (net (code "480") (name "ZZ.04.063") (class "Default")
      (node (ref "U$10") (pin "P$117") (pinfunction "D27_P$117") (pintype "bidirectional"))
    )
    (net (code "481") (name "ZZ.04.064") (class "Default")
      (node (ref "U$10") (pin "P$116") (pinfunction "D26_P$116") (pintype "bidirectional"))
    )
    (net (code "482") (name "ZZ.04.065") (class "Default")
      (node (ref "U$10") (pin "P$114") (pinfunction "D24_P$114") (pintype "bidirectional"))
    )
    (net (code "483") (name "ZZ.04.066") (class "Default")
      (node (ref "U$10") (pin "P$112") (pinfunction "D22_P$112") (pintype "bidirectional"))
    )
    (net (code "484") (name "ZZ.04.067") (class "Default")
      (node (ref "U$10") (pin "P$110") (pinfunction "D20_P$110") (pintype "bidirectional"))
    )
    (net (code "485") (name "ZZ.04.068") (class "Default")
      (node (ref "U$10") (pin "P$109") (pinfunction "D19_P$109") (pintype "bidirectional"))
    )
    (net (code "486") (name "ZZ.04.069") (class "Default")
      (node (ref "U$10") (pin "P$107") (pinfunction "D17_P$107") (pintype "bidirectional"))
    )
    (net (code "487") (name "ZZ.04.070") (class "Default")
      (node (ref "U$10") (pin "P$105") (pinfunction "D15_P$105") (pintype "bidirectional"))
    )
    (net (code "488") (name "ZZ.04.071") (class "Default")
      (node (ref "U$10") (pin "P$103") (pinfunction "D13_P$103") (pintype "bidirectional"))
    )
    (net (code "489") (name "ZZ.04.072") (class "Default")
      (node (ref "U$10") (pin "P$102") (pinfunction "D12_P$102") (pintype "bidirectional"))
    )
    (net (code "490") (name "ZZ.04.073") (class "Default")
      (node (ref "U$10") (pin "P$100") (pinfunction "D10_P$100") (pintype "bidirectional"))
    )
    (net (code "491") (name "ZZ.04.074") (class "Default")
      (node (ref "U$10") (pin "P$98") (pinfunction "D8_P$98") (pintype "bidirectional"))
    )
    (net (code "492") (name "ZZ.04.075") (class "Default")
      (node (ref "U$10") (pin "P$96") (pinfunction "D6_P$96") (pintype "bidirectional"))
    )
    (net (code "493") (name "ZZ.04.076") (class "Default")
      (node (ref "U$10") (pin "P$95") (pinfunction "D5_P$95") (pintype "bidirectional"))
    )
    (net (code "494") (name "ZZ.04.077") (class "Default")
      (node (ref "U$10") (pin "P$93") (pinfunction "D3_P$93") (pintype "bidirectional"))
    )
    (net (code "495") (name "ZZ.04.078") (class "Default")
      (node (ref "U$12") (pin "P$119") (pinfunction "D29_P$119") (pintype "bidirectional"))
    )
    (net (code "496") (name "ZZ.04.079") (class "Default")
      (node (ref "U$12") (pin "P$117") (pinfunction "D27_P$117") (pintype "bidirectional"))
    )
    (net (code "497") (name "ZZ.04.080") (class "Default")
      (node (ref "U$12") (pin "P$116") (pinfunction "D26_P$116") (pintype "bidirectional"))
    )
    (net (code "498") (name "ZZ.04.081") (class "Default")
      (node (ref "U$12") (pin "P$114") (pinfunction "D24_P$114") (pintype "bidirectional"))
    )
    (net (code "499") (name "ZZ.04.082") (class "Default")
      (node (ref "U$12") (pin "P$112") (pinfunction "D22_P$112") (pintype "bidirectional"))
    )
    (net (code "500") (name "ZZ.04.083") (class "Default")
      (node (ref "U$12") (pin "P$110") (pinfunction "D20_P$110") (pintype "bidirectional"))
    )
    (net (code "501") (name "ZZ.04.084") (class "Default")
      (node (ref "U$12") (pin "P$109") (pinfunction "D19_P$109") (pintype "bidirectional"))
    )
    (net (code "502") (name "ZZ.04.085") (class "Default")
      (node (ref "U$12") (pin "P$107") (pinfunction "D17_P$107") (pintype "bidirectional"))
    )
    (net (code "503") (name "ZZ.04.086") (class "Default")
      (node (ref "U$12") (pin "P$105") (pinfunction "D15_P$105") (pintype "bidirectional"))
    )
    (net (code "504") (name "ZZ.04.087") (class "Default")
      (node (ref "U$12") (pin "P$103") (pinfunction "D13_P$103") (pintype "bidirectional"))
    )
    (net (code "505") (name "ZZ.04.088") (class "Default")
      (node (ref "U$12") (pin "P$102") (pinfunction "D12_P$102") (pintype "bidirectional"))
    )
    (net (code "506") (name "ZZ.04.089") (class "Default")
      (node (ref "U$12") (pin "P$100") (pinfunction "D10_P$100") (pintype "bidirectional"))
    )
    (net (code "507") (name "ZZ.04.090") (class "Default")
      (node (ref "U$12") (pin "P$98") (pinfunction "D8_P$98") (pintype "bidirectional"))
    )
    (net (code "508") (name "ZZ.04.091") (class "Default")
      (node (ref "U$12") (pin "P$96") (pinfunction "D6_P$96") (pintype "bidirectional"))
    )
    (net (code "509") (name "ZZ.04.092") (class "Default")
      (node (ref "U$12") (pin "P$95") (pinfunction "D5_P$95") (pintype "bidirectional"))
    )
    (net (code "510") (name "ZZ.04.093") (class "Default")
      (node (ref "U$12") (pin "P$93") (pinfunction "D3_P$93") (pintype "bidirectional"))
    )
    (net (code "511") (name "ZZ.05.000") (class "Default")
      (node (ref "U$1") (pin "P$124") (pinfunction "E4_P$124") (pintype "bidirectional"))
    )
    (net (code "512") (name "ZZ.05.001") (class "Default")
      (node (ref "U$1") (pin "P$155") (pinfunction "F5_P$155") (pintype "bidirectional"))
    )
    (net (code "513") (name "ZZ.05.002") (class "Default")
      (node (ref "U$4") (pin "P$153") (pinfunction "F3_P$153") (pintype "bidirectional"))
    )
    (net (code "514") (name "ZZ.05.003") (class "Default")
      (node (ref "U$4") (pin "P$155") (pinfunction "F5_P$155") (pintype "bidirectional"))
    )
    (net (code "515") (name "ZZ.05.004") (class "Default")
      (node (ref "U$4") (pin "P$156") (pinfunction "F6_P$156") (pintype "bidirectional"))
    )
    (net (code "516") (name "ZZ.05.005") (class "Default")
      (node (ref "U$4") (pin "P$158") (pinfunction "F8_P$158") (pintype "bidirectional"))
    )
    (net (code "517") (name "ZZ.05.006") (class "Default")
      (node (ref "U$2") (pin "P$131") (pinfunction "E11_P$131") (pintype "bidirectional"))
    )
    (net (code "518") (name "ZZ.05.007") (class "Default")
      (node (ref "U$2") (pin "P$162") (pinfunction "F12_P$162") (pintype "bidirectional"))
    )
    (net (code "519") (name "ZZ.05.008") (class "Default")
      (node (ref "U$2") (pin "P$134") (pinfunction "E14_P$134") (pintype "bidirectional"))
    )
    (net (code "520") (name "ZZ.05.009") (class "Default")
      (node (ref "U$2") (pin "P$165") (pinfunction "F15_P$165") (pintype "bidirectional"))
    )
    (net (code "521") (name "ZZ.05.010") (class "Default")
      (node (ref "U$2") (pin "P$138") (pinfunction "E18_P$138") (pintype "bidirectional"))
    )
    (net (code "522") (name "ZZ.05.011") (class "Default")
      (node (ref "U$2") (pin "P$169") (pinfunction "F19_P$169") (pintype "bidirectional"))
    )
    (net (code "523") (name "ZZ.05.012") (class "Default")
      (node (ref "U$2") (pin "P$141") (pinfunction "E21_P$141") (pintype "bidirectional"))
    )
    (net (code "524") (name "ZZ.05.013") (class "Default")
      (node (ref "U$2") (pin "P$172") (pinfunction "F22_P$172") (pintype "bidirectional"))
    )
    (net (code "525") (name "ZZ.05.014") (class "Default")
      (node (ref "U$2") (pin "P$145") (pinfunction "E25_P$145") (pintype "bidirectional"))
    )
    (net (code "526") (name "ZZ.05.015") (class "Default")
      (node (ref "U$2") (pin "P$176") (pinfunction "F26_P$176") (pintype "bidirectional"))
    )
    (net (code "527") (name "ZZ.05.016") (class "Default")
      (node (ref "U$2") (pin "P$148") (pinfunction "E28_P$148") (pintype "bidirectional"))
    )
    (net (code "528") (name "ZZ.05.017") (class "Default")
      (node (ref "U$2") (pin "P$179") (pinfunction "F29_P$179") (pintype "bidirectional"))
    )
    (net (code "529") (name "ZZ.05.018") (class "Default")
      (node (ref "U$4") (pin "P$160") (pinfunction "F10_P$160") (pintype "bidirectional"))
    )
    (net (code "530") (name "ZZ.05.019") (class "Default")
      (node (ref "U$4") (pin "P$162") (pinfunction "F12_P$162") (pintype "bidirectional"))
    )
    (net (code "531") (name "ZZ.05.020") (class "Default")
      (node (ref "U$4") (pin "P$163") (pinfunction "F13_P$163") (pintype "bidirectional"))
    )
    (net (code "532") (name "ZZ.05.021") (class "Default")
      (node (ref "U$4") (pin "P$165") (pinfunction "F15_P$165") (pintype "bidirectional"))
    )
    (net (code "533") (name "ZZ.05.022") (class "Default")
      (node (ref "U$4") (pin "P$167") (pinfunction "F17_P$167") (pintype "bidirectional"))
    )
    (net (code "534") (name "ZZ.05.023") (class "Default")
      (node (ref "U$4") (pin "P$169") (pinfunction "F19_P$169") (pintype "bidirectional"))
    )
    (net (code "535") (name "ZZ.05.024") (class "Default")
      (node (ref "U$4") (pin "P$170") (pinfunction "F20_P$170") (pintype "bidirectional"))
    )
    (net (code "536") (name "ZZ.05.025") (class "Default")
      (node (ref "U$4") (pin "P$172") (pinfunction "F22_P$172") (pintype "bidirectional"))
    )
    (net (code "537") (name "ZZ.05.026") (class "Default")
      (node (ref "U$4") (pin "P$174") (pinfunction "F24_P$174") (pintype "bidirectional"))
    )
    (net (code "538") (name "ZZ.05.027") (class "Default")
      (node (ref "U$4") (pin "P$176") (pinfunction "F26_P$176") (pintype "bidirectional"))
    )
    (net (code "539") (name "ZZ.05.028") (class "Default")
      (node (ref "U$4") (pin "P$177") (pinfunction "F27_P$177") (pintype "bidirectional"))
    )
    (net (code "540") (name "ZZ.05.029") (class "Default")
      (node (ref "U$4") (pin "P$179") (pinfunction "F29_P$179") (pintype "bidirectional"))
    )
    (net (code "541") (name "ZZ.05.030") (class "Default")
      (node (ref "U$6") (pin "P$163") (pinfunction "F13_P$163") (pintype "bidirectional"))
    )
    (net (code "542") (name "ZZ.05.031") (class "Default")
      (node (ref "U$6") (pin "P$165") (pinfunction "F15_P$165") (pintype "bidirectional"))
    )
    (net (code "543") (name "ZZ.05.032") (class "Default")
      (node (ref "U$6") (pin "P$167") (pinfunction "F17_P$167") (pintype "bidirectional"))
    )
    (net (code "544") (name "ZZ.05.033") (class "Default")
      (node (ref "U$6") (pin "P$169") (pinfunction "F19_P$169") (pintype "bidirectional"))
    )
    (net (code "545") (name "ZZ.05.034") (class "Default")
      (node (ref "U$6") (pin "P$170") (pinfunction "F20_P$170") (pintype "bidirectional"))
    )
    (net (code "546") (name "ZZ.05.035") (class "Default")
      (node (ref "U$6") (pin "P$172") (pinfunction "F22_P$172") (pintype "bidirectional"))
    )
    (net (code "547") (name "ZZ.05.036") (class "Default")
      (node (ref "U$6") (pin "P$174") (pinfunction "F24_P$174") (pintype "bidirectional"))
    )
    (net (code "548") (name "ZZ.05.037") (class "Default")
      (node (ref "U$6") (pin "P$176") (pinfunction "F26_P$176") (pintype "bidirectional"))
    )
    (net (code "549") (name "ZZ.05.038") (class "Default")
      (node (ref "U$6") (pin "P$177") (pinfunction "F27_P$177") (pintype "bidirectional"))
    )
    (net (code "550") (name "ZZ.05.039") (class "Default")
      (node (ref "U$6") (pin "P$179") (pinfunction "F29_P$179") (pintype "bidirectional"))
    )
    (net (code "551") (name "ZZ.05.040") (class "Default")
      (node (ref "U$6") (pin "P$41") (pinfunction "B11_P$41") (pintype "bidirectional"))
    )
    (net (code "552") (name "ZZ.05.041") (class "Default")
      (node (ref "U$6") (pin "P$71") (pinfunction "C11_P$71") (pintype "bidirectional"))
    )
    (net (code "553") (name "ZZ.05.042") (class "Default")
      (node (ref "U$6") (pin "P$37") (pinfunction "B7_P$37") (pintype "bidirectional"))
    )
    (net (code "554") (name "ZZ.05.043") (class "Default")
      (node (ref "U$6") (pin "P$67") (pinfunction "C7_P$67") (pintype "bidirectional"))
    )
    (net (code "555") (name "ZZ.05.044") (class "Default")
      (node (ref "U$6") (pin "P$34") (pinfunction "B4_P$34") (pintype "bidirectional"))
    )
    (net (code "556") (name "ZZ.05.045") (class "Default")
      (node (ref "U$6") (pin "P$64") (pinfunction "C4_P$64") (pintype "bidirectional"))
    )
    (net (code "557") (name "ZZ.05.046") (class "Default")
      (node (ref "U$8") (pin "P$174") (pinfunction "F24_P$174") (pintype "bidirectional"))
    )
    (net (code "558") (name "ZZ.05.047") (class "Default")
      (node (ref "U$8") (pin "P$176") (pinfunction "F26_P$176") (pintype "bidirectional"))
    )
    (net (code "559") (name "ZZ.05.048") (class "Default")
      (node (ref "U$8") (pin "P$177") (pinfunction "F27_P$177") (pintype "bidirectional"))
    )
    (net (code "560") (name "ZZ.05.049") (class "Default")
      (node (ref "U$8") (pin "P$179") (pinfunction "F29_P$179") (pintype "bidirectional"))
    )
    (net (code "561") (name "ZZ.05.050") (class "Default")
      (node (ref "U$8") (pin "P$51") (pinfunction "B21_P$51") (pintype "bidirectional"))
    )
    (net (code "562") (name "ZZ.05.051") (class "Default")
      (node (ref "U$8") (pin "P$81") (pinfunction "C21_P$81") (pintype "bidirectional"))
    )
    (net (code "563") (name "ZZ.05.052") (class "Default")
      (node (ref "U$8") (pin "P$48") (pinfunction "B18_P$48") (pintype "bidirectional"))
    )
    (net (code "564") (name "ZZ.05.053") (class "Default")
      (node (ref "U$8") (pin "P$78") (pinfunction "C18_P$78") (pintype "bidirectional"))
    )
    (net (code "565") (name "ZZ.05.054") (class "Default")
      (node (ref "U$8") (pin "P$44") (pinfunction "B14_P$44") (pintype "bidirectional"))
    )
    (net (code "566") (name "ZZ.05.055") (class "Default")
      (node (ref "U$8") (pin "P$74") (pinfunction "C14_P$74") (pintype "bidirectional"))
    )
    (net (code "567") (name "ZZ.05.056") (class "Default")
      (node (ref "U$8") (pin "P$41") (pinfunction "B11_P$41") (pintype "bidirectional"))
    )
    (net (code "568") (name "ZZ.05.057") (class "Default")
      (node (ref "U$8") (pin "P$71") (pinfunction "C11_P$71") (pintype "bidirectional"))
    )
    (net (code "569") (name "ZZ.05.058") (class "Default")
      (node (ref "U$8") (pin "P$37") (pinfunction "B7_P$37") (pintype "bidirectional"))
    )
    (net (code "570") (name "ZZ.05.059") (class "Default")
      (node (ref "U$8") (pin "P$67") (pinfunction "C7_P$67") (pintype "bidirectional"))
    )
    (net (code "571") (name "ZZ.05.060") (class "Default")
      (node (ref "U$8") (pin "P$34") (pinfunction "B4_P$34") (pintype "bidirectional"))
    )
    (net (code "572") (name "ZZ.05.061") (class "Default")
      (node (ref "U$8") (pin "P$64") (pinfunction "C4_P$64") (pintype "bidirectional"))
    )
    (net (code "573") (name "ZZ.05.062") (class "Default")
      (node (ref "U$10") (pin "P$58") (pinfunction "B28_P$58") (pintype "bidirectional"))
    )
    (net (code "574") (name "ZZ.05.063") (class "Default")
      (node (ref "U$10") (pin "P$88") (pinfunction "C28_P$88") (pintype "bidirectional"))
    )
    (net (code "575") (name "ZZ.05.064") (class "Default")
      (node (ref "U$10") (pin "P$55") (pinfunction "B25_P$55") (pintype "bidirectional"))
    )
    (net (code "576") (name "ZZ.05.065") (class "Default")
      (node (ref "U$10") (pin "P$85") (pinfunction "C25_P$85") (pintype "bidirectional"))
    )
    (net (code "577") (name "ZZ.05.066") (class "Default")
      (node (ref "U$10") (pin "P$51") (pinfunction "B21_P$51") (pintype "bidirectional"))
    )
    (net (code "578") (name "ZZ.05.067") (class "Default")
      (node (ref "U$10") (pin "P$81") (pinfunction "C21_P$81") (pintype "bidirectional"))
    )
    (net (code "579") (name "ZZ.05.068") (class "Default")
      (node (ref "U$10") (pin "P$48") (pinfunction "B18_P$48") (pintype "bidirectional"))
    )
    (net (code "580") (name "ZZ.05.069") (class "Default")
      (node (ref "U$10") (pin "P$78") (pinfunction "C18_P$78") (pintype "bidirectional"))
    )
    (net (code "581") (name "ZZ.05.070") (class "Default")
      (node (ref "U$10") (pin "P$44") (pinfunction "B14_P$44") (pintype "bidirectional"))
    )
    (net (code "582") (name "ZZ.05.071") (class "Default")
      (node (ref "U$10") (pin "P$74") (pinfunction "C14_P$74") (pintype "bidirectional"))
    )
    (net (code "583") (name "ZZ.05.072") (class "Default")
      (node (ref "U$10") (pin "P$41") (pinfunction "B11_P$41") (pintype "bidirectional"))
    )
    (net (code "584") (name "ZZ.05.073") (class "Default")
      (node (ref "U$10") (pin "P$71") (pinfunction "C11_P$71") (pintype "bidirectional"))
    )
    (net (code "585") (name "ZZ.05.074") (class "Default")
      (node (ref "U$10") (pin "P$37") (pinfunction "B7_P$37") (pintype "bidirectional"))
    )
    (net (code "586") (name "ZZ.05.075") (class "Default")
      (node (ref "U$10") (pin "P$67") (pinfunction "C7_P$67") (pintype "bidirectional"))
    )
    (net (code "587") (name "ZZ.05.076") (class "Default")
      (node (ref "U$10") (pin "P$34") (pinfunction "B4_P$34") (pintype "bidirectional"))
    )
    (net (code "588") (name "ZZ.05.077") (class "Default")
      (node (ref "U$10") (pin "P$64") (pinfunction "C4_P$64") (pintype "bidirectional"))
    )
    (net (code "589") (name "ZZ.05.078") (class "Default")
      (node (ref "U$12") (pin "P$58") (pinfunction "B28_P$58") (pintype "bidirectional"))
    )
    (net (code "590") (name "ZZ.05.079") (class "Default")
      (node (ref "U$12") (pin "P$87") (pinfunction "C27_P$87") (pintype "bidirectional"))
    )
    (net (code "591") (name "ZZ.05.080") (class "Default")
      (node (ref "U$12") (pin "P$55") (pinfunction "B25_P$55") (pintype "bidirectional"))
    )
    (net (code "592") (name "ZZ.05.081") (class "Default")
      (node (ref "U$12") (pin "P$84") (pinfunction "C24_P$84") (pintype "bidirectional"))
    )
    (net (code "593") (name "ZZ.05.082") (class "Default")
      (node (ref "U$12") (pin "P$51") (pinfunction "B21_P$51") (pintype "bidirectional"))
    )
    (net (code "594") (name "ZZ.05.083") (class "Default")
      (node (ref "U$12") (pin "P$80") (pinfunction "C20_P$80") (pintype "bidirectional"))
    )
    (net (code "595") (name "ZZ.05.084") (class "Default")
      (node (ref "U$12") (pin "P$48") (pinfunction "B18_P$48") (pintype "bidirectional"))
    )
    (net (code "596") (name "ZZ.05.085") (class "Default")
      (node (ref "U$12") (pin "P$77") (pinfunction "C17_P$77") (pintype "bidirectional"))
    )
    (net (code "597") (name "ZZ.05.086") (class "Default")
      (node (ref "U$12") (pin "P$44") (pinfunction "B14_P$44") (pintype "bidirectional"))
    )
    (net (code "598") (name "ZZ.05.087") (class "Default")
      (node (ref "U$12") (pin "P$73") (pinfunction "C13_P$73") (pintype "bidirectional"))
    )
    (net (code "599") (name "ZZ.05.088") (class "Default")
      (node (ref "U$12") (pin "P$41") (pinfunction "B11_P$41") (pintype "bidirectional"))
    )
    (net (code "600") (name "ZZ.05.089") (class "Default")
      (node (ref "U$12") (pin "P$70") (pinfunction "C10_P$70") (pintype "bidirectional"))
    )
    (net (code "601") (name "ZZ.05.090") (class "Default")
      (node (ref "U$12") (pin "P$37") (pinfunction "B7_P$37") (pintype "bidirectional"))
    )
    (net (code "602") (name "ZZ.05.091") (class "Default")
      (node (ref "U$12") (pin "P$66") (pinfunction "C6_P$66") (pintype "bidirectional"))
    )
    (net (code "603") (name "ZZ.05.092") (class "Default")
      (node (ref "U$12") (pin "P$34") (pinfunction "B4_P$34") (pintype "bidirectional"))
    )
    (net (code "604") (name "ZZ.05.093") (class "Default")
      (node (ref "U$12") (pin "P$63") (pinfunction "C3_P$63") (pintype "bidirectional"))
    )
    (net (code "605") (name "ZZ.06.000") (class "Default")
      (node (ref "U$1") (pin "P$122") (pinfunction "E2_P$122") (pintype "bidirectional"))
    )
    (net (code "606") (name "ZZ.06.001") (class "Default")
      (node (ref "U$1") (pin "P$125") (pinfunction "E5_P$125") (pintype "bidirectional"))
    )
    (net (code "607") (name "ZZ.06.002") (class "Default")
      (node (ref "U$4") (pin "P$122") (pinfunction "E2_P$122") (pintype "bidirectional"))
    )
    (net (code "608") (name "ZZ.06.003") (class "Default")
      (node (ref "U$4") (pin "P$125") (pinfunction "E5_P$125") (pintype "bidirectional"))
    )
    (net (code "609") (name "ZZ.06.004") (class "Default")
      (node (ref "U$4") (pin "P$152") (pinfunction "F2_P$152") (pintype "bidirectional"))
    )
    (net (code "610") (name "ZZ.06.005") (class "Default")
      (node (ref "U$4") (pin "P$128") (pinfunction "E8_P$128") (pintype "bidirectional"))
    )
    (net (code "611") (name "ZZ.06.006") (class "Default")
      (node (ref "U$2") (pin "P$129") (pinfunction "E9_P$129") (pintype "bidirectional"))
    )
    (net (code "612") (name "ZZ.06.007") (class "Default")
      (node (ref "U$2") (pin "P$132") (pinfunction "E12_P$132") (pintype "bidirectional"))
    )
    (net (code "613") (name "ZZ.06.008") (class "Default")
      (node (ref "U$2") (pin "P$159") (pinfunction "F9_P$159") (pintype "bidirectional"))
    )
    (net (code "614") (name "ZZ.06.009") (class "Default")
      (node (ref "U$2") (pin "P$135") (pinfunction "E15_P$135") (pintype "bidirectional"))
    )
    (net (code "615") (name "ZZ.06.010") (class "Default")
      (node (ref "U$2") (pin "P$136") (pinfunction "E16_P$136") (pintype "bidirectional"))
    )
    (net (code "616") (name "ZZ.06.011") (class "Default")
      (node (ref "U$2") (pin "P$139") (pinfunction "E19_P$139") (pintype "bidirectional"))
    )
    (net (code "617") (name "ZZ.06.012") (class "Default")
      (node (ref "U$2") (pin "P$166") (pinfunction "F16_P$166") (pintype "bidirectional"))
    )
    (net (code "618") (name "ZZ.06.013") (class "Default")
      (node (ref "U$2") (pin "P$142") (pinfunction "E22_P$142") (pintype "bidirectional"))
    )
    (net (code "619") (name "ZZ.06.014") (class "Default")
      (node (ref "U$2") (pin "P$143") (pinfunction "E23_P$143") (pintype "bidirectional"))
    )
    (net (code "620") (name "ZZ.06.015") (class "Default")
      (node (ref "U$2") (pin "P$146") (pinfunction "E26_P$146") (pintype "bidirectional"))
    )
    (net (code "621") (name "ZZ.06.016") (class "Default")
      (node (ref "U$2") (pin "P$173") (pinfunction "F23_P$173") (pintype "bidirectional"))
    )
    (net (code "622") (name "ZZ.06.017") (class "Default")
      (node (ref "U$2") (pin "P$149") (pinfunction "E29_P$149") (pintype "bidirectional"))
    )
    (net (code "623") (name "ZZ.06.018") (class "Default")
      (node (ref "U$4") (pin "P$129") (pinfunction "E9_P$129") (pintype "bidirectional"))
    )
    (net (code "624") (name "ZZ.06.019") (class "Default")
      (node (ref "U$4") (pin "P$132") (pinfunction "E12_P$132") (pintype "bidirectional"))
    )
    (net (code "625") (name "ZZ.06.020") (class "Default")
      (node (ref "U$4") (pin "P$159") (pinfunction "F9_P$159") (pintype "bidirectional"))
    )
    (net (code "626") (name "ZZ.06.021") (class "Default")
      (node (ref "U$4") (pin "P$135") (pinfunction "E15_P$135") (pintype "bidirectional"))
    )
    (net (code "627") (name "ZZ.06.022") (class "Default")
      (node (ref "U$4") (pin "P$136") (pinfunction "E16_P$136") (pintype "bidirectional"))
    )
    (net (code "628") (name "ZZ.06.023") (class "Default")
      (node (ref "U$4") (pin "P$139") (pinfunction "E19_P$139") (pintype "bidirectional"))
    )
    (net (code "629") (name "ZZ.06.024") (class "Default")
      (node (ref "U$4") (pin "P$166") (pinfunction "F16_P$166") (pintype "bidirectional"))
    )
    (net (code "630") (name "ZZ.06.025") (class "Default")
      (node (ref "U$4") (pin "P$142") (pinfunction "E22_P$142") (pintype "bidirectional"))
    )
    (net (code "631") (name "ZZ.06.026") (class "Default")
      (node (ref "U$4") (pin "P$143") (pinfunction "E23_P$143") (pintype "bidirectional"))
    )
    (net (code "632") (name "ZZ.06.027") (class "Default")
      (node (ref "U$4") (pin "P$146") (pinfunction "E26_P$146") (pintype "bidirectional"))
    )
    (net (code "633") (name "ZZ.06.028") (class "Default")
      (node (ref "U$4") (pin "P$173") (pinfunction "F23_P$173") (pintype "bidirectional"))
    )
    (net (code "634") (name "ZZ.06.029") (class "Default")
      (node (ref "U$4") (pin "P$149") (pinfunction "E29_P$149") (pintype "bidirectional"))
    )
    (net (code "635") (name "ZZ.06.030") (class "Default")
      (node (ref "U$6") (pin "P$159") (pinfunction "F9_P$159") (pintype "bidirectional"))
    )
    (net (code "636") (name "ZZ.06.031") (class "Default")
      (node (ref "U$6") (pin "P$135") (pinfunction "E15_P$135") (pintype "bidirectional"))
    )
    (net (code "637") (name "ZZ.06.032") (class "Default")
      (node (ref "U$6") (pin "P$136") (pinfunction "E16_P$136") (pintype "bidirectional"))
    )
    (net (code "638") (name "ZZ.06.033") (class "Default")
      (node (ref "U$6") (pin "P$139") (pinfunction "E19_P$139") (pintype "bidirectional"))
    )
    (net (code "639") (name "ZZ.06.034") (class "Default")
      (node (ref "U$6") (pin "P$166") (pinfunction "F16_P$166") (pintype "bidirectional"))
    )
    (net (code "640") (name "ZZ.06.035") (class "Default")
      (node (ref "U$6") (pin "P$142") (pinfunction "E22_P$142") (pintype "bidirectional"))
    )
    (net (code "641") (name "ZZ.06.036") (class "Default")
      (node (ref "U$6") (pin "P$143") (pinfunction "E23_P$143") (pintype "bidirectional"))
    )
    (net (code "642") (name "ZZ.06.037") (class "Default")
      (node (ref "U$6") (pin "P$146") (pinfunction "E26_P$146") (pintype "bidirectional"))
    )
    (net (code "643") (name "ZZ.06.038") (class "Default")
      (node (ref "U$6") (pin "P$173") (pinfunction "F23_P$173") (pintype "bidirectional"))
    )
    (net (code "644") (name "ZZ.06.039") (class "Default")
      (node (ref "U$6") (pin "P$149") (pinfunction "E29_P$149") (pintype "bidirectional"))
    )
    (net (code "645") (name "ZZ.06.040") (class "Default")
      (node (ref "U$6") (pin "P$72") (pinfunction "C12_P$72") (pintype "bidirectional"))
    )
    (net (code "646") (name "ZZ.06.041") (class "Default")
      (node (ref "U$6") (pin "P$40") (pinfunction "B10_P$40") (pintype "bidirectional"))
    )
    (net (code "647") (name "ZZ.06.042") (class "Default")
      (node (ref "U$6") (pin "P$68") (pinfunction "C8_P$68") (pintype "bidirectional"))
    )
    (net (code "648") (name "ZZ.06.043") (class "Default")
      (node (ref "U$6") (pin "P$36") (pinfunction "B6_P$36") (pintype "bidirectional"))
    )
    (net (code "649") (name "ZZ.06.044") (class "Default")
      (node (ref "U$6") (pin "P$65") (pinfunction "C5_P$65") (pintype "bidirectional"))
    )
    (net (code "650") (name "ZZ.06.045") (class "Default")
      (node (ref "U$6") (pin "P$33") (pinfunction "B3_P$33") (pintype "bidirectional"))
    )
    (net (code "651") (name "ZZ.06.046") (class "Default")
      (node (ref "U$8") (pin "P$143") (pinfunction "E23_P$143") (pintype "bidirectional"))
    )
    (net (code "652") (name "ZZ.06.047") (class "Default")
      (node (ref "U$8") (pin "P$146") (pinfunction "E26_P$146") (pintype "bidirectional"))
    )
    (net (code "653") (name "ZZ.06.048") (class "Default")
      (node (ref "U$8") (pin "P$173") (pinfunction "F23_P$173") (pintype "bidirectional"))
    )
    (net (code "654") (name "ZZ.06.049") (class "Default")
      (node (ref "U$8") (pin "P$149") (pinfunction "E29_P$149") (pintype "bidirectional"))
    )
    (net (code "655") (name "ZZ.06.050") (class "Default")
      (node (ref "U$8") (pin "P$82") (pinfunction "C22_P$82") (pintype "bidirectional"))
    )
    (net (code "656") (name "ZZ.06.051") (class "Default")
      (node (ref "U$8") (pin "P$50") (pinfunction "B20_P$50") (pintype "bidirectional"))
    )
    (net (code "657") (name "ZZ.06.052") (class "Default")
      (node (ref "U$8") (pin "P$79") (pinfunction "C19_P$79") (pintype "bidirectional"))
    )
    (net (code "658") (name "ZZ.06.053") (class "Default")
      (node (ref "U$8") (pin "P$47") (pinfunction "B17_P$47") (pintype "bidirectional"))
    )
    (net (code "659") (name "ZZ.06.054") (class "Default")
      (node (ref "U$8") (pin "P$75") (pinfunction "C15_P$75") (pintype "bidirectional"))
    )
    (net (code "660") (name "ZZ.06.055") (class "Default")
      (node (ref "U$8") (pin "P$43") (pinfunction "B13_P$43") (pintype "bidirectional"))
    )
    (net (code "661") (name "ZZ.06.056") (class "Default")
      (node (ref "U$8") (pin "P$72") (pinfunction "C12_P$72") (pintype "bidirectional"))
    )
    (net (code "662") (name "ZZ.06.057") (class "Default")
      (node (ref "U$8") (pin "P$40") (pinfunction "B10_P$40") (pintype "bidirectional"))
    )
    (net (code "663") (name "ZZ.06.058") (class "Default")
      (node (ref "U$8") (pin "P$68") (pinfunction "C8_P$68") (pintype "bidirectional"))
    )
    (net (code "664") (name "ZZ.06.059") (class "Default")
      (node (ref "U$8") (pin "P$36") (pinfunction "B6_P$36") (pintype "bidirectional"))
    )
    (net (code "665") (name "ZZ.06.060") (class "Default")
      (node (ref "U$8") (pin "P$65") (pinfunction "C5_P$65") (pintype "bidirectional"))
    )
    (net (code "666") (name "ZZ.06.061") (class "Default")
      (node (ref "U$8") (pin "P$33") (pinfunction "B3_P$33") (pintype "bidirectional"))
    )
    (net (code "667") (name "ZZ.06.062") (class "Default")
      (node (ref "U$10") (pin "P$89") (pinfunction "C29_P$89") (pintype "bidirectional"))
    )
    (net (code "668") (name "ZZ.06.063") (class "Default")
      (node (ref "U$10") (pin "P$57") (pinfunction "B27_P$57") (pintype "bidirectional"))
    )
    (net (code "669") (name "ZZ.06.064") (class "Default")
      (node (ref "U$10") (pin "P$86") (pinfunction "C26_P$86") (pintype "bidirectional"))
    )
    (net (code "670") (name "ZZ.06.065") (class "Default")
      (node (ref "U$10") (pin "P$54") (pinfunction "B24_P$54") (pintype "bidirectional"))
    )
    (net (code "671") (name "ZZ.06.066") (class "Default")
      (node (ref "U$10") (pin "P$82") (pinfunction "C22_P$82") (pintype "bidirectional"))
    )
    (net (code "672") (name "ZZ.06.067") (class "Default")
      (node (ref "U$10") (pin "P$50") (pinfunction "B20_P$50") (pintype "bidirectional"))
    )
    (net (code "673") (name "ZZ.06.068") (class "Default")
      (node (ref "U$10") (pin "P$79") (pinfunction "C19_P$79") (pintype "bidirectional"))
    )
    (net (code "674") (name "ZZ.06.069") (class "Default")
      (node (ref "U$10") (pin "P$47") (pinfunction "B17_P$47") (pintype "bidirectional"))
    )
    (net (code "675") (name "ZZ.06.070") (class "Default")
      (node (ref "U$10") (pin "P$75") (pinfunction "C15_P$75") (pintype "bidirectional"))
    )
    (net (code "676") (name "ZZ.06.071") (class "Default")
      (node (ref "U$10") (pin "P$43") (pinfunction "B13_P$43") (pintype "bidirectional"))
    )
    (net (code "677") (name "ZZ.06.072") (class "Default")
      (node (ref "U$10") (pin "P$72") (pinfunction "C12_P$72") (pintype "bidirectional"))
    )
    (net (code "678") (name "ZZ.06.073") (class "Default")
      (node (ref "U$10") (pin "P$40") (pinfunction "B10_P$40") (pintype "bidirectional"))
    )
    (net (code "679") (name "ZZ.06.074") (class "Default")
      (node (ref "U$10") (pin "P$68") (pinfunction "C8_P$68") (pintype "bidirectional"))
    )
    (net (code "680") (name "ZZ.06.075") (class "Default")
      (node (ref "U$10") (pin "P$36") (pinfunction "B6_P$36") (pintype "bidirectional"))
    )
    (net (code "681") (name "ZZ.06.076") (class "Default")
      (node (ref "U$10") (pin "P$65") (pinfunction "C5_P$65") (pintype "bidirectional"))
    )
    (net (code "682") (name "ZZ.06.077") (class "Default")
      (node (ref "U$10") (pin "P$33") (pinfunction "B3_P$33") (pintype "bidirectional"))
    )
    (net (code "683") (name "ZZ.06.078") (class "Default")
      (node (ref "U$12") (pin "P$89") (pinfunction "C29_P$89") (pintype "bidirectional"))
    )
    (net (code "684") (name "ZZ.06.079") (class "Default")
      (node (ref "U$12") (pin "P$57") (pinfunction "B27_P$57") (pintype "bidirectional"))
    )
    (net (code "685") (name "ZZ.06.080") (class "Default")
      (node (ref "U$12") (pin "P$86") (pinfunction "C26_P$86") (pintype "bidirectional"))
    )
    (net (code "686") (name "ZZ.06.081") (class "Default")
      (node (ref "U$12") (pin "P$54") (pinfunction "B24_P$54") (pintype "bidirectional"))
    )
    (net (code "687") (name "ZZ.06.082") (class "Default")
      (node (ref "U$12") (pin "P$82") (pinfunction "C22_P$82") (pintype "bidirectional"))
    )
    (net (code "688") (name "ZZ.06.083") (class "Default")
      (node (ref "U$12") (pin "P$50") (pinfunction "B20_P$50") (pintype "bidirectional"))
    )
    (net (code "689") (name "ZZ.06.084") (class "Default")
      (node (ref "U$12") (pin "P$79") (pinfunction "C19_P$79") (pintype "bidirectional"))
    )
    (net (code "690") (name "ZZ.06.085") (class "Default")
      (node (ref "U$12") (pin "P$47") (pinfunction "B17_P$47") (pintype "bidirectional"))
    )
    (net (code "691") (name "ZZ.06.086") (class "Default")
      (node (ref "U$12") (pin "P$75") (pinfunction "C15_P$75") (pintype "bidirectional"))
    )
    (net (code "692") (name "ZZ.06.087") (class "Default")
      (node (ref "U$12") (pin "P$43") (pinfunction "B13_P$43") (pintype "bidirectional"))
    )
    (net (code "693") (name "ZZ.06.088") (class "Default")
      (node (ref "U$12") (pin "P$72") (pinfunction "C12_P$72") (pintype "bidirectional"))
    )
    (net (code "694") (name "ZZ.06.089") (class "Default")
      (node (ref "U$12") (pin "P$40") (pinfunction "B10_P$40") (pintype "bidirectional"))
    )
    (net (code "695") (name "ZZ.06.090") (class "Default")
      (node (ref "U$12") (pin "P$68") (pinfunction "C8_P$68") (pintype "bidirectional"))
    )
    (net (code "696") (name "ZZ.06.091") (class "Default")
      (node (ref "U$12") (pin "P$36") (pinfunction "B6_P$36") (pintype "bidirectional"))
    )
    (net (code "697") (name "ZZ.06.092") (class "Default")
      (node (ref "U$12") (pin "P$65") (pinfunction "C5_P$65") (pintype "bidirectional"))
    )
    (net (code "698") (name "ZZ.06.093") (class "Default")
      (node (ref "U$12") (pin "P$33") (pinfunction "B3_P$33") (pintype "bidirectional"))
    )
    (net (code "699") (name "ZZ.07.000") (class "Default")
      (node (ref "U$1") (pin "P$153") (pinfunction "F3_P$153") (pintype "bidirectional"))
    )
    (net (code "700") (name "ZZ.07.001") (class "Default")
      (node (ref "U$1") (pin "P$154") (pinfunction "F4_P$154") (pintype "bidirectional"))
    )
    (net (code "701") (name "ZZ.07.002") (class "Default")
      (node (ref "U$4") (pin "P$124") (pinfunction "E4_P$124") (pintype "bidirectional"))
    )
    (net (code "702") (name "ZZ.07.003") (class "Default")
      (node (ref "U$4") (pin "P$154") (pinfunction "F4_P$154") (pintype "bidirectional"))
    )
    (net (code "703") (name "ZZ.07.004") (class "Default")
      (node (ref "U$4") (pin "P$127") (pinfunction "E7_P$127") (pintype "bidirectional"))
    )
    (net (code "704") (name "ZZ.07.005") (class "Default")
      (node (ref "U$4") (pin "P$157") (pinfunction "F7_P$157") (pintype "bidirectional"))
    )
    (net (code "705") (name "ZZ.07.006") (class "Default")
      (node (ref "U$2") (pin "P$160") (pinfunction "F10_P$160") (pintype "bidirectional"))
    )
    (net (code "706") (name "ZZ.07.007") (class "Default")
      (node (ref "U$2") (pin "P$161") (pinfunction "F11_P$161") (pintype "bidirectional"))
    )
    (net (code "707") (name "ZZ.07.008") (class "Default")
      (node (ref "U$2") (pin "P$163") (pinfunction "F13_P$163") (pintype "bidirectional"))
    )
    (net (code "708") (name "ZZ.07.009") (class "Default")
      (node (ref "U$2") (pin "P$164") (pinfunction "F14_P$164") (pintype "bidirectional"))
    )
    (net (code "709") (name "ZZ.07.010") (class "Default")
      (node (ref "U$2") (pin "P$167") (pinfunction "F17_P$167") (pintype "bidirectional"))
    )
    (net (code "710") (name "ZZ.07.011") (class "Default")
      (node (ref "U$2") (pin "P$168") (pinfunction "F18_P$168") (pintype "bidirectional"))
    )
    (net (code "711") (name "ZZ.07.012") (class "Default")
      (node (ref "U$2") (pin "P$170") (pinfunction "F20_P$170") (pintype "bidirectional"))
    )
    (net (code "712") (name "ZZ.07.013") (class "Default")
      (node (ref "U$2") (pin "P$171") (pinfunction "F21_P$171") (pintype "bidirectional"))
    )
    (net (code "713") (name "ZZ.07.014") (class "Default")
      (node (ref "U$2") (pin "P$174") (pinfunction "F24_P$174") (pintype "bidirectional"))
    )
    (net (code "714") (name "ZZ.07.015") (class "Default")
      (node (ref "U$2") (pin "P$175") (pinfunction "F25_P$175") (pintype "bidirectional"))
    )
    (net (code "715") (name "ZZ.07.016") (class "Default")
      (node (ref "U$2") (pin "P$177") (pinfunction "F27_P$177") (pintype "bidirectional"))
    )
    (net (code "716") (name "ZZ.07.017") (class "Default")
      (node (ref "U$2") (pin "P$178") (pinfunction "F28_P$178") (pintype "bidirectional"))
    )
    (net (code "717") (name "ZZ.07.018") (class "Default")
      (node (ref "U$4") (pin "P$131") (pinfunction "E11_P$131") (pintype "bidirectional"))
    )
    (net (code "718") (name "ZZ.07.019") (class "Default")
      (node (ref "U$4") (pin "P$161") (pinfunction "F11_P$161") (pintype "bidirectional"))
    )
    (net (code "719") (name "ZZ.07.020") (class "Default")
      (node (ref "U$4") (pin "P$134") (pinfunction "E14_P$134") (pintype "bidirectional"))
    )
    (net (code "720") (name "ZZ.07.021") (class "Default")
      (node (ref "U$4") (pin "P$164") (pinfunction "F14_P$164") (pintype "bidirectional"))
    )
    (net (code "721") (name "ZZ.07.022") (class "Default")
      (node (ref "U$4") (pin "P$138") (pinfunction "E18_P$138") (pintype "bidirectional"))
    )
    (net (code "722") (name "ZZ.07.023") (class "Default")
      (node (ref "U$4") (pin "P$168") (pinfunction "F18_P$168") (pintype "bidirectional"))
    )
    (net (code "723") (name "ZZ.07.024") (class "Default")
      (node (ref "U$4") (pin "P$141") (pinfunction "E21_P$141") (pintype "bidirectional"))
    )
    (net (code "724") (name "ZZ.07.025") (class "Default")
      (node (ref "U$4") (pin "P$171") (pinfunction "F21_P$171") (pintype "bidirectional"))
    )
    (net (code "725") (name "ZZ.07.026") (class "Default")
      (node (ref "U$4") (pin "P$145") (pinfunction "E25_P$145") (pintype "bidirectional"))
    )
    (net (code "726") (name "ZZ.07.027") (class "Default")
      (node (ref "U$4") (pin "P$175") (pinfunction "F25_P$175") (pintype "bidirectional"))
    )
    (net (code "727") (name "ZZ.07.028") (class "Default")
      (node (ref "U$4") (pin "P$148") (pinfunction "E28_P$148") (pintype "bidirectional"))
    )
    (net (code "728") (name "ZZ.07.029") (class "Default")
      (node (ref "U$4") (pin "P$178") (pinfunction "F28_P$178") (pintype "bidirectional"))
    )
    (net (code "729") (name "ZZ.07.030") (class "Default")
      (node (ref "U$6") (pin "P$134") (pinfunction "E14_P$134") (pintype "bidirectional"))
    )
    (net (code "730") (name "ZZ.07.031") (class "Default")
      (node (ref "U$6") (pin "P$164") (pinfunction "F14_P$164") (pintype "bidirectional"))
    )
    (net (code "731") (name "ZZ.07.032") (class "Default")
      (node (ref "U$6") (pin "P$138") (pinfunction "E18_P$138") (pintype "bidirectional"))
    )
    (net (code "732") (name "ZZ.07.033") (class "Default")
      (node (ref "U$6") (pin "P$168") (pinfunction "F18_P$168") (pintype "bidirectional"))
    )
    (net (code "733") (name "ZZ.07.034") (class "Default")
      (node (ref "U$6") (pin "P$141") (pinfunction "E21_P$141") (pintype "bidirectional"))
    )
    (net (code "734") (name "ZZ.07.035") (class "Default")
      (node (ref "U$6") (pin "P$171") (pinfunction "F21_P$171") (pintype "bidirectional"))
    )
    (net (code "735") (name "ZZ.07.036") (class "Default")
      (node (ref "U$6") (pin "P$145") (pinfunction "E25_P$145") (pintype "bidirectional"))
    )
    (net (code "736") (name "ZZ.07.037") (class "Default")
      (node (ref "U$6") (pin "P$175") (pinfunction "F25_P$175") (pintype "bidirectional"))
    )
    (net (code "737") (name "ZZ.07.038") (class "Default")
      (node (ref "U$6") (pin "P$148") (pinfunction "E28_P$148") (pintype "bidirectional"))
    )
    (net (code "738") (name "ZZ.07.039") (class "Default")
      (node (ref "U$6") (pin "P$178") (pinfunction "F28_P$178") (pintype "bidirectional"))
    )
    (net (code "739") (name "ZZ.07.040") (class "Default")
      (node (ref "U$6") (pin "P$42") (pinfunction "B12_P$42") (pintype "bidirectional"))
    )
    (net (code "740") (name "ZZ.07.041") (class "Default")
      (node (ref "U$6") (pin "P$70") (pinfunction "C10_P$70") (pintype "bidirectional"))
    )
    (net (code "741") (name "ZZ.07.042") (class "Default")
      (node (ref "U$6") (pin "P$38") (pinfunction "B8_P$38") (pintype "bidirectional"))
    )
    (net (code "742") (name "ZZ.07.043") (class "Default")
      (node (ref "U$6") (pin "P$66") (pinfunction "C6_P$66") (pintype "bidirectional"))
    )
    (net (code "743") (name "ZZ.07.044") (class "Default")
      (node (ref "U$6") (pin "P$35") (pinfunction "B5_P$35") (pintype "bidirectional"))
    )
    (net (code "744") (name "ZZ.07.045") (class "Default")
      (node (ref "U$6") (pin "P$63") (pinfunction "C3_P$63") (pintype "bidirectional"))
    )
    (net (code "745") (name "ZZ.07.046") (class "Default")
      (node (ref "U$8") (pin "P$145") (pinfunction "E25_P$145") (pintype "bidirectional"))
    )
    (net (code "746") (name "ZZ.07.047") (class "Default")
      (node (ref "U$8") (pin "P$175") (pinfunction "F25_P$175") (pintype "bidirectional"))
    )
    (net (code "747") (name "ZZ.07.048") (class "Default")
      (node (ref "U$8") (pin "P$148") (pinfunction "E28_P$148") (pintype "bidirectional"))
    )
    (net (code "748") (name "ZZ.07.049") (class "Default")
      (node (ref "U$8") (pin "P$178") (pinfunction "F28_P$178") (pintype "bidirectional"))
    )
    (net (code "749") (name "ZZ.07.050") (class "Default")
      (node (ref "U$8") (pin "P$52") (pinfunction "B22_P$52") (pintype "bidirectional"))
    )
    (net (code "750") (name "ZZ.07.051") (class "Default")
      (node (ref "U$8") (pin "P$80") (pinfunction "C20_P$80") (pintype "bidirectional"))
    )
    (net (code "751") (name "ZZ.07.052") (class "Default")
      (node (ref "U$8") (pin "P$49") (pinfunction "B19_P$49") (pintype "bidirectional"))
    )
    (net (code "752") (name "ZZ.07.053") (class "Default")
      (node (ref "U$8") (pin "P$77") (pinfunction "C17_P$77") (pintype "bidirectional"))
    )
    (net (code "753") (name "ZZ.07.054") (class "Default")
      (node (ref "U$8") (pin "P$45") (pinfunction "B15_P$45") (pintype "bidirectional"))
    )
    (net (code "754") (name "ZZ.07.055") (class "Default")
      (node (ref "U$8") (pin "P$73") (pinfunction "C13_P$73") (pintype "bidirectional"))
    )
    (net (code "755") (name "ZZ.07.056") (class "Default")
      (node (ref "U$8") (pin "P$42") (pinfunction "B12_P$42") (pintype "bidirectional"))
    )
    (net (code "756") (name "ZZ.07.057") (class "Default")
      (node (ref "U$8") (pin "P$70") (pinfunction "C10_P$70") (pintype "bidirectional"))
    )
    (net (code "757") (name "ZZ.07.058") (class "Default")
      (node (ref "U$8") (pin "P$38") (pinfunction "B8_P$38") (pintype "bidirectional"))
    )
    (net (code "758") (name "ZZ.07.059") (class "Default")
      (node (ref "U$8") (pin "P$66") (pinfunction "C6_P$66") (pintype "bidirectional"))
    )
    (net (code "759") (name "ZZ.07.060") (class "Default")
      (node (ref "U$8") (pin "P$35") (pinfunction "B5_P$35") (pintype "bidirectional"))
    )
    (net (code "760") (name "ZZ.07.061") (class "Default")
      (node (ref "U$8") (pin "P$63") (pinfunction "C3_P$63") (pintype "bidirectional"))
    )
    (net (code "761") (name "ZZ.07.062") (class "Default")
      (node (ref "U$10") (pin "P$59") (pinfunction "B29_P$59") (pintype "bidirectional"))
    )
    (net (code "762") (name "ZZ.07.063") (class "Default")
      (node (ref "U$10") (pin "P$87") (pinfunction "C27_P$87") (pintype "bidirectional"))
    )
    (net (code "763") (name "ZZ.07.064") (class "Default")
      (node (ref "U$10") (pin "P$56") (pinfunction "B26_P$56") (pintype "bidirectional"))
    )
    (net (code "764") (name "ZZ.07.065") (class "Default")
      (node (ref "U$10") (pin "P$84") (pinfunction "C24_P$84") (pintype "bidirectional"))
    )
    (net (code "765") (name "ZZ.07.066") (class "Default")
      (node (ref "U$10") (pin "P$52") (pinfunction "B22_P$52") (pintype "bidirectional"))
    )
    (net (code "766") (name "ZZ.07.067") (class "Default")
      (node (ref "U$10") (pin "P$80") (pinfunction "C20_P$80") (pintype "bidirectional"))
    )
    (net (code "767") (name "ZZ.07.068") (class "Default")
      (node (ref "U$10") (pin "P$49") (pinfunction "B19_P$49") (pintype "bidirectional"))
    )
    (net (code "768") (name "ZZ.07.069") (class "Default")
      (node (ref "U$10") (pin "P$77") (pinfunction "C17_P$77") (pintype "bidirectional"))
    )
    (net (code "769") (name "ZZ.07.070") (class "Default")
      (node (ref "U$10") (pin "P$45") (pinfunction "B15_P$45") (pintype "bidirectional"))
    )
    (net (code "770") (name "ZZ.07.071") (class "Default")
      (node (ref "U$10") (pin "P$73") (pinfunction "C13_P$73") (pintype "bidirectional"))
    )
    (net (code "771") (name "ZZ.07.072") (class "Default")
      (node (ref "U$10") (pin "P$42") (pinfunction "B12_P$42") (pintype "bidirectional"))
    )
    (net (code "772") (name "ZZ.07.073") (class "Default")
      (node (ref "U$10") (pin "P$70") (pinfunction "C10_P$70") (pintype "bidirectional"))
    )
    (net (code "773") (name "ZZ.07.074") (class "Default")
      (node (ref "U$10") (pin "P$38") (pinfunction "B8_P$38") (pintype "bidirectional"))
    )
    (net (code "774") (name "ZZ.07.075") (class "Default")
      (node (ref "U$10") (pin "P$66") (pinfunction "C6_P$66") (pintype "bidirectional"))
    )
    (net (code "775") (name "ZZ.07.076") (class "Default")
      (node (ref "U$10") (pin "P$35") (pinfunction "B5_P$35") (pintype "bidirectional"))
    )
    (net (code "776") (name "ZZ.07.077") (class "Default")
      (node (ref "U$10") (pin "P$63") (pinfunction "C3_P$63") (pintype "bidirectional"))
    )
    (net (code "777") (name "ZZ.07.078") (class "Default")
      (node (ref "U$12") (pin "P$59") (pinfunction "B29_P$59") (pintype "bidirectional"))
    )
    (net (code "778") (name "ZZ.07.079") (class "Default")
      (node (ref "U$12") (pin "P$88") (pinfunction "C28_P$88") (pintype "bidirectional"))
    )
    (net (code "779") (name "ZZ.07.080") (class "Default")
      (node (ref "U$12") (pin "P$56") (pinfunction "B26_P$56") (pintype "bidirectional"))
    )
    (net (code "780") (name "ZZ.07.081") (class "Default")
      (node (ref "U$12") (pin "P$85") (pinfunction "C25_P$85") (pintype "bidirectional"))
    )
    (net (code "781") (name "ZZ.07.082") (class "Default")
      (node (ref "U$12") (pin "P$52") (pinfunction "B22_P$52") (pintype "bidirectional"))
    )
    (net (code "782") (name "ZZ.07.083") (class "Default")
      (node (ref "U$12") (pin "P$81") (pinfunction "C21_P$81") (pintype "bidirectional"))
    )
    (net (code "783") (name "ZZ.07.084") (class "Default")
      (node (ref "U$12") (pin "P$49") (pinfunction "B19_P$49") (pintype "bidirectional"))
    )
    (net (code "784") (name "ZZ.07.085") (class "Default")
      (node (ref "U$12") (pin "P$78") (pinfunction "C18_P$78") (pintype "bidirectional"))
    )
    (net (code "785") (name "ZZ.07.086") (class "Default")
      (node (ref "U$12") (pin "P$45") (pinfunction "B15_P$45") (pintype "bidirectional"))
    )
    (net (code "786") (name "ZZ.07.087") (class "Default")
      (node (ref "U$12") (pin "P$74") (pinfunction "C14_P$74") (pintype "bidirectional"))
    )
    (net (code "787") (name "ZZ.07.088") (class "Default")
      (node (ref "U$12") (pin "P$42") (pinfunction "B12_P$42") (pintype "bidirectional"))
    )
    (net (code "788") (name "ZZ.07.089") (class "Default")
      (node (ref "U$12") (pin "P$71") (pinfunction "C11_P$71") (pintype "bidirectional"))
    )
    (net (code "789") (name "ZZ.07.090") (class "Default")
      (node (ref "U$12") (pin "P$38") (pinfunction "B8_P$38") (pintype "bidirectional"))
    )
    (net (code "790") (name "ZZ.07.091") (class "Default")
      (node (ref "U$12") (pin "P$67") (pinfunction "C7_P$67") (pintype "bidirectional"))
    )
    (net (code "791") (name "ZZ.07.092") (class "Default")
      (node (ref "U$12") (pin "P$35") (pinfunction "B5_P$35") (pintype "bidirectional"))
    )
    (net (code "792") (name "ZZ.07.093") (class "Default")
      (node (ref "U$12") (pin "P$64") (pinfunction "C4_P$64") (pintype "bidirectional"))
    )
    (net (code "793") (name "ZZ.08.000") (class "Default")
      (node (ref "U$1") (pin "P$37") (pinfunction "B7_P$37") (pintype "bidirectional"))
    )
    (net (code "794") (name "ZZ.08.001") (class "Default")
      (node (ref "U$1") (pin "P$68") (pinfunction "C8_P$68") (pintype "bidirectional"))
    )
    (net (code "795") (name "ZZ.08.002") (class "Default")
      (node (ref "U$1") (pin "P$41") (pinfunction "B11_P$41") (pintype "bidirectional"))
    )
    (net (code "796") (name "ZZ.08.003") (class "Default")
      (node (ref "U$1") (pin "P$72") (pinfunction "C12_P$72") (pintype "bidirectional"))
    )
    (net (code "797") (name "ZZ.08.004") (class "Default")
      (node (ref "U$1") (pin "P$44") (pinfunction "B14_P$44") (pintype "bidirectional"))
    )
    (net (code "798") (name "ZZ.08.005") (class "Default")
      (node (ref "U$1") (pin "P$75") (pinfunction "C15_P$75") (pintype "bidirectional"))
    )
    (net (code "799") (name "ZZ.08.006") (class "Default")
      (node (ref "U$1") (pin "P$48") (pinfunction "B18_P$48") (pintype "bidirectional"))
    )
    (net (code "800") (name "ZZ.08.007") (class "Default")
      (node (ref "U$1") (pin "P$79") (pinfunction "C19_P$79") (pintype "bidirectional"))
    )
    (net (code "801") (name "ZZ.08.008") (class "Default")
      (node (ref "U$1") (pin "P$51") (pinfunction "B21_P$51") (pintype "bidirectional"))
    )
    (net (code "802") (name "ZZ.08.009") (class "Default")
      (node (ref "U$1") (pin "P$82") (pinfunction "C22_P$82") (pintype "bidirectional"))
    )
    (net (code "803") (name "ZZ.08.010") (class "Default")
      (node (ref "U$1") (pin "P$55") (pinfunction "B25_P$55") (pintype "bidirectional"))
    )
    (net (code "804") (name "ZZ.08.011") (class "Default")
      (node (ref "U$1") (pin "P$86") (pinfunction "C26_P$86") (pintype "bidirectional"))
    )
    (net (code "805") (name "ZZ.08.012") (class "Default")
      (node (ref "U$1") (pin "P$58") (pinfunction "B28_P$58") (pintype "bidirectional"))
    )
    (net (code "806") (name "ZZ.08.013") (class "Default")
      (node (ref "U$1") (pin "P$89") (pinfunction "C29_P$89") (pintype "bidirectional"))
    )
    (net (code "807") (name "ZZ.08.014") (class "Default")
      (node (ref "U$3") (pin "P$54") (pinfunction "B24_P$54") (pintype "bidirectional"))
    )
    (net (code "808") (name "ZZ.08.015") (class "Default")
      (node (ref "U$3") (pin "P$166") (pinfunction "F16_P$166") (pintype "bidirectional"))
    )
    (net (code "809") (name "ZZ.08.016") (class "Default")
      (node (ref "U$3") (pin "P$136") (pinfunction "E16_P$136") (pintype "bidirectional"))
    )
    (net (code "810") (name "ZZ.08.017") (class "Default")
      (node (ref "U$3") (pin "P$159") (pinfunction "F9_P$159") (pintype "bidirectional"))
    )
    (net (code "811") (name "ZZ.08.018") (class "Default")
      (node (ref "U$3") (pin "P$129") (pinfunction "E9_P$129") (pintype "bidirectional"))
    )
    (net (code "812") (name "ZZ.08.019") (class "Default")
      (node (ref "U$3") (pin "P$152") (pinfunction "F2_P$152") (pintype "bidirectional"))
    )
    (net (code "813") (name "ZZ.08.020") (class "Default")
      (node (ref "U$3") (pin "P$122") (pinfunction "E2_P$122") (pintype "bidirectional"))
    )
    (net (code "814") (name "ZZ.08.021") (class "Default")
      (node (ref "U$3") (pin "P$155") (pinfunction "F5_P$155") (pintype "bidirectional"))
    )
    (net (code "815") (name "ZZ.08.022") (class "Default")
      (node (ref "U$3") (pin "P$158") (pinfunction "F8_P$158") (pintype "bidirectional"))
    )
    (net (code "816") (name "ZZ.08.023") (class "Default")
      (node (ref "U$3") (pin "P$162") (pinfunction "F12_P$162") (pintype "bidirectional"))
    )
    (net (code "817") (name "ZZ.08.024") (class "Default")
      (node (ref "U$3") (pin "P$165") (pinfunction "F15_P$165") (pintype "bidirectional"))
    )
    (net (code "818") (name "ZZ.08.025") (class "Default")
      (node (ref "U$3") (pin "P$169") (pinfunction "F19_P$169") (pintype "bidirectional"))
    )
    (net (code "819") (name "ZZ.08.026") (class "Default")
      (node (ref "U$3") (pin "P$172") (pinfunction "F22_P$172") (pintype "bidirectional"))
    )
    (net (code "820") (name "ZZ.08.027") (class "Default")
      (node (ref "U$3") (pin "P$85") (pinfunction "C25_P$85") (pintype "bidirectional"))
    )
    (net (code "821") (name "ZZ.08.028") (class "Default")
      (node (ref "U$3") (pin "P$144") (pinfunction "E24_P$144") (pintype "bidirectional"))
    )
    (net (code "822") (name "ZZ.08.029") (class "Default")
      (node (ref "U$3") (pin "P$143") (pinfunction "E23_P$143") (pintype "bidirectional"))
    )
    (net (code "823") (name "ZZ.08.030") (class "Default")
      (node (ref "U$5") (pin "P$166") (pinfunction "F16_P$166") (pintype "bidirectional"))
    )
    (net (code "824") (name "ZZ.08.031") (class "Default")
      (node (ref "U$5") (pin "P$136") (pinfunction "E16_P$136") (pintype "bidirectional"))
    )
    (net (code "825") (name "ZZ.08.032") (class "Default")
      (node (ref "U$5") (pin "P$159") (pinfunction "F9_P$159") (pintype "bidirectional"))
    )
    (net (code "826") (name "ZZ.08.033") (class "Default")
      (node (ref "U$5") (pin "P$165") (pinfunction "F15_P$165") (pintype "bidirectional"))
    )
    (net (code "827") (name "ZZ.08.034") (class "Default")
      (node (ref "U$5") (pin "P$169") (pinfunction "F19_P$169") (pintype "bidirectional"))
    )
    (net (code "828") (name "ZZ.08.035") (class "Default")
      (node (ref "U$5") (pin "P$172") (pinfunction "F22_P$172") (pintype "bidirectional"))
    )
    (net (code "829") (name "ZZ.08.036") (class "Default")
      (node (ref "U$5") (pin "P$176") (pinfunction "F26_P$176") (pintype "bidirectional"))
    )
    (net (code "830") (name "ZZ.08.037") (class "Default")
      (node (ref "U$5") (pin "P$179") (pinfunction "F29_P$179") (pintype "bidirectional"))
    )
    (net (code "831") (name "ZZ.08.038") (class "Default")
      (node (ref "U$5") (pin "P$173") (pinfunction "F23_P$173") (pintype "bidirectional"))
    )
    (net (code "832") (name "ZZ.08.039") (class "Default")
      (node (ref "U$5") (pin "P$143") (pinfunction "E23_P$143") (pintype "bidirectional"))
    )
    (net (code "833") (name "ZZ.08.040") (class "Default")
      (node (ref "U$5") (pin "P$154") (pinfunction "F4_P$154") (pintype "bidirectional"))
    )
    (net (code "834") (name "ZZ.08.041") (class "Default")
      (node (ref "U$5") (pin "P$157") (pinfunction "F7_P$157") (pintype "bidirectional"))
    )
    (net (code "835") (name "ZZ.08.042") (class "Default")
      (node (ref "U$5") (pin "P$161") (pinfunction "F11_P$161") (pintype "bidirectional"))
    )
    (net (code "836") (name "ZZ.08.043") (class "Default")
      (node (ref "U$5") (pin "P$129") (pinfunction "E9_P$129") (pintype "bidirectional"))
    )
    (net (code "837") (name "ZZ.08.044") (class "Default")
      (node (ref "U$5") (pin "P$152") (pinfunction "F2_P$152") (pintype "bidirectional"))
    )
    (net (code "838") (name "ZZ.08.045") (class "Default")
      (node (ref "U$5") (pin "P$122") (pinfunction "E2_P$122") (pintype "bidirectional"))
    )
    (net (code "839") (name "ZZ.08.046") (class "Default")
      (node (ref "U$7") (pin "P$161") (pinfunction "F11_P$161") (pintype "bidirectional"))
    )
    (net (code "840") (name "ZZ.08.047") (class "Default")
      (node (ref "U$7") (pin "P$164") (pinfunction "F14_P$164") (pintype "bidirectional"))
    )
    (net (code "841") (name "ZZ.08.048") (class "Default")
      (node (ref "U$7") (pin "P$144") (pinfunction "E24_P$144") (pintype "bidirectional"))
    )
    (net (code "842") (name "ZZ.08.049") (class "Default")
      (node (ref "U$7") (pin "P$85") (pinfunction "C25_P$85") (pintype "bidirectional"))
    )
    (net (code "843") (name "ZZ.08.050") (class "Default")
      (node (ref "U$7") (pin "P$84") (pinfunction "C24_P$84") (pintype "bidirectional"))
    )
    (net (code "844") (name "ZZ.08.051") (class "Default")
      (node (ref "U$7") (pin "P$143") (pinfunction "E23_P$143") (pintype "bidirectional"))
    )
    (net (code "845") (name "ZZ.08.052") (class "Default")
      (node (ref "U$7") (pin "P$168") (pinfunction "F18_P$168") (pintype "bidirectional"))
    )
    (net (code "846") (name "ZZ.08.053") (class "Default")
      (node (ref "U$7") (pin "P$171") (pinfunction "F21_P$171") (pintype "bidirectional"))
    )
    (net (code "847") (name "ZZ.08.054") (class "Default")
      (node (ref "U$7") (pin "P$166") (pinfunction "F16_P$166") (pintype "bidirectional"))
    )
    (net (code "848") (name "ZZ.08.055") (class "Default")
      (node (ref "U$7") (pin "P$136") (pinfunction "E16_P$136") (pintype "bidirectional"))
    )
    (net (code "849") (name "ZZ.08.056") (class "Default")
      (node (ref "U$7") (pin "P$159") (pinfunction "F9_P$159") (pintype "bidirectional"))
    )
    (net (code "850") (name "ZZ.08.057") (class "Default")
      (node (ref "U$7") (pin "P$129") (pinfunction "E9_P$129") (pintype "bidirectional"))
    )
    (net (code "851") (name "ZZ.08.058") (class "Default")
      (node (ref "U$7") (pin "P$152") (pinfunction "F2_P$152") (pintype "bidirectional"))
    )
    (net (code "852") (name "ZZ.08.059") (class "Default")
      (node (ref "U$7") (pin "P$122") (pinfunction "E2_P$122") (pintype "bidirectional"))
    )
    (net (code "853") (name "ZZ.08.060") (class "Default")
      (node (ref "U$7") (pin "P$157") (pinfunction "F7_P$157") (pintype "bidirectional"))
    )
    (net (code "854") (name "ZZ.08.061") (class "Default")
      (node (ref "U$7") (pin "P$154") (pinfunction "F4_P$154") (pintype "bidirectional"))
    )
    (net (code "855") (name "ZZ.08.062") (class "Default")
      (node (ref "U$9") (pin "P$143") (pinfunction "E23_P$143") (pintype "bidirectional"))
    )
    (net (code "856") (name "ZZ.08.063") (class "Default")
      (node (ref "U$9") (pin "P$144") (pinfunction "E24_P$144") (pintype "bidirectional"))
    )
    (net (code "857") (name "ZZ.08.064") (class "Default")
      (node (ref "U$9") (pin "P$84") (pinfunction "C24_P$84") (pintype "bidirectional"))
    )
    (net (code "858") (name "ZZ.08.065") (class "Default")
      (node (ref "U$9") (pin "P$166") (pinfunction "F16_P$166") (pintype "bidirectional"))
    )
    (net (code "859") (name "ZZ.08.066") (class "Default")
      (node (ref "U$9") (pin "P$136") (pinfunction "E16_P$136") (pintype "bidirectional"))
    )
    (net (code "860") (name "ZZ.08.067") (class "Default")
      (node (ref "U$9") (pin "P$159") (pinfunction "F9_P$159") (pintype "bidirectional"))
    )
    (net (code "861") (name "ZZ.08.068") (class "Default")
      (node (ref "U$9") (pin "P$129") (pinfunction "E9_P$129") (pintype "bidirectional"))
    )
    (net (code "862") (name "ZZ.08.069") (class "Default")
      (node (ref "U$9") (pin "P$152") (pinfunction "F2_P$152") (pintype "bidirectional"))
    )
    (net (code "863") (name "ZZ.08.070") (class "Default")
      (node (ref "U$9") (pin "P$122") (pinfunction "E2_P$122") (pintype "bidirectional"))
    )
    (net (code "864") (name "ZZ.08.071") (class "Default")
      (node (ref "U$9") (pin "P$154") (pinfunction "F4_P$154") (pintype "bidirectional"))
    )
    (net (code "865") (name "ZZ.08.072") (class "Default")
      (node (ref "U$9") (pin "P$157") (pinfunction "F7_P$157") (pintype "bidirectional"))
    )
    (net (code "866") (name "ZZ.08.073") (class "Default")
      (node (ref "U$9") (pin "P$161") (pinfunction "F11_P$161") (pintype "bidirectional"))
    )
    (net (code "867") (name "ZZ.08.074") (class "Default")
      (node (ref "U$9") (pin "P$164") (pinfunction "F14_P$164") (pintype "bidirectional"))
    )
    (net (code "868") (name "ZZ.08.075") (class "Default")
      (node (ref "U$9") (pin "P$168") (pinfunction "F18_P$168") (pintype "bidirectional"))
    )
    (net (code "869") (name "ZZ.08.076") (class "Default")
      (node (ref "U$9") (pin "P$171") (pinfunction "F21_P$171") (pintype "bidirectional"))
    )
    (net (code "870") (name "ZZ.08.077") (class "Default")
      (node (ref "U$9") (pin "P$85") (pinfunction "C25_P$85") (pintype "bidirectional"))
    )
    (net (code "871") (name "ZZ.08.078") (class "Default")
      (node (ref "U$11") (pin "P$148") (pinfunction "E28_P$148") (pintype "bidirectional"))
    )
    (net (code "872") (name "ZZ.08.079") (class "Default")
      (node (ref "U$11") (pin "P$173") (pinfunction "F23_P$173") (pintype "bidirectional"))
    )
    (net (code "873") (name "ZZ.08.080") (class "Default")
      (node (ref "U$11") (pin "P$145") (pinfunction "E25_P$145") (pintype "bidirectional"))
    )
    (net (code "874") (name "ZZ.08.081") (class "Default")
      (node (ref "U$11") (pin "P$143") (pinfunction "E23_P$143") (pintype "bidirectional"))
    )
    (net (code "875") (name "ZZ.08.082") (class "Default")
      (node (ref "U$11") (pin "P$141") (pinfunction "E21_P$141") (pintype "bidirectional"))
    )
    (net (code "876") (name "ZZ.08.083") (class "Default")
      (node (ref "U$11") (pin "P$166") (pinfunction "F16_P$166") (pintype "bidirectional"))
    )
    (net (code "877") (name "ZZ.08.084") (class "Default")
      (node (ref "U$11") (pin "P$138") (pinfunction "E18_P$138") (pintype "bidirectional"))
    )
    (net (code "878") (name "ZZ.08.085") (class "Default")
      (node (ref "U$11") (pin "P$136") (pinfunction "E16_P$136") (pintype "bidirectional"))
    )
    (net (code "879") (name "ZZ.08.086") (class "Default")
      (node (ref "U$11") (pin "P$134") (pinfunction "E14_P$134") (pintype "bidirectional"))
    )
    (net (code "880") (name "ZZ.08.087") (class "Default")
      (node (ref "U$11") (pin "P$159") (pinfunction "F9_P$159") (pintype "bidirectional"))
    )
    (net (code "881") (name "ZZ.08.088") (class "Default")
      (node (ref "U$11") (pin "P$131") (pinfunction "E11_P$131") (pintype "bidirectional"))
    )
    (net (code "882") (name "ZZ.08.089") (class "Default")
      (node (ref "U$11") (pin "P$129") (pinfunction "E9_P$129") (pintype "bidirectional"))
    )
    (net (code "883") (name "ZZ.08.090") (class "Default")
      (node (ref "U$11") (pin "P$127") (pinfunction "E7_P$127") (pintype "bidirectional"))
    )
    (net (code "884") (name "ZZ.08.091") (class "Default")
      (node (ref "U$11") (pin "P$152") (pinfunction "F2_P$152") (pintype "bidirectional"))
    )
    (net (code "885") (name "ZZ.08.092") (class "Default")
      (node (ref "U$11") (pin "P$124") (pinfunction "E4_P$124") (pintype "bidirectional"))
    )
    (net (code "886") (name "ZZ.08.093") (class "Default")
      (node (ref "U$11") (pin "P$122") (pinfunction "E2_P$122") (pintype "bidirectional"))
    )
    (net (code "887") (name "ZZ.09.000") (class "Default")
      (node (ref "U$1") (pin "P$66") (pinfunction "C6_P$66") (pintype "bidirectional"))
    )
    (net (code "888") (name "ZZ.09.001") (class "Default")
      (node (ref "U$1") (pin "P$38") (pinfunction "B8_P$38") (pintype "bidirectional"))
    )
    (net (code "889") (name "ZZ.09.002") (class "Default")
      (node (ref "U$1") (pin "P$70") (pinfunction "C10_P$70") (pintype "bidirectional"))
    )
    (net (code "890") (name "ZZ.09.003") (class "Default")
      (node (ref "U$1") (pin "P$42") (pinfunction "B12_P$42") (pintype "bidirectional"))
    )
    (net (code "891") (name "ZZ.09.004") (class "Default")
      (node (ref "U$1") (pin "P$73") (pinfunction "C13_P$73") (pintype "bidirectional"))
    )
    (net (code "892") (name "ZZ.09.005") (class "Default")
      (node (ref "U$1") (pin "P$45") (pinfunction "B15_P$45") (pintype "bidirectional"))
    )
    (net (code "893") (name "ZZ.09.006") (class "Default")
      (node (ref "U$1") (pin "P$77") (pinfunction "C17_P$77") (pintype "bidirectional"))
    )
    (net (code "894") (name "ZZ.09.007") (class "Default")
      (node (ref "U$1") (pin "P$49") (pinfunction "B19_P$49") (pintype "bidirectional"))
    )
    (net (code "895") (name "ZZ.09.008") (class "Default")
      (node (ref "U$1") (pin "P$80") (pinfunction "C20_P$80") (pintype "bidirectional"))
    )
    (net (code "896") (name "ZZ.09.009") (class "Default")
      (node (ref "U$1") (pin "P$52") (pinfunction "B22_P$52") (pintype "bidirectional"))
    )
    (net (code "897") (name "ZZ.09.010") (class "Default")
      (node (ref "U$1") (pin "P$84") (pinfunction "C24_P$84") (pintype "bidirectional"))
    )
    (net (code "898") (name "ZZ.09.011") (class "Default")
      (node (ref "U$1") (pin "P$56") (pinfunction "B26_P$56") (pintype "bidirectional"))
    )
    (net (code "899") (name "ZZ.09.012") (class "Default")
      (node (ref "U$1") (pin "P$87") (pinfunction "C27_P$87") (pintype "bidirectional"))
    )
    (net (code "900") (name "ZZ.09.013") (class "Default")
      (node (ref "U$1") (pin "P$59") (pinfunction "B29_P$59") (pintype "bidirectional"))
    )
    (net (code "901") (name "ZZ.09.014") (class "Default")
      (node (ref "U$3") (pin "P$55") (pinfunction "B25_P$55") (pintype "bidirectional"))
    )
    (net (code "902") (name "ZZ.09.015") (class "Default")
      (node (ref "U$3") (pin "P$170") (pinfunction "F20_P$170") (pintype "bidirectional"))
    )
    (net (code "903") (name "ZZ.09.016") (class "Default")
      (node (ref "U$3") (pin "P$167") (pinfunction "F17_P$167") (pintype "bidirectional"))
    )
    (net (code "904") (name "ZZ.09.017") (class "Default")
      (node (ref "U$3") (pin "P$163") (pinfunction "F13_P$163") (pintype "bidirectional"))
    )
    (net (code "905") (name "ZZ.09.018") (class "Default")
      (node (ref "U$3") (pin "P$160") (pinfunction "F10_P$160") (pintype "bidirectional"))
    )
    (net (code "906") (name "ZZ.09.019") (class "Default")
      (node (ref "U$3") (pin "P$156") (pinfunction "F6_P$156") (pintype "bidirectional"))
    )
    (net (code "907") (name "ZZ.09.020") (class "Default")
      (node (ref "U$3") (pin "P$153") (pinfunction "F3_P$153") (pintype "bidirectional"))
    )
    (net (code "908") (name "ZZ.09.021") (class "Default")
      (node (ref "U$3") (pin "P$154") (pinfunction "F4_P$154") (pintype "bidirectional"))
    )
    (net (code "909") (name "ZZ.09.022") (class "Default")
      (node (ref "U$3") (pin "P$157") (pinfunction "F7_P$157") (pintype "bidirectional"))
    )
    (net (code "910") (name "ZZ.09.023") (class "Default")
      (node (ref "U$3") (pin "P$161") (pinfunction "F11_P$161") (pintype "bidirectional"))
    )
    (net (code "911") (name "ZZ.09.024") (class "Default")
      (node (ref "U$3") (pin "P$164") (pinfunction "F14_P$164") (pintype "bidirectional"))
    )
    (net (code "912") (name "ZZ.09.025") (class "Default")
      (node (ref "U$3") (pin "P$168") (pinfunction "F18_P$168") (pintype "bidirectional"))
    )
    (net (code "913") (name "ZZ.09.026") (class "Default")
      (node (ref "U$3") (pin "P$171") (pinfunction "F21_P$171") (pintype "bidirectional"))
    )
    (net (code "914") (name "ZZ.09.027") (class "Default")
      (node (ref "U$3") (pin "P$84") (pinfunction "C24_P$84") (pintype "bidirectional"))
    )
    (net (code "915") (name "ZZ.09.028") (class "Default")
      (node (ref "U$3") (pin "P$114") (pinfunction "D24_P$114") (pintype "bidirectional"))
    )
    (net (code "916") (name "ZZ.09.029") (class "Default")
      (node (ref "U$3") (pin "P$174") (pinfunction "F24_P$174") (pintype "bidirectional"))
    )
    (net (code "917") (name "ZZ.09.030") (class "Default")
      (node (ref "U$5") (pin "P$170") (pinfunction "F20_P$170") (pintype "bidirectional"))
    )
    (net (code "918") (name "ZZ.09.031") (class "Default")
      (node (ref "U$5") (pin "P$167") (pinfunction "F17_P$167") (pintype "bidirectional"))
    )
    (net (code "919") (name "ZZ.09.032") (class "Default")
      (node (ref "U$5") (pin "P$163") (pinfunction "F13_P$163") (pintype "bidirectional"))
    )
    (net (code "920") (name "ZZ.09.033") (class "Default")
      (node (ref "U$5") (pin "P$164") (pinfunction "F14_P$164") (pintype "bidirectional"))
    )
    (net (code "921") (name "ZZ.09.034") (class "Default")
      (node (ref "U$5") (pin "P$168") (pinfunction "F18_P$168") (pintype "bidirectional"))
    )
    (net (code "922") (name "ZZ.09.035") (class "Default")
      (node (ref "U$5") (pin "P$171") (pinfunction "F21_P$171") (pintype "bidirectional"))
    )
    (net (code "923") (name "ZZ.09.036") (class "Default")
      (node (ref "U$5") (pin "P$175") (pinfunction "F25_P$175") (pintype "bidirectional"))
    )
    (net (code "924") (name "ZZ.09.037") (class "Default")
      (node (ref "U$5") (pin "P$178") (pinfunction "F28_P$178") (pintype "bidirectional"))
    )
    (net (code "925") (name "ZZ.09.038") (class "Default")
      (node (ref "U$5") (pin "P$177") (pinfunction "F27_P$177") (pintype "bidirectional"))
    )
    (net (code "926") (name "ZZ.09.039") (class "Default")
      (node (ref "U$5") (pin "P$174") (pinfunction "F24_P$174") (pintype "bidirectional"))
    )
    (net (code "927") (name "ZZ.09.040") (class "Default")
      (node (ref "U$5") (pin "P$155") (pinfunction "F5_P$155") (pintype "bidirectional"))
    )
    (net (code "928") (name "ZZ.09.041") (class "Default")
      (node (ref "U$5") (pin "P$158") (pinfunction "F8_P$158") (pintype "bidirectional"))
    )
    (net (code "929") (name "ZZ.09.042") (class "Default")
      (node (ref "U$5") (pin "P$162") (pinfunction "F12_P$162") (pintype "bidirectional"))
    )
    (net (code "930") (name "ZZ.09.043") (class "Default")
      (node (ref "U$5") (pin "P$160") (pinfunction "F10_P$160") (pintype "bidirectional"))
    )
    (net (code "931") (name "ZZ.09.044") (class "Default")
      (node (ref "U$5") (pin "P$156") (pinfunction "F6_P$156") (pintype "bidirectional"))
    )
    (net (code "932") (name "ZZ.09.045") (class "Default")
      (node (ref "U$5") (pin "P$153") (pinfunction "F3_P$153") (pintype "bidirectional"))
    )
    (net (code "933") (name "ZZ.09.046") (class "Default")
      (node (ref "U$7") (pin "P$162") (pinfunction "F12_P$162") (pintype "bidirectional"))
    )
    (net (code "934") (name "ZZ.09.047") (class "Default")
      (node (ref "U$7") (pin "P$165") (pinfunction "F15_P$165") (pintype "bidirectional"))
    )
    (net (code "935") (name "ZZ.09.048") (class "Default")
      (node (ref "U$7") (pin "P$114") (pinfunction "D24_P$114") (pintype "bidirectional"))
    )
    (net (code "936") (name "ZZ.09.049") (class "Default")
      (node (ref "U$7") (pin "P$55") (pinfunction "B25_P$55") (pintype "bidirectional"))
    )
    (net (code "937") (name "ZZ.09.050") (class "Default")
      (node (ref "U$7") (pin "P$54") (pinfunction "B24_P$54") (pintype "bidirectional"))
    )
    (net (code "938") (name "ZZ.09.051") (class "Default")
      (node (ref "U$7") (pin "P$174") (pinfunction "F24_P$174") (pintype "bidirectional"))
    )
    (net (code "939") (name "ZZ.09.052") (class "Default")
      (node (ref "U$7") (pin "P$169") (pinfunction "F19_P$169") (pintype "bidirectional"))
    )
    (net (code "940") (name "ZZ.09.053") (class "Default")
      (node (ref "U$7") (pin "P$172") (pinfunction "F22_P$172") (pintype "bidirectional"))
    )
    (net (code "941") (name "ZZ.09.054") (class "Default")
      (node (ref "U$7") (pin "P$170") (pinfunction "F20_P$170") (pintype "bidirectional"))
    )
    (net (code "942") (name "ZZ.09.055") (class "Default")
      (node (ref "U$7") (pin "P$167") (pinfunction "F17_P$167") (pintype "bidirectional"))
    )
    (net (code "943") (name "ZZ.09.056") (class "Default")
      (node (ref "U$7") (pin "P$163") (pinfunction "F13_P$163") (pintype "bidirectional"))
    )
    (net (code "944") (name "ZZ.09.057") (class "Default")
      (node (ref "U$7") (pin "P$160") (pinfunction "F10_P$160") (pintype "bidirectional"))
    )
    (net (code "945") (name "ZZ.09.058") (class "Default")
      (node (ref "U$7") (pin "P$156") (pinfunction "F6_P$156") (pintype "bidirectional"))
    )
    (net (code "946") (name "ZZ.09.059") (class "Default")
      (node (ref "U$7") (pin "P$153") (pinfunction "F3_P$153") (pintype "bidirectional"))
    )
    (net (code "947") (name "ZZ.09.060") (class "Default")
      (node (ref "U$7") (pin "P$158") (pinfunction "F8_P$158") (pintype "bidirectional"))
    )
    (net (code "948") (name "ZZ.09.061") (class "Default")
      (node (ref "U$7") (pin "P$155") (pinfunction "F5_P$155") (pintype "bidirectional"))
    )
    (net (code "949") (name "ZZ.09.062") (class "Default")
      (node (ref "U$9") (pin "P$174") (pinfunction "F24_P$174") (pintype "bidirectional"))
    )
    (net (code "950") (name "ZZ.09.063") (class "Default")
      (node (ref "U$9") (pin "P$114") (pinfunction "D24_P$114") (pintype "bidirectional"))
    )
    (net (code "951") (name "ZZ.09.064") (class "Default")
      (node (ref "U$9") (pin "P$54") (pinfunction "B24_P$54") (pintype "bidirectional"))
    )
    (net (code "952") (name "ZZ.09.065") (class "Default")
      (node (ref "U$9") (pin "P$170") (pinfunction "F20_P$170") (pintype "bidirectional"))
    )
    (net (code "953") (name "ZZ.09.066") (class "Default")
      (node (ref "U$9") (pin "P$167") (pinfunction "F17_P$167") (pintype "bidirectional"))
    )
    (net (code "954") (name "ZZ.09.067") (class "Default")
      (node (ref "U$9") (pin "P$163") (pinfunction "F13_P$163") (pintype "bidirectional"))
    )
    (net (code "955") (name "ZZ.09.068") (class "Default")
      (node (ref "U$9") (pin "P$160") (pinfunction "F10_P$160") (pintype "bidirectional"))
    )
    (net (code "956") (name "ZZ.09.069") (class "Default")
      (node (ref "U$9") (pin "P$156") (pinfunction "F6_P$156") (pintype "bidirectional"))
    )
    (net (code "957") (name "ZZ.09.070") (class "Default")
      (node (ref "U$9") (pin "P$153") (pinfunction "F3_P$153") (pintype "bidirectional"))
    )
    (net (code "958") (name "ZZ.09.071") (class "Default")
      (node (ref "U$9") (pin "P$155") (pinfunction "F5_P$155") (pintype "bidirectional"))
    )
    (net (code "959") (name "ZZ.09.072") (class "Default")
      (node (ref "U$9") (pin "P$158") (pinfunction "F8_P$158") (pintype "bidirectional"))
    )
    (net (code "960") (name "ZZ.09.073") (class "Default")
      (node (ref "U$9") (pin "P$162") (pinfunction "F12_P$162") (pintype "bidirectional"))
    )
    (net (code "961") (name "ZZ.09.074") (class "Default")
      (node (ref "U$9") (pin "P$165") (pinfunction "F15_P$165") (pintype "bidirectional"))
    )
    (net (code "962") (name "ZZ.09.075") (class "Default")
      (node (ref "U$9") (pin "P$169") (pinfunction "F19_P$169") (pintype "bidirectional"))
    )
    (net (code "963") (name "ZZ.09.076") (class "Default")
      (node (ref "U$9") (pin "P$172") (pinfunction "F22_P$172") (pintype "bidirectional"))
    )
    (net (code "964") (name "ZZ.09.077") (class "Default")
      (node (ref "U$9") (pin "P$55") (pinfunction "B25_P$55") (pintype "bidirectional"))
    )
    (net (code "965") (name "ZZ.09.078") (class "Default")
      (node (ref "U$11") (pin "P$179") (pinfunction "F29_P$179") (pintype "bidirectional"))
    )
    (net (code "966") (name "ZZ.09.079") (class "Default")
      (node (ref "U$11") (pin "P$177") (pinfunction "F27_P$177") (pintype "bidirectional"))
    )
    (net (code "967") (name "ZZ.09.080") (class "Default")
      (node (ref "U$11") (pin "P$176") (pinfunction "F26_P$176") (pintype "bidirectional"))
    )
    (net (code "968") (name "ZZ.09.081") (class "Default")
      (node (ref "U$11") (pin "P$174") (pinfunction "F24_P$174") (pintype "bidirectional"))
    )
    (net (code "969") (name "ZZ.09.082") (class "Default")
      (node (ref "U$11") (pin "P$172") (pinfunction "F22_P$172") (pintype "bidirectional"))
    )
    (net (code "970") (name "ZZ.09.083") (class "Default")
      (node (ref "U$11") (pin "P$170") (pinfunction "F20_P$170") (pintype "bidirectional"))
    )
    (net (code "971") (name "ZZ.09.084") (class "Default")
      (node (ref "U$11") (pin "P$169") (pinfunction "F19_P$169") (pintype "bidirectional"))
    )
    (net (code "972") (name "ZZ.09.085") (class "Default")
      (node (ref "U$11") (pin "P$167") (pinfunction "F17_P$167") (pintype "bidirectional"))
    )
    (net (code "973") (name "ZZ.09.086") (class "Default")
      (node (ref "U$11") (pin "P$165") (pinfunction "F15_P$165") (pintype "bidirectional"))
    )
    (net (code "974") (name "ZZ.09.087") (class "Default")
      (node (ref "U$11") (pin "P$163") (pinfunction "F13_P$163") (pintype "bidirectional"))
    )
    (net (code "975") (name "ZZ.09.088") (class "Default")
      (node (ref "U$11") (pin "P$162") (pinfunction "F12_P$162") (pintype "bidirectional"))
    )
    (net (code "976") (name "ZZ.09.089") (class "Default")
      (node (ref "U$11") (pin "P$160") (pinfunction "F10_P$160") (pintype "bidirectional"))
    )
    (net (code "977") (name "ZZ.09.090") (class "Default")
      (node (ref "U$11") (pin "P$158") (pinfunction "F8_P$158") (pintype "bidirectional"))
    )
    (net (code "978") (name "ZZ.09.091") (class "Default")
      (node (ref "U$11") (pin "P$156") (pinfunction "F6_P$156") (pintype "bidirectional"))
    )
    (net (code "979") (name "ZZ.09.092") (class "Default")
      (node (ref "U$11") (pin "P$155") (pinfunction "F5_P$155") (pintype "bidirectional"))
    )
    (net (code "980") (name "ZZ.09.093") (class "Default")
      (node (ref "U$11") (pin "P$153") (pinfunction "F3_P$153") (pintype "bidirectional"))
    )
    (net (code "981") (name "ZZ.10.000") (class "Default")
      (node (ref "U$1") (pin "P$36") (pinfunction "B6_P$36") (pintype "bidirectional"))
    )
    (net (code "982") (name "ZZ.10.001") (class "Default")
      (node (ref "U$1") (pin "P$67") (pinfunction "C7_P$67") (pintype "bidirectional"))
    )
    (net (code "983") (name "ZZ.10.002") (class "Default")
      (node (ref "U$1") (pin "P$40") (pinfunction "B10_P$40") (pintype "bidirectional"))
    )
    (net (code "984") (name "ZZ.10.003") (class "Default")
      (node (ref "U$1") (pin "P$71") (pinfunction "C11_P$71") (pintype "bidirectional"))
    )
    (net (code "985") (name "ZZ.10.004") (class "Default")
      (node (ref "U$1") (pin "P$43") (pinfunction "B13_P$43") (pintype "bidirectional"))
    )
    (net (code "986") (name "ZZ.10.005") (class "Default")
      (node (ref "U$1") (pin "P$74") (pinfunction "C14_P$74") (pintype "bidirectional"))
    )
    (net (code "987") (name "ZZ.10.006") (class "Default")
      (node (ref "U$1") (pin "P$47") (pinfunction "B17_P$47") (pintype "bidirectional"))
    )
    (net (code "988") (name "ZZ.10.007") (class "Default")
      (node (ref "U$1") (pin "P$78") (pinfunction "C18_P$78") (pintype "bidirectional"))
    )
    (net (code "989") (name "ZZ.10.008") (class "Default")
      (node (ref "U$1") (pin "P$50") (pinfunction "B20_P$50") (pintype "bidirectional"))
    )
    (net (code "990") (name "ZZ.10.009") (class "Default")
      (node (ref "U$1") (pin "P$81") (pinfunction "C21_P$81") (pintype "bidirectional"))
    )
    (net (code "991") (name "ZZ.10.010") (class "Default")
      (node (ref "U$1") (pin "P$54") (pinfunction "B24_P$54") (pintype "bidirectional"))
    )
    (net (code "992") (name "ZZ.10.011") (class "Default")
      (node (ref "U$1") (pin "P$85") (pinfunction "C25_P$85") (pintype "bidirectional"))
    )
    (net (code "993") (name "ZZ.10.012") (class "Default")
      (node (ref "U$1") (pin "P$57") (pinfunction "B27_P$57") (pintype "bidirectional"))
    )
    (net (code "994") (name "ZZ.10.013") (class "Default")
      (node (ref "U$1") (pin "P$88") (pinfunction "C28_P$88") (pintype "bidirectional"))
    )
    (net (code "995") (name "ZZ.10.014") (class "Default")
      (node (ref "U$3") (pin "P$65") (pinfunction "C5_P$65") (pintype "bidirectional"))
    )
    (net (code "996") (name "ZZ.10.015") (class "Default")
      (node (ref "U$3") (pin "P$125") (pinfunction "E5_P$125") (pintype "bidirectional"))
    )
    (net (code "997") (name "ZZ.10.016") (class "Default")
      (node (ref "U$3") (pin "P$68") (pinfunction "C8_P$68") (pintype "bidirectional"))
    )
    (net (code "998") (name "ZZ.10.017") (class "Default")
      (node (ref "U$3") (pin "P$128") (pinfunction "E8_P$128") (pintype "bidirectional"))
    )
    (net (code "999") (name "ZZ.10.018") (class "Default")
      (node (ref "U$3") (pin "P$72") (pinfunction "C12_P$72") (pintype "bidirectional"))
    )
    (net (code "1000") (name "ZZ.10.019") (class "Default")
      (node (ref "U$3") (pin "P$132") (pinfunction "E12_P$132") (pintype "bidirectional"))
    )
    (net (code "1001") (name "ZZ.10.020") (class "Default")
      (node (ref "U$3") (pin "P$75") (pinfunction "C15_P$75") (pintype "bidirectional"))
    )
    (net (code "1002") (name "ZZ.10.021") (class "Default")
      (node (ref "U$3") (pin "P$135") (pinfunction "E15_P$135") (pintype "bidirectional"))
    )
    (net (code "1003") (name "ZZ.10.022") (class "Default")
      (node (ref "U$3") (pin "P$79") (pinfunction "C19_P$79") (pintype "bidirectional"))
    )
    (net (code "1004") (name "ZZ.10.023") (class "Default")
      (node (ref "U$3") (pin "P$139") (pinfunction "E19_P$139") (pintype "bidirectional"))
    )
    (net (code "1005") (name "ZZ.10.024") (class "Default")
      (node (ref "U$3") (pin "P$82") (pinfunction "C22_P$82") (pintype "bidirectional"))
    )
    (net (code "1006") (name "ZZ.10.025") (class "Default")
      (node (ref "U$3") (pin "P$142") (pinfunction "E22_P$142") (pintype "bidirectional"))
    )
    (net (code "1007") (name "ZZ.10.026") (class "Default")
      (node (ref "U$3") (pin "P$118") (pinfunction "D28_P$118") (pintype "bidirectional"))
    )
    (net (code "1008") (name "ZZ.10.027") (class "Default")
      (node (ref "U$3") (pin "P$116") (pinfunction "D26_P$116") (pintype "bidirectional"))
    )
    (net (code "1009") (name "ZZ.10.028") (class "Default")
      (node (ref "U$3") (pin "P$148") (pinfunction "E28_P$148") (pintype "bidirectional"))
    )
    (net (code "1010") (name "ZZ.10.029") (class "Default")
      (node (ref "U$3") (pin "P$175") (pinfunction "F25_P$175") (pintype "bidirectional"))
    )
    (net (code "1011") (name "ZZ.10.030") (class "Default")
      (node (ref "U$5") (pin "P$75") (pinfunction "C15_P$75") (pintype "bidirectional"))
    )
    (net (code "1012") (name "ZZ.10.031") (class "Default")
      (node (ref "U$5") (pin "P$135") (pinfunction "E15_P$135") (pintype "bidirectional"))
    )
    (net (code "1013") (name "ZZ.10.032") (class "Default")
      (node (ref "U$5") (pin "P$79") (pinfunction "C19_P$79") (pintype "bidirectional"))
    )
    (net (code "1014") (name "ZZ.10.033") (class "Default")
      (node (ref "U$5") (pin "P$139") (pinfunction "E19_P$139") (pintype "bidirectional"))
    )
    (net (code "1015") (name "ZZ.10.034") (class "Default")
      (node (ref "U$5") (pin "P$82") (pinfunction "C22_P$82") (pintype "bidirectional"))
    )
    (net (code "1016") (name "ZZ.10.035") (class "Default")
      (node (ref "U$5") (pin "P$142") (pinfunction "E22_P$142") (pintype "bidirectional"))
    )
    (net (code "1017") (name "ZZ.10.036") (class "Default")
      (node (ref "U$5") (pin "P$86") (pinfunction "C26_P$86") (pintype "bidirectional"))
    )
    (net (code "1018") (name "ZZ.10.037") (class "Default")
      (node (ref "U$5") (pin "P$146") (pinfunction "E26_P$146") (pintype "bidirectional"))
    )
    (net (code "1019") (name "ZZ.10.038") (class "Default")
      (node (ref "U$5") (pin "P$89") (pinfunction "C29_P$89") (pintype "bidirectional"))
    )
    (net (code "1020") (name "ZZ.10.039") (class "Default")
      (node (ref "U$5") (pin "P$149") (pinfunction "E29_P$149") (pintype "bidirectional"))
    )
    (net (code "1021") (name "ZZ.10.040") (class "Default")
      (node (ref "U$5") (pin "P$70") (pinfunction "C10_P$70") (pintype "bidirectional"))
    )
    (net (code "1022") (name "ZZ.10.041") (class "Default")
      (node (ref "U$5") (pin "P$130") (pinfunction "E10_P$130") (pintype "bidirectional"))
    )
    (net (code "1023") (name "ZZ.10.042") (class "Default")
      (node (ref "U$5") (pin "P$66") (pinfunction "C6_P$66") (pintype "bidirectional"))
    )
    (net (code "1024") (name "ZZ.10.043") (class "Default")
      (node (ref "U$5") (pin "P$126") (pinfunction "E6_P$126") (pintype "bidirectional"))
    )
    (net (code "1025") (name "ZZ.10.044") (class "Default")
      (node (ref "U$5") (pin "P$63") (pinfunction "C3_P$63") (pintype "bidirectional"))
    )
    (net (code "1026") (name "ZZ.10.045") (class "Default")
      (node (ref "U$5") (pin "P$123") (pinfunction "E3_P$123") (pintype "bidirectional"))
    )
    (net (code "1027") (name "ZZ.10.046") (class "Default")
      (node (ref "U$7") (pin "P$118") (pinfunction "D28_P$118") (pintype "bidirectional"))
    )
    (net (code "1028") (name "ZZ.10.047") (class "Default")
      (node (ref "U$7") (pin "P$116") (pinfunction "D26_P$116") (pintype "bidirectional"))
    )
    (net (code "1029") (name "ZZ.10.048") (class "Default")
      (node (ref "U$7") (pin "P$148") (pinfunction "E28_P$148") (pintype "bidirectional"))
    )
    (net (code "1030") (name "ZZ.10.049") (class "Default")
      (node (ref "U$7") (pin "P$175") (pinfunction "F25_P$175") (pintype "bidirectional"))
    )
    (net (code "1031") (name "ZZ.10.050") (class "Default")
      (node (ref "U$7") (pin "P$80") (pinfunction "C20_P$80") (pintype "bidirectional"))
    )
    (net (code "1032") (name "ZZ.10.051") (class "Default")
      (node (ref "U$7") (pin "P$140") (pinfunction "E20_P$140") (pintype "bidirectional"))
    )
    (net (code "1033") (name "ZZ.10.052") (class "Default")
      (node (ref "U$7") (pin "P$77") (pinfunction "C17_P$77") (pintype "bidirectional"))
    )
    (net (code "1034") (name "ZZ.10.053") (class "Default")
      (node (ref "U$7") (pin "P$137") (pinfunction "E17_P$137") (pintype "bidirectional"))
    )
    (net (code "1035") (name "ZZ.10.054") (class "Default")
      (node (ref "U$7") (pin "P$73") (pinfunction "C13_P$73") (pintype "bidirectional"))
    )
    (net (code "1036") (name "ZZ.10.055") (class "Default")
      (node (ref "U$7") (pin "P$133") (pinfunction "E13_P$133") (pintype "bidirectional"))
    )
    (net (code "1037") (name "ZZ.10.056") (class "Default")
      (node (ref "U$7") (pin "P$70") (pinfunction "C10_P$70") (pintype "bidirectional"))
    )
    (net (code "1038") (name "ZZ.10.057") (class "Default")
      (node (ref "U$7") (pin "P$130") (pinfunction "E10_P$130") (pintype "bidirectional"))
    )
    (net (code "1039") (name "ZZ.10.058") (class "Default")
      (node (ref "U$7") (pin "P$66") (pinfunction "C6_P$66") (pintype "bidirectional"))
    )
    (net (code "1040") (name "ZZ.10.059") (class "Default")
      (node (ref "U$7") (pin "P$126") (pinfunction "E6_P$126") (pintype "bidirectional"))
    )
    (net (code "1041") (name "ZZ.10.060") (class "Default")
      (node (ref "U$7") (pin "P$63") (pinfunction "C3_P$63") (pintype "bidirectional"))
    )
    (net (code "1042") (name "ZZ.10.061") (class "Default")
      (node (ref "U$7") (pin "P$123") (pinfunction "E3_P$123") (pintype "bidirectional"))
    )
    (net (code "1043") (name "ZZ.10.062") (class "Default")
      (node (ref "U$9") (pin "P$118") (pinfunction "D28_P$118") (pintype "bidirectional"))
    )
    (net (code "1044") (name "ZZ.10.063") (class "Default")
      (node (ref "U$9") (pin "P$116") (pinfunction "D26_P$116") (pintype "bidirectional"))
    )
    (net (code "1045") (name "ZZ.10.064") (class "Default")
      (node (ref "U$9") (pin "P$148") (pinfunction "E28_P$148") (pintype "bidirectional"))
    )
    (net (code "1046") (name "ZZ.10.065") (class "Default")
      (node (ref "U$9") (pin "P$175") (pinfunction "F25_P$175") (pintype "bidirectional"))
    )
    (net (code "1047") (name "ZZ.10.066") (class "Default")
      (node (ref "U$9") (pin "P$80") (pinfunction "C20_P$80") (pintype "bidirectional"))
    )
    (net (code "1048") (name "ZZ.10.067") (class "Default")
      (node (ref "U$9") (pin "P$140") (pinfunction "E20_P$140") (pintype "bidirectional"))
    )
    (net (code "1049") (name "ZZ.10.068") (class "Default")
      (node (ref "U$9") (pin "P$77") (pinfunction "C17_P$77") (pintype "bidirectional"))
    )
    (net (code "1050") (name "ZZ.10.069") (class "Default")
      (node (ref "U$9") (pin "P$137") (pinfunction "E17_P$137") (pintype "bidirectional"))
    )
    (net (code "1051") (name "ZZ.10.070") (class "Default")
      (node (ref "U$9") (pin "P$73") (pinfunction "C13_P$73") (pintype "bidirectional"))
    )
    (net (code "1052") (name "ZZ.10.071") (class "Default")
      (node (ref "U$9") (pin "P$133") (pinfunction "E13_P$133") (pintype "bidirectional"))
    )
    (net (code "1053") (name "ZZ.10.072") (class "Default")
      (node (ref "U$9") (pin "P$70") (pinfunction "C10_P$70") (pintype "bidirectional"))
    )
    (net (code "1054") (name "ZZ.10.073") (class "Default")
      (node (ref "U$9") (pin "P$130") (pinfunction "E10_P$130") (pintype "bidirectional"))
    )
    (net (code "1055") (name "ZZ.10.074") (class "Default")
      (node (ref "U$9") (pin "P$66") (pinfunction "C6_P$66") (pintype "bidirectional"))
    )
    (net (code "1056") (name "ZZ.10.075") (class "Default")
      (node (ref "U$9") (pin "P$126") (pinfunction "E6_P$126") (pintype "bidirectional"))
    )
    (net (code "1057") (name "ZZ.10.076") (class "Default")
      (node (ref "U$9") (pin "P$63") (pinfunction "C3_P$63") (pintype "bidirectional"))
    )
    (net (code "1058") (name "ZZ.10.077") (class "Default")
      (node (ref "U$9") (pin "P$123") (pinfunction "E3_P$123") (pintype "bidirectional"))
    )
    (net (code "1059") (name "ZZ.10.078") (class "Default")
      (node (ref "U$11") (pin "P$149") (pinfunction "E29_P$149") (pintype "bidirectional"))
    )
    (net (code "1060") (name "ZZ.10.079") (class "Default")
      (node (ref "U$11") (pin "P$178") (pinfunction "F28_P$178") (pintype "bidirectional"))
    )
    (net (code "1061") (name "ZZ.10.080") (class "Default")
      (node (ref "U$11") (pin "P$146") (pinfunction "E26_P$146") (pintype "bidirectional"))
    )
    (net (code "1062") (name "ZZ.10.081") (class "Default")
      (node (ref "U$11") (pin "P$175") (pinfunction "F25_P$175") (pintype "bidirectional"))
    )
    (net (code "1063") (name "ZZ.10.082") (class "Default")
      (node (ref "U$11") (pin "P$142") (pinfunction "E22_P$142") (pintype "bidirectional"))
    )
    (net (code "1064") (name "ZZ.10.083") (class "Default")
      (node (ref "U$11") (pin "P$171") (pinfunction "F21_P$171") (pintype "bidirectional"))
    )
    (net (code "1065") (name "ZZ.10.084") (class "Default")
      (node (ref "U$11") (pin "P$139") (pinfunction "E19_P$139") (pintype "bidirectional"))
    )
    (net (code "1066") (name "ZZ.10.085") (class "Default")
      (node (ref "U$11") (pin "P$168") (pinfunction "F18_P$168") (pintype "bidirectional"))
    )
    (net (code "1067") (name "ZZ.10.086") (class "Default")
      (node (ref "U$11") (pin "P$135") (pinfunction "E15_P$135") (pintype "bidirectional"))
    )
    (net (code "1068") (name "ZZ.10.087") (class "Default")
      (node (ref "U$11") (pin "P$164") (pinfunction "F14_P$164") (pintype "bidirectional"))
    )
    (net (code "1069") (name "ZZ.10.088") (class "Default")
      (node (ref "U$11") (pin "P$132") (pinfunction "E12_P$132") (pintype "bidirectional"))
    )
    (net (code "1070") (name "ZZ.10.089") (class "Default")
      (node (ref "U$11") (pin "P$161") (pinfunction "F11_P$161") (pintype "bidirectional"))
    )
    (net (code "1071") (name "ZZ.10.090") (class "Default")
      (node (ref "U$11") (pin "P$128") (pinfunction "E8_P$128") (pintype "bidirectional"))
    )
    (net (code "1072") (name "ZZ.10.091") (class "Default")
      (node (ref "U$11") (pin "P$157") (pinfunction "F7_P$157") (pintype "bidirectional"))
    )
    (net (code "1073") (name "ZZ.10.092") (class "Default")
      (node (ref "U$11") (pin "P$125") (pinfunction "E5_P$125") (pintype "bidirectional"))
    )
    (net (code "1074") (name "ZZ.10.093") (class "Default")
      (node (ref "U$11") (pin "P$154") (pinfunction "F4_P$154") (pintype "bidirectional"))
    )
    (net (code "1075") (name "ZZ.11.000") (class "Default")
      (node (ref "U$1") (pin "P$126") (pinfunction "E6_P$126") (pintype "bidirectional"))
    )
    (net (code "1076") (name "ZZ.11.001") (class "Default")
      (node (ref "U$1") (pin "P$98") (pinfunction "D8_P$98") (pintype "bidirectional"))
    )
    (net (code "1077") (name "ZZ.11.002") (class "Default")
      (node (ref "U$1") (pin "P$130") (pinfunction "E10_P$130") (pintype "bidirectional"))
    )
    (net (code "1078") (name "ZZ.11.003") (class "Default")
      (node (ref "U$1") (pin "P$102") (pinfunction "D12_P$102") (pintype "bidirectional"))
    )
    (net (code "1079") (name "ZZ.11.004") (class "Default")
      (node (ref "U$1") (pin "P$133") (pinfunction "E13_P$133") (pintype "bidirectional"))
    )
    (net (code "1080") (name "ZZ.11.005") (class "Default")
      (node (ref "U$1") (pin "P$105") (pinfunction "D15_P$105") (pintype "bidirectional"))
    )
    (net (code "1081") (name "ZZ.11.006") (class "Default")
      (node (ref "U$1") (pin "P$137") (pinfunction "E17_P$137") (pintype "bidirectional"))
    )
    (net (code "1082") (name "ZZ.11.007") (class "Default")
      (node (ref "U$1") (pin "P$109") (pinfunction "D19_P$109") (pintype "bidirectional"))
    )
    (net (code "1083") (name "ZZ.11.008") (class "Default")
      (node (ref "U$1") (pin "P$140") (pinfunction "E20_P$140") (pintype "bidirectional"))
    )
    (net (code "1084") (name "ZZ.11.009") (class "Default")
      (node (ref "U$1") (pin "P$112") (pinfunction "D22_P$112") (pintype "bidirectional"))
    )
    (net (code "1085") (name "ZZ.11.010") (class "Default")
      (node (ref "U$1") (pin "P$144") (pinfunction "E24_P$144") (pintype "bidirectional"))
    )
    (net (code "1086") (name "ZZ.11.011") (class "Default")
      (node (ref "U$1") (pin "P$116") (pinfunction "D26_P$116") (pintype "bidirectional"))
    )
    (net (code "1087") (name "ZZ.11.012") (class "Default")
      (node (ref "U$1") (pin "P$147") (pinfunction "E27_P$147") (pintype "bidirectional"))
    )
    (net (code "1088") (name "ZZ.11.013") (class "Default")
      (node (ref "U$1") (pin "P$119") (pinfunction "D29_P$119") (pintype "bidirectional"))
    )
    (net (code "1089") (name "ZZ.11.014") (class "Default")
      (node (ref "U$3") (pin "P$64") (pinfunction "C4_P$64") (pintype "bidirectional"))
    )
    (net (code "1090") (name "ZZ.11.015") (class "Default")
      (node (ref "U$3") (pin "P$124") (pinfunction "E4_P$124") (pintype "bidirectional"))
    )
    (net (code "1091") (name "ZZ.11.016") (class "Default")
      (node (ref "U$3") (pin "P$67") (pinfunction "C7_P$67") (pintype "bidirectional"))
    )
    (net (code "1092") (name "ZZ.11.017") (class "Default")
      (node (ref "U$3") (pin "P$127") (pinfunction "E7_P$127") (pintype "bidirectional"))
    )
    (net (code "1093") (name "ZZ.11.018") (class "Default")
      (node (ref "U$3") (pin "P$71") (pinfunction "C11_P$71") (pintype "bidirectional"))
    )
    (net (code "1094") (name "ZZ.11.019") (class "Default")
      (node (ref "U$3") (pin "P$131") (pinfunction "E11_P$131") (pintype "bidirectional"))
    )
    (net (code "1095") (name "ZZ.11.020") (class "Default")
      (node (ref "U$3") (pin "P$74") (pinfunction "C14_P$74") (pintype "bidirectional"))
    )
    (net (code "1096") (name "ZZ.11.021") (class "Default")
      (node (ref "U$3") (pin "P$134") (pinfunction "E14_P$134") (pintype "bidirectional"))
    )
    (net (code "1097") (name "ZZ.11.022") (class "Default")
      (node (ref "U$3") (pin "P$78") (pinfunction "C18_P$78") (pintype "bidirectional"))
    )
    (net (code "1098") (name "ZZ.11.023") (class "Default")
      (node (ref "U$3") (pin "P$138") (pinfunction "E18_P$138") (pintype "bidirectional"))
    )
    (net (code "1099") (name "ZZ.11.024") (class "Default")
      (node (ref "U$3") (pin "P$81") (pinfunction "C21_P$81") (pintype "bidirectional"))
    )
    (net (code "1100") (name "ZZ.11.025") (class "Default")
      (node (ref "U$3") (pin "P$141") (pinfunction "E21_P$141") (pintype "bidirectional"))
    )
    (net (code "1101") (name "ZZ.11.026") (class "Default")
      (node (ref "U$3") (pin "P$88") (pinfunction "C28_P$88") (pintype "bidirectional"))
    )
    (net (code "1102") (name "ZZ.11.027") (class "Default")
      (node (ref "U$3") (pin "P$86") (pinfunction "C26_P$86") (pintype "bidirectional"))
    )
    (net (code "1103") (name "ZZ.11.028") (class "Default")
      (node (ref "U$3") (pin "P$173") (pinfunction "F23_P$173") (pintype "bidirectional"))
    )
    (net (code "1104") (name "ZZ.11.029") (class "Default")
      (node (ref "U$3") (pin "P$145") (pinfunction "E25_P$145") (pintype "bidirectional"))
    )
    (net (code "1105") (name "ZZ.11.030") (class "Default")
      (node (ref "U$5") (pin "P$74") (pinfunction "C14_P$74") (pintype "bidirectional"))
    )
    (net (code "1106") (name "ZZ.11.031") (class "Default")
      (node (ref "U$5") (pin "P$134") (pinfunction "E14_P$134") (pintype "bidirectional"))
    )
    (net (code "1107") (name "ZZ.11.032") (class "Default")
      (node (ref "U$5") (pin "P$78") (pinfunction "C18_P$78") (pintype "bidirectional"))
    )
    (net (code "1108") (name "ZZ.11.033") (class "Default")
      (node (ref "U$5") (pin "P$138") (pinfunction "E18_P$138") (pintype "bidirectional"))
    )
    (net (code "1109") (name "ZZ.11.034") (class "Default")
      (node (ref "U$5") (pin "P$81") (pinfunction "C21_P$81") (pintype "bidirectional"))
    )
    (net (code "1110") (name "ZZ.11.035") (class "Default")
      (node (ref "U$5") (pin "P$141") (pinfunction "E21_P$141") (pintype "bidirectional"))
    )
    (net (code "1111") (name "ZZ.11.036") (class "Default")
      (node (ref "U$5") (pin "P$85") (pinfunction "C25_P$85") (pintype "bidirectional"))
    )
    (net (code "1112") (name "ZZ.11.037") (class "Default")
      (node (ref "U$5") (pin "P$145") (pinfunction "E25_P$145") (pintype "bidirectional"))
    )
    (net (code "1113") (name "ZZ.11.038") (class "Default")
      (node (ref "U$5") (pin "P$88") (pinfunction "C28_P$88") (pintype "bidirectional"))
    )
    (net (code "1114") (name "ZZ.11.039") (class "Default")
      (node (ref "U$5") (pin "P$148") (pinfunction "E28_P$148") (pintype "bidirectional"))
    )
    (net (code "1115") (name "ZZ.11.040") (class "Default")
      (node (ref "U$5") (pin "P$71") (pinfunction "C11_P$71") (pintype "bidirectional"))
    )
    (net (code "1116") (name "ZZ.11.041") (class "Default")
      (node (ref "U$5") (pin "P$131") (pinfunction "E11_P$131") (pintype "bidirectional"))
    )
    (net (code "1117") (name "ZZ.11.042") (class "Default")
      (node (ref "U$5") (pin "P$67") (pinfunction "C7_P$67") (pintype "bidirectional"))
    )
    (net (code "1118") (name "ZZ.11.043") (class "Default")
      (node (ref "U$5") (pin "P$127") (pinfunction "E7_P$127") (pintype "bidirectional"))
    )
    (net (code "1119") (name "ZZ.11.044") (class "Default")
      (node (ref "U$5") (pin "P$64") (pinfunction "C4_P$64") (pintype "bidirectional"))
    )
    (net (code "1120") (name "ZZ.11.045") (class "Default")
      (node (ref "U$5") (pin "P$124") (pinfunction "E4_P$124") (pintype "bidirectional"))
    )
    (net (code "1121") (name "ZZ.11.046") (class "Default")
      (node (ref "U$7") (pin "P$88") (pinfunction "C28_P$88") (pintype "bidirectional"))
    )
    (net (code "1122") (name "ZZ.11.047") (class "Default")
      (node (ref "U$7") (pin "P$86") (pinfunction "C26_P$86") (pintype "bidirectional"))
    )
    (net (code "1123") (name "ZZ.11.048") (class "Default")
      (node (ref "U$7") (pin "P$173") (pinfunction "F23_P$173") (pintype "bidirectional"))
    )
    (net (code "1124") (name "ZZ.11.049") (class "Default")
      (node (ref "U$7") (pin "P$145") (pinfunction "E25_P$145") (pintype "bidirectional"))
    )
    (net (code "1125") (name "ZZ.11.050") (class "Default")
      (node (ref "U$7") (pin "P$81") (pinfunction "C21_P$81") (pintype "bidirectional"))
    )
    (net (code "1126") (name "ZZ.11.051") (class "Default")
      (node (ref "U$7") (pin "P$141") (pinfunction "E21_P$141") (pintype "bidirectional"))
    )
    (net (code "1127") (name "ZZ.11.052") (class "Default")
      (node (ref "U$7") (pin "P$78") (pinfunction "C18_P$78") (pintype "bidirectional"))
    )
    (net (code "1128") (name "ZZ.11.053") (class "Default")
      (node (ref "U$7") (pin "P$138") (pinfunction "E18_P$138") (pintype "bidirectional"))
    )
    (net (code "1129") (name "ZZ.11.054") (class "Default")
      (node (ref "U$7") (pin "P$74") (pinfunction "C14_P$74") (pintype "bidirectional"))
    )
    (net (code "1130") (name "ZZ.11.055") (class "Default")
      (node (ref "U$7") (pin "P$134") (pinfunction "E14_P$134") (pintype "bidirectional"))
    )
    (net (code "1131") (name "ZZ.11.056") (class "Default")
      (node (ref "U$7") (pin "P$71") (pinfunction "C11_P$71") (pintype "bidirectional"))
    )
    (net (code "1132") (name "ZZ.11.057") (class "Default")
      (node (ref "U$7") (pin "P$131") (pinfunction "E11_P$131") (pintype "bidirectional"))
    )
    (net (code "1133") (name "ZZ.11.058") (class "Default")
      (node (ref "U$7") (pin "P$67") (pinfunction "C7_P$67") (pintype "bidirectional"))
    )
    (net (code "1134") (name "ZZ.11.059") (class "Default")
      (node (ref "U$7") (pin "P$127") (pinfunction "E7_P$127") (pintype "bidirectional"))
    )
    (net (code "1135") (name "ZZ.11.060") (class "Default")
      (node (ref "U$7") (pin "P$64") (pinfunction "C4_P$64") (pintype "bidirectional"))
    )
    (net (code "1136") (name "ZZ.11.061") (class "Default")
      (node (ref "U$7") (pin "P$124") (pinfunction "E4_P$124") (pintype "bidirectional"))
    )
    (net (code "1137") (name "ZZ.11.062") (class "Default")
      (node (ref "U$9") (pin "P$88") (pinfunction "C28_P$88") (pintype "bidirectional"))
    )
    (net (code "1138") (name "ZZ.11.063") (class "Default")
      (node (ref "U$9") (pin "P$86") (pinfunction "C26_P$86") (pintype "bidirectional"))
    )
    (net (code "1139") (name "ZZ.11.064") (class "Default")
      (node (ref "U$9") (pin "P$173") (pinfunction "F23_P$173") (pintype "bidirectional"))
    )
    (net (code "1140") (name "ZZ.11.065") (class "Default")
      (node (ref "U$9") (pin "P$145") (pinfunction "E25_P$145") (pintype "bidirectional"))
    )
    (net (code "1141") (name "ZZ.11.066") (class "Default")
      (node (ref "U$9") (pin "P$81") (pinfunction "C21_P$81") (pintype "bidirectional"))
    )
    (net (code "1142") (name "ZZ.11.067") (class "Default")
      (node (ref "U$9") (pin "P$141") (pinfunction "E21_P$141") (pintype "bidirectional"))
    )
    (net (code "1143") (name "ZZ.11.068") (class "Default")
      (node (ref "U$9") (pin "P$78") (pinfunction "C18_P$78") (pintype "bidirectional"))
    )
    (net (code "1144") (name "ZZ.11.069") (class "Default")
      (node (ref "U$9") (pin "P$138") (pinfunction "E18_P$138") (pintype "bidirectional"))
    )
    (net (code "1145") (name "ZZ.11.070") (class "Default")
      (node (ref "U$9") (pin "P$74") (pinfunction "C14_P$74") (pintype "bidirectional"))
    )
    (net (code "1146") (name "ZZ.11.071") (class "Default")
      (node (ref "U$9") (pin "P$134") (pinfunction "E14_P$134") (pintype "bidirectional"))
    )
    (net (code "1147") (name "ZZ.11.072") (class "Default")
      (node (ref "U$9") (pin "P$71") (pinfunction "C11_P$71") (pintype "bidirectional"))
    )
    (net (code "1148") (name "ZZ.11.073") (class "Default")
      (node (ref "U$9") (pin "P$131") (pinfunction "E11_P$131") (pintype "bidirectional"))
    )
    (net (code "1149") (name "ZZ.11.074") (class "Default")
      (node (ref "U$9") (pin "P$67") (pinfunction "C7_P$67") (pintype "bidirectional"))
    )
    (net (code "1150") (name "ZZ.11.075") (class "Default")
      (node (ref "U$9") (pin "P$127") (pinfunction "E7_P$127") (pintype "bidirectional"))
    )
    (net (code "1151") (name "ZZ.11.076") (class "Default")
      (node (ref "U$9") (pin "P$64") (pinfunction "C4_P$64") (pintype "bidirectional"))
    )
    (net (code "1152") (name "ZZ.11.077") (class "Default")
      (node (ref "U$9") (pin "P$124") (pinfunction "E4_P$124") (pintype "bidirectional"))
    )
    (net (code "1153") (name "ZZ.11.078") (class "Default")
      (node (ref "U$11") (pin "P$118") (pinfunction "D28_P$118") (pintype "bidirectional"))
    )
    (net (code "1154") (name "ZZ.11.079") (class "Default")
      (node (ref "U$11") (pin "P$147") (pinfunction "E27_P$147") (pintype "bidirectional"))
    )
    (net (code "1155") (name "ZZ.11.080") (class "Default")
      (node (ref "U$11") (pin "P$115") (pinfunction "D25_P$115") (pintype "bidirectional"))
    )
    (net (code "1156") (name "ZZ.11.081") (class "Default")
      (node (ref "U$11") (pin "P$144") (pinfunction "E24_P$144") (pintype "bidirectional"))
    )
    (net (code "1157") (name "ZZ.11.082") (class "Default")
      (node (ref "U$11") (pin "P$111") (pinfunction "D21_P$111") (pintype "bidirectional"))
    )
    (net (code "1158") (name "ZZ.11.083") (class "Default")
      (node (ref "U$11") (pin "P$140") (pinfunction "E20_P$140") (pintype "bidirectional"))
    )
    (net (code "1159") (name "ZZ.11.084") (class "Default")
      (node (ref "U$11") (pin "P$108") (pinfunction "D18_P$108") (pintype "bidirectional"))
    )
    (net (code "1160") (name "ZZ.11.085") (class "Default")
      (node (ref "U$11") (pin "P$137") (pinfunction "E17_P$137") (pintype "bidirectional"))
    )
    (net (code "1161") (name "ZZ.11.086") (class "Default")
      (node (ref "U$11") (pin "P$104") (pinfunction "D14_P$104") (pintype "bidirectional"))
    )
    (net (code "1162") (name "ZZ.11.087") (class "Default")
      (node (ref "U$11") (pin "P$133") (pinfunction "E13_P$133") (pintype "bidirectional"))
    )
    (net (code "1163") (name "ZZ.11.088") (class "Default")
      (node (ref "U$11") (pin "P$101") (pinfunction "D11_P$101") (pintype "bidirectional"))
    )
    (net (code "1164") (name "ZZ.11.089") (class "Default")
      (node (ref "U$11") (pin "P$130") (pinfunction "E10_P$130") (pintype "bidirectional"))
    )
    (net (code "1165") (name "ZZ.11.090") (class "Default")
      (node (ref "U$11") (pin "P$97") (pinfunction "D7_P$97") (pintype "bidirectional"))
    )
    (net (code "1166") (name "ZZ.11.091") (class "Default")
      (node (ref "U$11") (pin "P$126") (pinfunction "E6_P$126") (pintype "bidirectional"))
    )
    (net (code "1167") (name "ZZ.11.092") (class "Default")
      (node (ref "U$11") (pin "P$94") (pinfunction "D4_P$94") (pintype "bidirectional"))
    )
    (net (code "1168") (name "ZZ.11.093") (class "Default")
      (node (ref "U$11") (pin "P$123") (pinfunction "E3_P$123") (pintype "bidirectional"))
    )
    (net (code "1169") (name "ZZ.12.000") (class "Default")
      (node (ref "U$1") (pin "P$96") (pinfunction "D6_P$96") (pintype "bidirectional"))
    )
    (net (code "1170") (name "ZZ.12.001") (class "Default")
      (node (ref "U$1") (pin "P$97") (pinfunction "D7_P$97") (pintype "bidirectional"))
    )
    (net (code "1171") (name "ZZ.12.002") (class "Default")
      (node (ref "U$1") (pin "P$100") (pinfunction "D10_P$100") (pintype "bidirectional"))
    )
    (net (code "1172") (name "ZZ.12.003") (class "Default")
      (node (ref "U$1") (pin "P$101") (pinfunction "D11_P$101") (pintype "bidirectional"))
    )
    (net (code "1173") (name "ZZ.12.004") (class "Default")
      (node (ref "U$1") (pin "P$103") (pinfunction "D13_P$103") (pintype "bidirectional"))
    )
    (net (code "1174") (name "ZZ.12.005") (class "Default")
      (node (ref "U$1") (pin "P$104") (pinfunction "D14_P$104") (pintype "bidirectional"))
    )
    (net (code "1175") (name "ZZ.12.006") (class "Default")
      (node (ref "U$1") (pin "P$107") (pinfunction "D17_P$107") (pintype "bidirectional"))
    )
    (net (code "1176") (name "ZZ.12.007") (class "Default")
      (node (ref "U$1") (pin "P$108") (pinfunction "D18_P$108") (pintype "bidirectional"))
    )
    (net (code "1177") (name "ZZ.12.008") (class "Default")
      (node (ref "U$1") (pin "P$110") (pinfunction "D20_P$110") (pintype "bidirectional"))
    )
    (net (code "1178") (name "ZZ.12.009") (class "Default")
      (node (ref "U$1") (pin "P$111") (pinfunction "D21_P$111") (pintype "bidirectional"))
    )
    (net (code "1179") (name "ZZ.12.010") (class "Default")
      (node (ref "U$1") (pin "P$114") (pinfunction "D24_P$114") (pintype "bidirectional"))
    )
    (net (code "1180") (name "ZZ.12.011") (class "Default")
      (node (ref "U$1") (pin "P$115") (pinfunction "D25_P$115") (pintype "bidirectional"))
    )
    (net (code "1181") (name "ZZ.12.012") (class "Default")
      (node (ref "U$1") (pin "P$117") (pinfunction "D27_P$117") (pintype "bidirectional"))
    )
    (net (code "1182") (name "ZZ.12.013") (class "Default")
      (node (ref "U$1") (pin "P$118") (pinfunction "D28_P$118") (pintype "bidirectional"))
    )
    (net (code "1183") (name "ZZ.12.014") (class "Default")
      (node (ref "U$3") (pin "P$63") (pinfunction "C3_P$63") (pintype "bidirectional"))
    )
    (net (code "1184") (name "ZZ.12.015") (class "Default")
      (node (ref "U$3") (pin "P$123") (pinfunction "E3_P$123") (pintype "bidirectional"))
    )
    (net (code "1185") (name "ZZ.12.016") (class "Default")
      (node (ref "U$3") (pin "P$66") (pinfunction "C6_P$66") (pintype "bidirectional"))
    )
    (net (code "1186") (name "ZZ.12.017") (class "Default")
      (node (ref "U$3") (pin "P$126") (pinfunction "E6_P$126") (pintype "bidirectional"))
    )
    (net (code "1187") (name "ZZ.12.018") (class "Default")
      (node (ref "U$3") (pin "P$70") (pinfunction "C10_P$70") (pintype "bidirectional"))
    )
    (net (code "1188") (name "ZZ.12.019") (class "Default")
      (node (ref "U$3") (pin "P$130") (pinfunction "E10_P$130") (pintype "bidirectional"))
    )
    (net (code "1189") (name "ZZ.12.020") (class "Default")
      (node (ref "U$3") (pin "P$73") (pinfunction "C13_P$73") (pintype "bidirectional"))
    )
    (net (code "1190") (name "ZZ.12.021") (class "Default")
      (node (ref "U$3") (pin "P$133") (pinfunction "E13_P$133") (pintype "bidirectional"))
    )
    (net (code "1191") (name "ZZ.12.022") (class "Default")
      (node (ref "U$3") (pin "P$77") (pinfunction "C17_P$77") (pintype "bidirectional"))
    )
    (net (code "1192") (name "ZZ.12.023") (class "Default")
      (node (ref "U$3") (pin "P$137") (pinfunction "E17_P$137") (pintype "bidirectional"))
    )
    (net (code "1193") (name "ZZ.12.024") (class "Default")
      (node (ref "U$3") (pin "P$80") (pinfunction "C20_P$80") (pintype "bidirectional"))
    )
    (net (code "1194") (name "ZZ.12.025") (class "Default")
      (node (ref "U$3") (pin "P$140") (pinfunction "E20_P$140") (pintype "bidirectional"))
    )
    (net (code "1195") (name "ZZ.12.026") (class "Default")
      (node (ref "U$3") (pin "P$58") (pinfunction "B28_P$58") (pintype "bidirectional"))
    )
    (net (code "1196") (name "ZZ.12.027") (class "Default")
      (node (ref "U$3") (pin "P$56") (pinfunction "B26_P$56") (pintype "bidirectional"))
    )
    (net (code "1197") (name "ZZ.12.028") (class "Default")
      (node (ref "U$3") (pin "P$177") (pinfunction "F27_P$177") (pintype "bidirectional"))
    )
    (net (code "1198") (name "ZZ.12.029") (class "Default")
      (node (ref "U$3") (pin "P$115") (pinfunction "D25_P$115") (pintype "bidirectional"))
    )
    (net (code "1199") (name "ZZ.12.030") (class "Default")
      (node (ref "U$5") (pin "P$73") (pinfunction "C13_P$73") (pintype "bidirectional"))
    )
    (net (code "1200") (name "ZZ.12.031") (class "Default")
      (node (ref "U$5") (pin "P$133") (pinfunction "E13_P$133") (pintype "bidirectional"))
    )
    (net (code "1201") (name "ZZ.12.032") (class "Default")
      (node (ref "U$5") (pin "P$77") (pinfunction "C17_P$77") (pintype "bidirectional"))
    )
    (net (code "1202") (name "ZZ.12.033") (class "Default")
      (node (ref "U$5") (pin "P$137") (pinfunction "E17_P$137") (pintype "bidirectional"))
    )
    (net (code "1203") (name "ZZ.12.034") (class "Default")
      (node (ref "U$5") (pin "P$80") (pinfunction "C20_P$80") (pintype "bidirectional"))
    )
    (net (code "1204") (name "ZZ.12.035") (class "Default")
      (node (ref "U$5") (pin "P$140") (pinfunction "E20_P$140") (pintype "bidirectional"))
    )
    (net (code "1205") (name "ZZ.12.036") (class "Default")
      (node (ref "U$5") (pin "P$84") (pinfunction "C24_P$84") (pintype "bidirectional"))
    )
    (net (code "1206") (name "ZZ.12.037") (class "Default")
      (node (ref "U$5") (pin "P$144") (pinfunction "E24_P$144") (pintype "bidirectional"))
    )
    (net (code "1207") (name "ZZ.12.038") (class "Default")
      (node (ref "U$5") (pin "P$87") (pinfunction "C27_P$87") (pintype "bidirectional"))
    )
    (net (code "1208") (name "ZZ.12.039") (class "Default")
      (node (ref "U$5") (pin "P$147") (pinfunction "E27_P$147") (pintype "bidirectional"))
    )
    (net (code "1209") (name "ZZ.12.040") (class "Default")
      (node (ref "U$5") (pin "P$72") (pinfunction "C12_P$72") (pintype "bidirectional"))
    )
    (net (code "1210") (name "ZZ.12.041") (class "Default")
      (node (ref "U$5") (pin "P$132") (pinfunction "E12_P$132") (pintype "bidirectional"))
    )
    (net (code "1211") (name "ZZ.12.042") (class "Default")
      (node (ref "U$5") (pin "P$68") (pinfunction "C8_P$68") (pintype "bidirectional"))
    )
    (net (code "1212") (name "ZZ.12.043") (class "Default")
      (node (ref "U$5") (pin "P$128") (pinfunction "E8_P$128") (pintype "bidirectional"))
    )
    (net (code "1213") (name "ZZ.12.044") (class "Default")
      (node (ref "U$5") (pin "P$65") (pinfunction "C5_P$65") (pintype "bidirectional"))
    )
    (net (code "1214") (name "ZZ.12.045") (class "Default")
      (node (ref "U$5") (pin "P$125") (pinfunction "E5_P$125") (pintype "bidirectional"))
    )
    (net (code "1215") (name "ZZ.12.046") (class "Default")
      (node (ref "U$7") (pin "P$58") (pinfunction "B28_P$58") (pintype "bidirectional"))
    )
    (net (code "1216") (name "ZZ.12.047") (class "Default")
      (node (ref "U$7") (pin "P$56") (pinfunction "B26_P$56") (pintype "bidirectional"))
    )
    (net (code "1217") (name "ZZ.12.048") (class "Default")
      (node (ref "U$7") (pin "P$177") (pinfunction "F27_P$177") (pintype "bidirectional"))
    )
    (net (code "1218") (name "ZZ.12.049") (class "Default")
      (node (ref "U$7") (pin "P$115") (pinfunction "D25_P$115") (pintype "bidirectional"))
    )
    (net (code "1219") (name "ZZ.12.050") (class "Default")
      (node (ref "U$7") (pin "P$82") (pinfunction "C22_P$82") (pintype "bidirectional"))
    )
    (net (code "1220") (name "ZZ.12.051") (class "Default")
      (node (ref "U$7") (pin "P$142") (pinfunction "E22_P$142") (pintype "bidirectional"))
    )
    (net (code "1221") (name "ZZ.12.052") (class "Default")
      (node (ref "U$7") (pin "P$79") (pinfunction "C19_P$79") (pintype "bidirectional"))
    )
    (net (code "1222") (name "ZZ.12.053") (class "Default")
      (node (ref "U$7") (pin "P$139") (pinfunction "E19_P$139") (pintype "bidirectional"))
    )
    (net (code "1223") (name "ZZ.12.054") (class "Default")
      (node (ref "U$7") (pin "P$75") (pinfunction "C15_P$75") (pintype "bidirectional"))
    )
    (net (code "1224") (name "ZZ.12.055") (class "Default")
      (node (ref "U$7") (pin "P$135") (pinfunction "E15_P$135") (pintype "bidirectional"))
    )
    (net (code "1225") (name "ZZ.12.056") (class "Default")
      (node (ref "U$7") (pin "P$72") (pinfunction "C12_P$72") (pintype "bidirectional"))
    )
    (net (code "1226") (name "ZZ.12.057") (class "Default")
      (node (ref "U$7") (pin "P$132") (pinfunction "E12_P$132") (pintype "bidirectional"))
    )
    (net (code "1227") (name "ZZ.12.058") (class "Default")
      (node (ref "U$7") (pin "P$68") (pinfunction "C8_P$68") (pintype "bidirectional"))
    )
    (net (code "1228") (name "ZZ.12.059") (class "Default")
      (node (ref "U$7") (pin "P$128") (pinfunction "E8_P$128") (pintype "bidirectional"))
    )
    (net (code "1229") (name "ZZ.12.060") (class "Default")
      (node (ref "U$7") (pin "P$65") (pinfunction "C5_P$65") (pintype "bidirectional"))
    )
    (net (code "1230") (name "ZZ.12.061") (class "Default")
      (node (ref "U$7") (pin "P$125") (pinfunction "E5_P$125") (pintype "bidirectional"))
    )
    (net (code "1231") (name "ZZ.12.062") (class "Default")
      (node (ref "U$9") (pin "P$58") (pinfunction "B28_P$58") (pintype "bidirectional"))
    )
    (net (code "1232") (name "ZZ.12.063") (class "Default")
      (node (ref "U$9") (pin "P$56") (pinfunction "B26_P$56") (pintype "bidirectional"))
    )
    (net (code "1233") (name "ZZ.12.064") (class "Default")
      (node (ref "U$9") (pin "P$177") (pinfunction "F27_P$177") (pintype "bidirectional"))
    )
    (net (code "1234") (name "ZZ.12.065") (class "Default")
      (node (ref "U$9") (pin "P$115") (pinfunction "D25_P$115") (pintype "bidirectional"))
    )
    (net (code "1235") (name "ZZ.12.066") (class "Default")
      (node (ref "U$9") (pin "P$82") (pinfunction "C22_P$82") (pintype "bidirectional"))
    )
    (net (code "1236") (name "ZZ.12.067") (class "Default")
      (node (ref "U$9") (pin "P$142") (pinfunction "E22_P$142") (pintype "bidirectional"))
    )
    (net (code "1237") (name "ZZ.12.068") (class "Default")
      (node (ref "U$9") (pin "P$79") (pinfunction "C19_P$79") (pintype "bidirectional"))
    )
    (net (code "1238") (name "ZZ.12.069") (class "Default")
      (node (ref "U$9") (pin "P$139") (pinfunction "E19_P$139") (pintype "bidirectional"))
    )
    (net (code "1239") (name "ZZ.12.070") (class "Default")
      (node (ref "U$9") (pin "P$75") (pinfunction "C15_P$75") (pintype "bidirectional"))
    )
    (net (code "1240") (name "ZZ.12.071") (class "Default")
      (node (ref "U$9") (pin "P$135") (pinfunction "E15_P$135") (pintype "bidirectional"))
    )
    (net (code "1241") (name "ZZ.12.072") (class "Default")
      (node (ref "U$9") (pin "P$72") (pinfunction "C12_P$72") (pintype "bidirectional"))
    )
    (net (code "1242") (name "ZZ.12.073") (class "Default")
      (node (ref "U$9") (pin "P$132") (pinfunction "E12_P$132") (pintype "bidirectional"))
    )
    (net (code "1243") (name "ZZ.12.074") (class "Default")
      (node (ref "U$9") (pin "P$68") (pinfunction "C8_P$68") (pintype "bidirectional"))
    )
    (net (code "1244") (name "ZZ.12.075") (class "Default")
      (node (ref "U$9") (pin "P$128") (pinfunction "E8_P$128") (pintype "bidirectional"))
    )
    (net (code "1245") (name "ZZ.12.076") (class "Default")
      (node (ref "U$9") (pin "P$65") (pinfunction "C5_P$65") (pintype "bidirectional"))
    )
    (net (code "1246") (name "ZZ.12.077") (class "Default")
      (node (ref "U$9") (pin "P$125") (pinfunction "E5_P$125") (pintype "bidirectional"))
    )
    (net (code "1247") (name "ZZ.12.078") (class "Default")
      (node (ref "U$11") (pin "P$119") (pinfunction "D29_P$119") (pintype "bidirectional"))
    )
    (net (code "1248") (name "ZZ.12.079") (class "Default")
      (node (ref "U$11") (pin "P$117") (pinfunction "D27_P$117") (pintype "bidirectional"))
    )
    (net (code "1249") (name "ZZ.12.080") (class "Default")
      (node (ref "U$11") (pin "P$116") (pinfunction "D26_P$116") (pintype "bidirectional"))
    )
    (net (code "1250") (name "ZZ.12.081") (class "Default")
      (node (ref "U$11") (pin "P$114") (pinfunction "D24_P$114") (pintype "bidirectional"))
    )
    (net (code "1251") (name "ZZ.12.082") (class "Default")
      (node (ref "U$11") (pin "P$112") (pinfunction "D22_P$112") (pintype "bidirectional"))
    )
    (net (code "1252") (name "ZZ.12.083") (class "Default")
      (node (ref "U$11") (pin "P$110") (pinfunction "D20_P$110") (pintype "bidirectional"))
    )
    (net (code "1253") (name "ZZ.12.084") (class "Default")
      (node (ref "U$11") (pin "P$109") (pinfunction "D19_P$109") (pintype "bidirectional"))
    )
    (net (code "1254") (name "ZZ.12.085") (class "Default")
      (node (ref "U$11") (pin "P$107") (pinfunction "D17_P$107") (pintype "bidirectional"))
    )
    (net (code "1255") (name "ZZ.12.086") (class "Default")
      (node (ref "U$11") (pin "P$105") (pinfunction "D15_P$105") (pintype "bidirectional"))
    )
    (net (code "1256") (name "ZZ.12.087") (class "Default")
      (node (ref "U$11") (pin "P$103") (pinfunction "D13_P$103") (pintype "bidirectional"))
    )
    (net (code "1257") (name "ZZ.12.088") (class "Default")
      (node (ref "U$11") (pin "P$102") (pinfunction "D12_P$102") (pintype "bidirectional"))
    )
    (net (code "1258") (name "ZZ.12.089") (class "Default")
      (node (ref "U$11") (pin "P$100") (pinfunction "D10_P$100") (pintype "bidirectional"))
    )
    (net (code "1259") (name "ZZ.12.090") (class "Default")
      (node (ref "U$11") (pin "P$98") (pinfunction "D8_P$98") (pintype "bidirectional"))
    )
    (net (code "1260") (name "ZZ.12.091") (class "Default")
      (node (ref "U$11") (pin "P$96") (pinfunction "D6_P$96") (pintype "bidirectional"))
    )
    (net (code "1261") (name "ZZ.12.092") (class "Default")
      (node (ref "U$11") (pin "P$95") (pinfunction "D5_P$95") (pintype "bidirectional"))
    )
    (net (code "1262") (name "ZZ.12.093") (class "Default")
      (node (ref "U$11") (pin "P$93") (pinfunction "D3_P$93") (pintype "bidirectional"))
    )
    (net (code "1263") (name "ZZ.13.000") (class "Default")
      (node (ref "U$1") (pin "P$127") (pinfunction "E7_P$127") (pintype "bidirectional"))
    )
    (net (code "1264") (name "ZZ.13.001") (class "Default")
      (node (ref "U$1") (pin "P$158") (pinfunction "F8_P$158") (pintype "bidirectional"))
    )
    (net (code "1265") (name "ZZ.13.002") (class "Default")
      (node (ref "U$1") (pin "P$131") (pinfunction "E11_P$131") (pintype "bidirectional"))
    )
    (net (code "1266") (name "ZZ.13.003") (class "Default")
      (node (ref "U$1") (pin "P$162") (pinfunction "F12_P$162") (pintype "bidirectional"))
    )
    (net (code "1267") (name "ZZ.13.004") (class "Default")
      (node (ref "U$1") (pin "P$134") (pinfunction "E14_P$134") (pintype "bidirectional"))
    )
    (net (code "1268") (name "ZZ.13.005") (class "Default")
      (node (ref "U$1") (pin "P$165") (pinfunction "F15_P$165") (pintype "bidirectional"))
    )
    (net (code "1269") (name "ZZ.13.006") (class "Default")
      (node (ref "U$1") (pin "P$138") (pinfunction "E18_P$138") (pintype "bidirectional"))
    )
    (net (code "1270") (name "ZZ.13.007") (class "Default")
      (node (ref "U$1") (pin "P$169") (pinfunction "F19_P$169") (pintype "bidirectional"))
    )
    (net (code "1271") (name "ZZ.13.008") (class "Default")
      (node (ref "U$1") (pin "P$141") (pinfunction "E21_P$141") (pintype "bidirectional"))
    )
    (net (code "1272") (name "ZZ.13.009") (class "Default")
      (node (ref "U$1") (pin "P$172") (pinfunction "F22_P$172") (pintype "bidirectional"))
    )
    (net (code "1273") (name "ZZ.13.010") (class "Default")
      (node (ref "U$1") (pin "P$145") (pinfunction "E25_P$145") (pintype "bidirectional"))
    )
    (net (code "1274") (name "ZZ.13.011") (class "Default")
      (node (ref "U$1") (pin "P$176") (pinfunction "F26_P$176") (pintype "bidirectional"))
    )
    (net (code "1275") (name "ZZ.13.012") (class "Default")
      (node (ref "U$1") (pin "P$148") (pinfunction "E28_P$148") (pintype "bidirectional"))
    )
    (net (code "1276") (name "ZZ.13.013") (class "Default")
      (node (ref "U$1") (pin "P$179") (pinfunction "F29_P$179") (pintype "bidirectional"))
    )
    (net (code "1277") (name "ZZ.13.014") (class "Default")
      (node (ref "U$3") (pin "P$35") (pinfunction "B5_P$35") (pintype "bidirectional"))
    )
    (net (code "1278") (name "ZZ.13.015") (class "Default")
      (node (ref "U$3") (pin "P$95") (pinfunction "D5_P$95") (pintype "bidirectional"))
    )
    (net (code "1279") (name "ZZ.13.016") (class "Default")
      (node (ref "U$3") (pin "P$38") (pinfunction "B8_P$38") (pintype "bidirectional"))
    )
    (net (code "1280") (name "ZZ.13.017") (class "Default")
      (node (ref "U$3") (pin "P$98") (pinfunction "D8_P$98") (pintype "bidirectional"))
    )
    (net (code "1281") (name "ZZ.13.018") (class "Default")
      (node (ref "U$3") (pin "P$42") (pinfunction "B12_P$42") (pintype "bidirectional"))
    )
    (net (code "1282") (name "ZZ.13.019") (class "Default")
      (node (ref "U$3") (pin "P$102") (pinfunction "D12_P$102") (pintype "bidirectional"))
    )
    (net (code "1283") (name "ZZ.13.020") (class "Default")
      (node (ref "U$3") (pin "P$45") (pinfunction "B15_P$45") (pintype "bidirectional"))
    )
    (net (code "1284") (name "ZZ.13.021") (class "Default")
      (node (ref "U$3") (pin "P$105") (pinfunction "D15_P$105") (pintype "bidirectional"))
    )
    (net (code "1285") (name "ZZ.13.022") (class "Default")
      (node (ref "U$3") (pin "P$49") (pinfunction "B19_P$49") (pintype "bidirectional"))
    )
    (net (code "1286") (name "ZZ.13.023") (class "Default")
      (node (ref "U$3") (pin "P$109") (pinfunction "D19_P$109") (pintype "bidirectional"))
    )
    (net (code "1287") (name "ZZ.13.024") (class "Default")
      (node (ref "U$3") (pin "P$52") (pinfunction "B22_P$52") (pintype "bidirectional"))
    )
    (net (code "1288") (name "ZZ.13.025") (class "Default")
      (node (ref "U$3") (pin "P$112") (pinfunction "D22_P$112") (pintype "bidirectional"))
    )
    (net (code "1289") (name "ZZ.13.026") (class "Default")
      (node (ref "U$3") (pin "P$119") (pinfunction "D29_P$119") (pintype "bidirectional"))
    )
    (net (code "1290") (name "ZZ.13.027") (class "Default")
      (node (ref "U$3") (pin "P$117") (pinfunction "D27_P$117") (pintype "bidirectional"))
    )
    (net (code "1291") (name "ZZ.13.028") (class "Default")
      (node (ref "U$3") (pin "P$179") (pinfunction "F29_P$179") (pintype "bidirectional"))
    )
    (net (code "1292") (name "ZZ.13.029") (class "Default")
      (node (ref "U$3") (pin "P$147") (pinfunction "E27_P$147") (pintype "bidirectional"))
    )
    (net (code "1293") (name "ZZ.13.030") (class "Default")
      (node (ref "U$5") (pin "P$45") (pinfunction "B15_P$45") (pintype "bidirectional"))
    )
    (net (code "1294") (name "ZZ.13.031") (class "Default")
      (node (ref "U$5") (pin "P$105") (pinfunction "D15_P$105") (pintype "bidirectional"))
    )
    (net (code "1295") (name "ZZ.13.032") (class "Default")
      (node (ref "U$5") (pin "P$49") (pinfunction "B19_P$49") (pintype "bidirectional"))
    )
    (net (code "1296") (name "ZZ.13.033") (class "Default")
      (node (ref "U$5") (pin "P$109") (pinfunction "D19_P$109") (pintype "bidirectional"))
    )
    (net (code "1297") (name "ZZ.13.034") (class "Default")
      (node (ref "U$5") (pin "P$52") (pinfunction "B22_P$52") (pintype "bidirectional"))
    )
    (net (code "1298") (name "ZZ.13.035") (class "Default")
      (node (ref "U$5") (pin "P$112") (pinfunction "D22_P$112") (pintype "bidirectional"))
    )
    (net (code "1299") (name "ZZ.13.036") (class "Default")
      (node (ref "U$5") (pin "P$56") (pinfunction "B26_P$56") (pintype "bidirectional"))
    )
    (net (code "1300") (name "ZZ.13.037") (class "Default")
      (node (ref "U$5") (pin "P$116") (pinfunction "D26_P$116") (pintype "bidirectional"))
    )
    (net (code "1301") (name "ZZ.13.038") (class "Default")
      (node (ref "U$5") (pin "P$59") (pinfunction "B29_P$59") (pintype "bidirectional"))
    )
    (net (code "1302") (name "ZZ.13.039") (class "Default")
      (node (ref "U$5") (pin "P$119") (pinfunction "D29_P$119") (pintype "bidirectional"))
    )
    (net (code "1303") (name "ZZ.13.040") (class "Default")
      (node (ref "U$5") (pin "P$40") (pinfunction "B10_P$40") (pintype "bidirectional"))
    )
    (net (code "1304") (name "ZZ.13.041") (class "Default")
      (node (ref "U$5") (pin "P$100") (pinfunction "D10_P$100") (pintype "bidirectional"))
    )
    (net (code "1305") (name "ZZ.13.042") (class "Default")
      (node (ref "U$5") (pin "P$36") (pinfunction "B6_P$36") (pintype "bidirectional"))
    )
    (net (code "1306") (name "ZZ.13.043") (class "Default")
      (node (ref "U$5") (pin "P$96") (pinfunction "D6_P$96") (pintype "bidirectional"))
    )
    (net (code "1307") (name "ZZ.13.044") (class "Default")
      (node (ref "U$5") (pin "P$33") (pinfunction "B3_P$33") (pintype "bidirectional"))
    )
    (net (code "1308") (name "ZZ.13.045") (class "Default")
      (node (ref "U$5") (pin "P$93") (pinfunction "D3_P$93") (pintype "bidirectional"))
    )
    (net (code "1309") (name "ZZ.13.046") (class "Default")
      (node (ref "U$7") (pin "P$119") (pinfunction "D29_P$119") (pintype "bidirectional"))
    )
    (net (code "1310") (name "ZZ.13.047") (class "Default")
      (node (ref "U$7") (pin "P$117") (pinfunction "D27_P$117") (pintype "bidirectional"))
    )
    (net (code "1311") (name "ZZ.13.048") (class "Default")
      (node (ref "U$7") (pin "P$179") (pinfunction "F29_P$179") (pintype "bidirectional"))
    )
    (net (code "1312") (name "ZZ.13.049") (class "Default")
      (node (ref "U$7") (pin "P$147") (pinfunction "E27_P$147") (pintype "bidirectional"))
    )
    (net (code "1313") (name "ZZ.13.050") (class "Default")
      (node (ref "U$7") (pin "P$50") (pinfunction "B20_P$50") (pintype "bidirectional"))
    )
    (net (code "1314") (name "ZZ.13.051") (class "Default")
      (node (ref "U$7") (pin "P$110") (pinfunction "D20_P$110") (pintype "bidirectional"))
    )
    (net (code "1315") (name "ZZ.13.052") (class "Default")
      (node (ref "U$7") (pin "P$47") (pinfunction "B17_P$47") (pintype "bidirectional"))
    )
    (net (code "1316") (name "ZZ.13.053") (class "Default")
      (node (ref "U$7") (pin "P$107") (pinfunction "D17_P$107") (pintype "bidirectional"))
    )
    (net (code "1317") (name "ZZ.13.054") (class "Default")
      (node (ref "U$7") (pin "P$43") (pinfunction "B13_P$43") (pintype "bidirectional"))
    )
    (net (code "1318") (name "ZZ.13.055") (class "Default")
      (node (ref "U$7") (pin "P$103") (pinfunction "D13_P$103") (pintype "bidirectional"))
    )
    (net (code "1319") (name "ZZ.13.056") (class "Default")
      (node (ref "U$7") (pin "P$40") (pinfunction "B10_P$40") (pintype "bidirectional"))
    )
    (net (code "1320") (name "ZZ.13.057") (class "Default")
      (node (ref "U$7") (pin "P$100") (pinfunction "D10_P$100") (pintype "bidirectional"))
    )
    (net (code "1321") (name "ZZ.13.058") (class "Default")
      (node (ref "U$7") (pin "P$36") (pinfunction "B6_P$36") (pintype "bidirectional"))
    )
    (net (code "1322") (name "ZZ.13.059") (class "Default")
      (node (ref "U$7") (pin "P$96") (pinfunction "D6_P$96") (pintype "bidirectional"))
    )
    (net (code "1323") (name "ZZ.13.060") (class "Default")
      (node (ref "U$7") (pin "P$33") (pinfunction "B3_P$33") (pintype "bidirectional"))
    )
    (net (code "1324") (name "ZZ.13.061") (class "Default")
      (node (ref "U$7") (pin "P$93") (pinfunction "D3_P$93") (pintype "bidirectional"))
    )
    (net (code "1325") (name "ZZ.13.062") (class "Default")
      (node (ref "U$9") (pin "P$119") (pinfunction "D29_P$119") (pintype "bidirectional"))
    )
    (net (code "1326") (name "ZZ.13.063") (class "Default")
      (node (ref "U$9") (pin "P$117") (pinfunction "D27_P$117") (pintype "bidirectional"))
    )
    (net (code "1327") (name "ZZ.13.064") (class "Default")
      (node (ref "U$9") (pin "P$179") (pinfunction "F29_P$179") (pintype "bidirectional"))
    )
    (net (code "1328") (name "ZZ.13.065") (class "Default")
      (node (ref "U$9") (pin "P$147") (pinfunction "E27_P$147") (pintype "bidirectional"))
    )
    (net (code "1329") (name "ZZ.13.066") (class "Default")
      (node (ref "U$9") (pin "P$50") (pinfunction "B20_P$50") (pintype "bidirectional"))
    )
    (net (code "1330") (name "ZZ.13.067") (class "Default")
      (node (ref "U$9") (pin "P$110") (pinfunction "D20_P$110") (pintype "bidirectional"))
    )
    (net (code "1331") (name "ZZ.13.068") (class "Default")
      (node (ref "U$9") (pin "P$47") (pinfunction "B17_P$47") (pintype "bidirectional"))
    )
    (net (code "1332") (name "ZZ.13.069") (class "Default")
      (node (ref "U$9") (pin "P$107") (pinfunction "D17_P$107") (pintype "bidirectional"))
    )
    (net (code "1333") (name "ZZ.13.070") (class "Default")
      (node (ref "U$9") (pin "P$43") (pinfunction "B13_P$43") (pintype "bidirectional"))
    )
    (net (code "1334") (name "ZZ.13.071") (class "Default")
      (node (ref "U$9") (pin "P$103") (pinfunction "D13_P$103") (pintype "bidirectional"))
    )
    (net (code "1335") (name "ZZ.13.072") (class "Default")
      (node (ref "U$9") (pin "P$40") (pinfunction "B10_P$40") (pintype "bidirectional"))
    )
    (net (code "1336") (name "ZZ.13.073") (class "Default")
      (node (ref "U$9") (pin "P$100") (pinfunction "D10_P$100") (pintype "bidirectional"))
    )
    (net (code "1337") (name "ZZ.13.074") (class "Default")
      (node (ref "U$9") (pin "P$36") (pinfunction "B6_P$36") (pintype "bidirectional"))
    )
    (net (code "1338") (name "ZZ.13.075") (class "Default")
      (node (ref "U$9") (pin "P$96") (pinfunction "D6_P$96") (pintype "bidirectional"))
    )
    (net (code "1339") (name "ZZ.13.076") (class "Default")
      (node (ref "U$9") (pin "P$33") (pinfunction "B3_P$33") (pintype "bidirectional"))
    )
    (net (code "1340") (name "ZZ.13.077") (class "Default")
      (node (ref "U$9") (pin "P$93") (pinfunction "D3_P$93") (pintype "bidirectional"))
    )
    (net (code "1341") (name "ZZ.13.078") (class "Default")
      (node (ref "U$11") (pin "P$58") (pinfunction "B28_P$58") (pintype "bidirectional"))
    )
    (net (code "1342") (name "ZZ.13.079") (class "Default")
      (node (ref "U$11") (pin "P$87") (pinfunction "C27_P$87") (pintype "bidirectional"))
    )
    (net (code "1343") (name "ZZ.13.080") (class "Default")
      (node (ref "U$11") (pin "P$55") (pinfunction "B25_P$55") (pintype "bidirectional"))
    )
    (net (code "1344") (name "ZZ.13.081") (class "Default")
      (node (ref "U$11") (pin "P$84") (pinfunction "C24_P$84") (pintype "bidirectional"))
    )
    (net (code "1345") (name "ZZ.13.082") (class "Default")
      (node (ref "U$11") (pin "P$51") (pinfunction "B21_P$51") (pintype "bidirectional"))
    )
    (net (code "1346") (name "ZZ.13.083") (class "Default")
      (node (ref "U$11") (pin "P$80") (pinfunction "C20_P$80") (pintype "bidirectional"))
    )
    (net (code "1347") (name "ZZ.13.084") (class "Default")
      (node (ref "U$11") (pin "P$48") (pinfunction "B18_P$48") (pintype "bidirectional"))
    )
    (net (code "1348") (name "ZZ.13.085") (class "Default")
      (node (ref "U$11") (pin "P$77") (pinfunction "C17_P$77") (pintype "bidirectional"))
    )
    (net (code "1349") (name "ZZ.13.086") (class "Default")
      (node (ref "U$11") (pin "P$44") (pinfunction "B14_P$44") (pintype "bidirectional"))
    )
    (net (code "1350") (name "ZZ.13.087") (class "Default")
      (node (ref "U$11") (pin "P$73") (pinfunction "C13_P$73") (pintype "bidirectional"))
    )
    (net (code "1351") (name "ZZ.13.088") (class "Default")
      (node (ref "U$11") (pin "P$41") (pinfunction "B11_P$41") (pintype "bidirectional"))
    )
    (net (code "1352") (name "ZZ.13.089") (class "Default")
      (node (ref "U$11") (pin "P$70") (pinfunction "C10_P$70") (pintype "bidirectional"))
    )
    (net (code "1353") (name "ZZ.13.090") (class "Default")
      (node (ref "U$11") (pin "P$37") (pinfunction "B7_P$37") (pintype "bidirectional"))
    )
    (net (code "1354") (name "ZZ.13.091") (class "Default")
      (node (ref "U$11") (pin "P$66") (pinfunction "C6_P$66") (pintype "bidirectional"))
    )
    (net (code "1355") (name "ZZ.13.092") (class "Default")
      (node (ref "U$11") (pin "P$34") (pinfunction "B4_P$34") (pintype "bidirectional"))
    )
    (net (code "1356") (name "ZZ.13.093") (class "Default")
      (node (ref "U$11") (pin "P$63") (pinfunction "C3_P$63") (pintype "bidirectional"))
    )
    (net (code "1357") (name "ZZ.14.000") (class "Default")
      (node (ref "U$1") (pin "P$152") (pinfunction "F2_P$152") (pintype "bidirectional"))
    )
    (net (code "1358") (name "ZZ.14.001") (class "Default")
      (node (ref "U$1") (pin "P$128") (pinfunction "E8_P$128") (pintype "bidirectional"))
    )
    (net (code "1359") (name "ZZ.14.002") (class "Default")
      (node (ref "U$1") (pin "P$129") (pinfunction "E9_P$129") (pintype "bidirectional"))
    )
    (net (code "1360") (name "ZZ.14.003") (class "Default")
      (node (ref "U$1") (pin "P$132") (pinfunction "E12_P$132") (pintype "bidirectional"))
    )
    (net (code "1361") (name "ZZ.14.004") (class "Default")
      (node (ref "U$1") (pin "P$159") (pinfunction "F9_P$159") (pintype "bidirectional"))
    )
    (net (code "1362") (name "ZZ.14.005") (class "Default")
      (node (ref "U$1") (pin "P$135") (pinfunction "E15_P$135") (pintype "bidirectional"))
    )
    (net (code "1363") (name "ZZ.14.006") (class "Default")
      (node (ref "U$1") (pin "P$136") (pinfunction "E16_P$136") (pintype "bidirectional"))
    )
    (net (code "1364") (name "ZZ.14.007") (class "Default")
      (node (ref "U$1") (pin "P$139") (pinfunction "E19_P$139") (pintype "bidirectional"))
    )
    (net (code "1365") (name "ZZ.14.008") (class "Default")
      (node (ref "U$1") (pin "P$166") (pinfunction "F16_P$166") (pintype "bidirectional"))
    )
    (net (code "1366") (name "ZZ.14.009") (class "Default")
      (node (ref "U$1") (pin "P$142") (pinfunction "E22_P$142") (pintype "bidirectional"))
    )
    (net (code "1367") (name "ZZ.14.010") (class "Default")
      (node (ref "U$1") (pin "P$143") (pinfunction "E23_P$143") (pintype "bidirectional"))
    )
    (net (code "1368") (name "ZZ.14.011") (class "Default")
      (node (ref "U$1") (pin "P$146") (pinfunction "E26_P$146") (pintype "bidirectional"))
    )
    (net (code "1369") (name "ZZ.14.012") (class "Default")
      (node (ref "U$1") (pin "P$173") (pinfunction "F23_P$173") (pintype "bidirectional"))
    )
    (net (code "1370") (name "ZZ.14.013") (class "Default")
      (node (ref "U$1") (pin "P$149") (pinfunction "E29_P$149") (pintype "bidirectional"))
    )
    (net (code "1371") (name "ZZ.14.014") (class "Default")
      (node (ref "U$3") (pin "P$34") (pinfunction "B4_P$34") (pintype "bidirectional"))
    )
    (net (code "1372") (name "ZZ.14.015") (class "Default")
      (node (ref "U$3") (pin "P$94") (pinfunction "D4_P$94") (pintype "bidirectional"))
    )
    (net (code "1373") (name "ZZ.14.016") (class "Default")
      (node (ref "U$3") (pin "P$37") (pinfunction "B7_P$37") (pintype "bidirectional"))
    )
    (net (code "1374") (name "ZZ.14.017") (class "Default")
      (node (ref "U$3") (pin "P$97") (pinfunction "D7_P$97") (pintype "bidirectional"))
    )
    (net (code "1375") (name "ZZ.14.018") (class "Default")
      (node (ref "U$3") (pin "P$41") (pinfunction "B11_P$41") (pintype "bidirectional"))
    )
    (net (code "1376") (name "ZZ.14.019") (class "Default")
      (node (ref "U$3") (pin "P$101") (pinfunction "D11_P$101") (pintype "bidirectional"))
    )
    (net (code "1377") (name "ZZ.14.020") (class "Default")
      (node (ref "U$3") (pin "P$44") (pinfunction "B14_P$44") (pintype "bidirectional"))
    )
    (net (code "1378") (name "ZZ.14.021") (class "Default")
      (node (ref "U$3") (pin "P$104") (pinfunction "D14_P$104") (pintype "bidirectional"))
    )
    (net (code "1379") (name "ZZ.14.022") (class "Default")
      (node (ref "U$3") (pin "P$48") (pinfunction "B18_P$48") (pintype "bidirectional"))
    )
    (net (code "1380") (name "ZZ.14.023") (class "Default")
      (node (ref "U$3") (pin "P$108") (pinfunction "D18_P$108") (pintype "bidirectional"))
    )
    (net (code "1381") (name "ZZ.14.024") (class "Default")
      (node (ref "U$3") (pin "P$51") (pinfunction "B21_P$51") (pintype "bidirectional"))
    )
    (net (code "1382") (name "ZZ.14.025") (class "Default")
      (node (ref "U$3") (pin "P$111") (pinfunction "D21_P$111") (pintype "bidirectional"))
    )
    (net (code "1383") (name "ZZ.14.026") (class "Default")
      (node (ref "U$3") (pin "P$89") (pinfunction "C29_P$89") (pintype "bidirectional"))
    )
    (net (code "1384") (name "ZZ.14.027") (class "Default")
      (node (ref "U$3") (pin "P$87") (pinfunction "C27_P$87") (pintype "bidirectional"))
    )
    (net (code "1385") (name "ZZ.14.028") (class "Default")
      (node (ref "U$3") (pin "P$149") (pinfunction "E29_P$149") (pintype "bidirectional"))
    )
    (net (code "1386") (name "ZZ.14.029") (class "Default")
      (node (ref "U$3") (pin "P$176") (pinfunction "F26_P$176") (pintype "bidirectional"))
    )
    (net (code "1387") (name "ZZ.14.030") (class "Default")
      (node (ref "U$5") (pin "P$44") (pinfunction "B14_P$44") (pintype "bidirectional"))
    )
    (net (code "1388") (name "ZZ.14.031") (class "Default")
      (node (ref "U$5") (pin "P$104") (pinfunction "D14_P$104") (pintype "bidirectional"))
    )
    (net (code "1389") (name "ZZ.14.032") (class "Default")
      (node (ref "U$5") (pin "P$48") (pinfunction "B18_P$48") (pintype "bidirectional"))
    )
    (net (code "1390") (name "ZZ.14.033") (class "Default")
      (node (ref "U$5") (pin "P$108") (pinfunction "D18_P$108") (pintype "bidirectional"))
    )
    (net (code "1391") (name "ZZ.14.034") (class "Default")
      (node (ref "U$5") (pin "P$51") (pinfunction "B21_P$51") (pintype "bidirectional"))
    )
    (net (code "1392") (name "ZZ.14.035") (class "Default")
      (node (ref "U$5") (pin "P$111") (pinfunction "D21_P$111") (pintype "bidirectional"))
    )
    (net (code "1393") (name "ZZ.14.036") (class "Default")
      (node (ref "U$5") (pin "P$55") (pinfunction "B25_P$55") (pintype "bidirectional"))
    )
    (net (code "1394") (name "ZZ.14.037") (class "Default")
      (node (ref "U$5") (pin "P$115") (pinfunction "D25_P$115") (pintype "bidirectional"))
    )
    (net (code "1395") (name "ZZ.14.038") (class "Default")
      (node (ref "U$5") (pin "P$58") (pinfunction "B28_P$58") (pintype "bidirectional"))
    )
    (net (code "1396") (name "ZZ.14.039") (class "Default")
      (node (ref "U$5") (pin "P$118") (pinfunction "D28_P$118") (pintype "bidirectional"))
    )
    (net (code "1397") (name "ZZ.14.040") (class "Default")
      (node (ref "U$5") (pin "P$41") (pinfunction "B11_P$41") (pintype "bidirectional"))
    )
    (net (code "1398") (name "ZZ.14.041") (class "Default")
      (node (ref "U$5") (pin "P$101") (pinfunction "D11_P$101") (pintype "bidirectional"))
    )
    (net (code "1399") (name "ZZ.14.042") (class "Default")
      (node (ref "U$5") (pin "P$37") (pinfunction "B7_P$37") (pintype "bidirectional"))
    )
    (net (code "1400") (name "ZZ.14.043") (class "Default")
      (node (ref "U$5") (pin "P$97") (pinfunction "D7_P$97") (pintype "bidirectional"))
    )
    (net (code "1401") (name "ZZ.14.044") (class "Default")
      (node (ref "U$5") (pin "P$34") (pinfunction "B4_P$34") (pintype "bidirectional"))
    )
    (net (code "1402") (name "ZZ.14.045") (class "Default")
      (node (ref "U$5") (pin "P$94") (pinfunction "D4_P$94") (pintype "bidirectional"))
    )
    (net (code "1403") (name "ZZ.14.046") (class "Default")
      (node (ref "U$7") (pin "P$89") (pinfunction "C29_P$89") (pintype "bidirectional"))
    )
    (net (code "1404") (name "ZZ.14.047") (class "Default")
      (node (ref "U$7") (pin "P$87") (pinfunction "C27_P$87") (pintype "bidirectional"))
    )
    (net (code "1405") (name "ZZ.14.048") (class "Default")
      (node (ref "U$7") (pin "P$149") (pinfunction "E29_P$149") (pintype "bidirectional"))
    )
    (net (code "1406") (name "ZZ.14.049") (class "Default")
      (node (ref "U$7") (pin "P$176") (pinfunction "F26_P$176") (pintype "bidirectional"))
    )
    (net (code "1407") (name "ZZ.14.050") (class "Default")
      (node (ref "U$7") (pin "P$51") (pinfunction "B21_P$51") (pintype "bidirectional"))
    )
    (net (code "1408") (name "ZZ.14.051") (class "Default")
      (node (ref "U$7") (pin "P$111") (pinfunction "D21_P$111") (pintype "bidirectional"))
    )
    (net (code "1409") (name "ZZ.14.052") (class "Default")
      (node (ref "U$7") (pin "P$48") (pinfunction "B18_P$48") (pintype "bidirectional"))
    )
    (net (code "1410") (name "ZZ.14.053") (class "Default")
      (node (ref "U$7") (pin "P$108") (pinfunction "D18_P$108") (pintype "bidirectional"))
    )
    (net (code "1411") (name "ZZ.14.054") (class "Default")
      (node (ref "U$7") (pin "P$44") (pinfunction "B14_P$44") (pintype "bidirectional"))
    )
    (net (code "1412") (name "ZZ.14.055") (class "Default")
      (node (ref "U$7") (pin "P$104") (pinfunction "D14_P$104") (pintype "bidirectional"))
    )
    (net (code "1413") (name "ZZ.14.056") (class "Default")
      (node (ref "U$7") (pin "P$41") (pinfunction "B11_P$41") (pintype "bidirectional"))
    )
    (net (code "1414") (name "ZZ.14.057") (class "Default")
      (node (ref "U$7") (pin "P$101") (pinfunction "D11_P$101") (pintype "bidirectional"))
    )
    (net (code "1415") (name "ZZ.14.058") (class "Default")
      (node (ref "U$7") (pin "P$37") (pinfunction "B7_P$37") (pintype "bidirectional"))
    )
    (net (code "1416") (name "ZZ.14.059") (class "Default")
      (node (ref "U$7") (pin "P$97") (pinfunction "D7_P$97") (pintype "bidirectional"))
    )
    (net (code "1417") (name "ZZ.14.060") (class "Default")
      (node (ref "U$7") (pin "P$34") (pinfunction "B4_P$34") (pintype "bidirectional"))
    )
    (net (code "1418") (name "ZZ.14.061") (class "Default")
      (node (ref "U$7") (pin "P$94") (pinfunction "D4_P$94") (pintype "bidirectional"))
    )
    (net (code "1419") (name "ZZ.14.062") (class "Default")
      (node (ref "U$9") (pin "P$89") (pinfunction "C29_P$89") (pintype "bidirectional"))
    )
    (net (code "1420") (name "ZZ.14.063") (class "Default")
      (node (ref "U$9") (pin "P$87") (pinfunction "C27_P$87") (pintype "bidirectional"))
    )
    (net (code "1421") (name "ZZ.14.064") (class "Default")
      (node (ref "U$9") (pin "P$149") (pinfunction "E29_P$149") (pintype "bidirectional"))
    )
    (net (code "1422") (name "ZZ.14.065") (class "Default")
      (node (ref "U$9") (pin "P$176") (pinfunction "F26_P$176") (pintype "bidirectional"))
    )
    (net (code "1423") (name "ZZ.14.066") (class "Default")
      (node (ref "U$9") (pin "P$51") (pinfunction "B21_P$51") (pintype "bidirectional"))
    )
    (net (code "1424") (name "ZZ.14.067") (class "Default")
      (node (ref "U$9") (pin "P$111") (pinfunction "D21_P$111") (pintype "bidirectional"))
    )
    (net (code "1425") (name "ZZ.14.068") (class "Default")
      (node (ref "U$9") (pin "P$48") (pinfunction "B18_P$48") (pintype "bidirectional"))
    )
    (net (code "1426") (name "ZZ.14.069") (class "Default")
      (node (ref "U$9") (pin "P$108") (pinfunction "D18_P$108") (pintype "bidirectional"))
    )
    (net (code "1427") (name "ZZ.14.070") (class "Default")
      (node (ref "U$9") (pin "P$44") (pinfunction "B14_P$44") (pintype "bidirectional"))
    )
    (net (code "1428") (name "ZZ.14.071") (class "Default")
      (node (ref "U$9") (pin "P$104") (pinfunction "D14_P$104") (pintype "bidirectional"))
    )
    (net (code "1429") (name "ZZ.14.072") (class "Default")
      (node (ref "U$9") (pin "P$41") (pinfunction "B11_P$41") (pintype "bidirectional"))
    )
    (net (code "1430") (name "ZZ.14.073") (class "Default")
      (node (ref "U$9") (pin "P$101") (pinfunction "D11_P$101") (pintype "bidirectional"))
    )
    (net (code "1431") (name "ZZ.14.074") (class "Default")
      (node (ref "U$9") (pin "P$37") (pinfunction "B7_P$37") (pintype "bidirectional"))
    )
    (net (code "1432") (name "ZZ.14.075") (class "Default")
      (node (ref "U$9") (pin "P$97") (pinfunction "D7_P$97") (pintype "bidirectional"))
    )
    (net (code "1433") (name "ZZ.14.076") (class "Default")
      (node (ref "U$9") (pin "P$34") (pinfunction "B4_P$34") (pintype "bidirectional"))
    )
    (net (code "1434") (name "ZZ.14.077") (class "Default")
      (node (ref "U$9") (pin "P$94") (pinfunction "D4_P$94") (pintype "bidirectional"))
    )
    (net (code "1435") (name "ZZ.14.078") (class "Default")
      (node (ref "U$11") (pin "P$89") (pinfunction "C29_P$89") (pintype "bidirectional"))
    )
    (net (code "1436") (name "ZZ.14.079") (class "Default")
      (node (ref "U$11") (pin "P$57") (pinfunction "B27_P$57") (pintype "bidirectional"))
    )
    (net (code "1437") (name "ZZ.14.080") (class "Default")
      (node (ref "U$11") (pin "P$86") (pinfunction "C26_P$86") (pintype "bidirectional"))
    )
    (net (code "1438") (name "ZZ.14.081") (class "Default")
      (node (ref "U$11") (pin "P$54") (pinfunction "B24_P$54") (pintype "bidirectional"))
    )
    (net (code "1439") (name "ZZ.14.082") (class "Default")
      (node (ref "U$11") (pin "P$82") (pinfunction "C22_P$82") (pintype "bidirectional"))
    )
    (net (code "1440") (name "ZZ.14.083") (class "Default")
      (node (ref "U$11") (pin "P$50") (pinfunction "B20_P$50") (pintype "bidirectional"))
    )
    (net (code "1441") (name "ZZ.14.084") (class "Default")
      (node (ref "U$11") (pin "P$79") (pinfunction "C19_P$79") (pintype "bidirectional"))
    )
    (net (code "1442") (name "ZZ.14.085") (class "Default")
      (node (ref "U$11") (pin "P$47") (pinfunction "B17_P$47") (pintype "bidirectional"))
    )
    (net (code "1443") (name "ZZ.14.086") (class "Default")
      (node (ref "U$11") (pin "P$75") (pinfunction "C15_P$75") (pintype "bidirectional"))
    )
    (net (code "1444") (name "ZZ.14.087") (class "Default")
      (node (ref "U$11") (pin "P$43") (pinfunction "B13_P$43") (pintype "bidirectional"))
    )
    (net (code "1445") (name "ZZ.14.088") (class "Default")
      (node (ref "U$11") (pin "P$72") (pinfunction "C12_P$72") (pintype "bidirectional"))
    )
    (net (code "1446") (name "ZZ.14.089") (class "Default")
      (node (ref "U$11") (pin "P$40") (pinfunction "B10_P$40") (pintype "bidirectional"))
    )
    (net (code "1447") (name "ZZ.14.090") (class "Default")
      (node (ref "U$11") (pin "P$68") (pinfunction "C8_P$68") (pintype "bidirectional"))
    )
    (net (code "1448") (name "ZZ.14.091") (class "Default")
      (node (ref "U$11") (pin "P$36") (pinfunction "B6_P$36") (pintype "bidirectional"))
    )
    (net (code "1449") (name "ZZ.14.092") (class "Default")
      (node (ref "U$11") (pin "P$65") (pinfunction "C5_P$65") (pintype "bidirectional"))
    )
    (net (code "1450") (name "ZZ.14.093") (class "Default")
      (node (ref "U$11") (pin "P$33") (pinfunction "B3_P$33") (pintype "bidirectional"))
    )
    (net (code "1451") (name "ZZ.15.000") (class "Default")
      (node (ref "U$1") (pin "P$156") (pinfunction "F6_P$156") (pintype "bidirectional"))
    )
    (net (code "1452") (name "ZZ.15.001") (class "Default")
      (node (ref "U$1") (pin "P$157") (pinfunction "F7_P$157") (pintype "bidirectional"))
    )
    (net (code "1453") (name "ZZ.15.002") (class "Default")
      (node (ref "U$1") (pin "P$160") (pinfunction "F10_P$160") (pintype "bidirectional"))
    )
    (net (code "1454") (name "ZZ.15.003") (class "Default")
      (node (ref "U$1") (pin "P$161") (pinfunction "F11_P$161") (pintype "bidirectional"))
    )
    (net (code "1455") (name "ZZ.15.004") (class "Default")
      (node (ref "U$1") (pin "P$163") (pinfunction "F13_P$163") (pintype "bidirectional"))
    )
    (net (code "1456") (name "ZZ.15.005") (class "Default")
      (node (ref "U$1") (pin "P$164") (pinfunction "F14_P$164") (pintype "bidirectional"))
    )
    (net (code "1457") (name "ZZ.15.006") (class "Default")
      (node (ref "U$1") (pin "P$167") (pinfunction "F17_P$167") (pintype "bidirectional"))
    )
    (net (code "1458") (name "ZZ.15.007") (class "Default")
      (node (ref "U$1") (pin "P$168") (pinfunction "F18_P$168") (pintype "bidirectional"))
    )
    (net (code "1459") (name "ZZ.15.008") (class "Default")
      (node (ref "U$1") (pin "P$170") (pinfunction "F20_P$170") (pintype "bidirectional"))
    )
    (net (code "1460") (name "ZZ.15.009") (class "Default")
      (node (ref "U$1") (pin "P$171") (pinfunction "F21_P$171") (pintype "bidirectional"))
    )
    (net (code "1461") (name "ZZ.15.010") (class "Default")
      (node (ref "U$1") (pin "P$174") (pinfunction "F24_P$174") (pintype "bidirectional"))
    )
    (net (code "1462") (name "ZZ.15.011") (class "Default")
      (node (ref "U$1") (pin "P$175") (pinfunction "F25_P$175") (pintype "bidirectional"))
    )
    (net (code "1463") (name "ZZ.15.012") (class "Default")
      (node (ref "U$1") (pin "P$177") (pinfunction "F27_P$177") (pintype "bidirectional"))
    )
    (net (code "1464") (name "ZZ.15.013") (class "Default")
      (node (ref "U$1") (pin "P$178") (pinfunction "F28_P$178") (pintype "bidirectional"))
    )
    (net (code "1465") (name "ZZ.15.014") (class "Default")
      (node (ref "U$3") (pin "P$33") (pinfunction "B3_P$33") (pintype "bidirectional"))
    )
    (net (code "1466") (name "ZZ.15.015") (class "Default")
      (node (ref "U$3") (pin "P$93") (pinfunction "D3_P$93") (pintype "bidirectional"))
    )
    (net (code "1467") (name "ZZ.15.016") (class "Default")
      (node (ref "U$3") (pin "P$36") (pinfunction "B6_P$36") (pintype "bidirectional"))
    )
    (net (code "1468") (name "ZZ.15.017") (class "Default")
      (node (ref "U$3") (pin "P$96") (pinfunction "D6_P$96") (pintype "bidirectional"))
    )
    (net (code "1469") (name "ZZ.15.018") (class "Default")
      (node (ref "U$3") (pin "P$40") (pinfunction "B10_P$40") (pintype "bidirectional"))
    )
    (net (code "1470") (name "ZZ.15.019") (class "Default")
      (node (ref "U$3") (pin "P$100") (pinfunction "D10_P$100") (pintype "bidirectional"))
    )
    (net (code "1471") (name "ZZ.15.020") (class "Default")
      (node (ref "U$3") (pin "P$43") (pinfunction "B13_P$43") (pintype "bidirectional"))
    )
    (net (code "1472") (name "ZZ.15.021") (class "Default")
      (node (ref "U$3") (pin "P$103") (pinfunction "D13_P$103") (pintype "bidirectional"))
    )
    (net (code "1473") (name "ZZ.15.022") (class "Default")
      (node (ref "U$3") (pin "P$47") (pinfunction "B17_P$47") (pintype "bidirectional"))
    )
    (net (code "1474") (name "ZZ.15.023") (class "Default")
      (node (ref "U$3") (pin "P$107") (pinfunction "D17_P$107") (pintype "bidirectional"))
    )
    (net (code "1475") (name "ZZ.15.024") (class "Default")
      (node (ref "U$3") (pin "P$50") (pinfunction "B20_P$50") (pintype "bidirectional"))
    )
    (net (code "1476") (name "ZZ.15.025") (class "Default")
      (node (ref "U$3") (pin "P$110") (pinfunction "D20_P$110") (pintype "bidirectional"))
    )
    (net (code "1477") (name "ZZ.15.026") (class "Default")
      (node (ref "U$3") (pin "P$59") (pinfunction "B29_P$59") (pintype "bidirectional"))
    )
    (net (code "1478") (name "ZZ.15.027") (class "Default")
      (node (ref "U$3") (pin "P$57") (pinfunction "B27_P$57") (pintype "bidirectional"))
    )
    (net (code "1479") (name "ZZ.15.028") (class "Default")
      (node (ref "U$3") (pin "P$178") (pinfunction "F28_P$178") (pintype "bidirectional"))
    )
    (net (code "1480") (name "ZZ.15.029") (class "Default")
      (node (ref "U$3") (pin "P$146") (pinfunction "E26_P$146") (pintype "bidirectional"))
    )
    (net (code "1481") (name "ZZ.15.030") (class "Default")
      (node (ref "U$5") (pin "P$43") (pinfunction "B13_P$43") (pintype "bidirectional"))
    )
    (net (code "1482") (name "ZZ.15.031") (class "Default")
      (node (ref "U$5") (pin "P$103") (pinfunction "D13_P$103") (pintype "bidirectional"))
    )
    (net (code "1483") (name "ZZ.15.032") (class "Default")
      (node (ref "U$5") (pin "P$47") (pinfunction "B17_P$47") (pintype "bidirectional"))
    )
    (net (code "1484") (name "ZZ.15.033") (class "Default")
      (node (ref "U$5") (pin "P$107") (pinfunction "D17_P$107") (pintype "bidirectional"))
    )
    (net (code "1485") (name "ZZ.15.034") (class "Default")
      (node (ref "U$5") (pin "P$50") (pinfunction "B20_P$50") (pintype "bidirectional"))
    )
    (net (code "1486") (name "ZZ.15.035") (class "Default")
      (node (ref "U$5") (pin "P$110") (pinfunction "D20_P$110") (pintype "bidirectional"))
    )
    (net (code "1487") (name "ZZ.15.036") (class "Default")
      (node (ref "U$5") (pin "P$54") (pinfunction "B24_P$54") (pintype "bidirectional"))
    )
    (net (code "1488") (name "ZZ.15.037") (class "Default")
      (node (ref "U$5") (pin "P$114") (pinfunction "D24_P$114") (pintype "bidirectional"))
    )
    (net (code "1489") (name "ZZ.15.038") (class "Default")
      (node (ref "U$5") (pin "P$57") (pinfunction "B27_P$57") (pintype "bidirectional"))
    )
    (net (code "1490") (name "ZZ.15.039") (class "Default")
      (node (ref "U$5") (pin "P$117") (pinfunction "D27_P$117") (pintype "bidirectional"))
    )
    (net (code "1491") (name "ZZ.15.040") (class "Default")
      (node (ref "U$5") (pin "P$42") (pinfunction "B12_P$42") (pintype "bidirectional"))
    )
    (net (code "1492") (name "ZZ.15.041") (class "Default")
      (node (ref "U$5") (pin "P$102") (pinfunction "D12_P$102") (pintype "bidirectional"))
    )
    (net (code "1493") (name "ZZ.15.042") (class "Default")
      (node (ref "U$5") (pin "P$38") (pinfunction "B8_P$38") (pintype "bidirectional"))
    )
    (net (code "1494") (name "ZZ.15.043") (class "Default")
      (node (ref "U$5") (pin "P$98") (pinfunction "D8_P$98") (pintype "bidirectional"))
    )
    (net (code "1495") (name "ZZ.15.044") (class "Default")
      (node (ref "U$5") (pin "P$35") (pinfunction "B5_P$35") (pintype "bidirectional"))
    )
    (net (code "1496") (name "ZZ.15.045") (class "Default")
      (node (ref "U$5") (pin "P$95") (pinfunction "D5_P$95") (pintype "bidirectional"))
    )
    (net (code "1497") (name "ZZ.15.046") (class "Default")
      (node (ref "U$7") (pin "P$59") (pinfunction "B29_P$59") (pintype "bidirectional"))
    )
    (net (code "1498") (name "ZZ.15.047") (class "Default")
      (node (ref "U$7") (pin "P$57") (pinfunction "B27_P$57") (pintype "bidirectional"))
    )
    (net (code "1499") (name "ZZ.15.048") (class "Default")
      (node (ref "U$7") (pin "P$178") (pinfunction "F28_P$178") (pintype "bidirectional"))
    )
    (net (code "1500") (name "ZZ.15.049") (class "Default")
      (node (ref "U$7") (pin "P$146") (pinfunction "E26_P$146") (pintype "bidirectional"))
    )
    (net (code "1501") (name "ZZ.15.050") (class "Default")
      (node (ref "U$7") (pin "P$52") (pinfunction "B22_P$52") (pintype "bidirectional"))
    )
    (net (code "1502") (name "ZZ.15.051") (class "Default")
      (node (ref "U$7") (pin "P$112") (pinfunction "D22_P$112") (pintype "bidirectional"))
    )
    (net (code "1503") (name "ZZ.15.052") (class "Default")
      (node (ref "U$7") (pin "P$49") (pinfunction "B19_P$49") (pintype "bidirectional"))
    )
    (net (code "1504") (name "ZZ.15.053") (class "Default")
      (node (ref "U$7") (pin "P$109") (pinfunction "D19_P$109") (pintype "bidirectional"))
    )
    (net (code "1505") (name "ZZ.15.054") (class "Default")
      (node (ref "U$7") (pin "P$45") (pinfunction "B15_P$45") (pintype "bidirectional"))
    )
    (net (code "1506") (name "ZZ.15.055") (class "Default")
      (node (ref "U$7") (pin "P$105") (pinfunction "D15_P$105") (pintype "bidirectional"))
    )
    (net (code "1507") (name "ZZ.15.056") (class "Default")
      (node (ref "U$7") (pin "P$42") (pinfunction "B12_P$42") (pintype "bidirectional"))
    )
    (net (code "1508") (name "ZZ.15.057") (class "Default")
      (node (ref "U$7") (pin "P$102") (pinfunction "D12_P$102") (pintype "bidirectional"))
    )
    (net (code "1509") (name "ZZ.15.058") (class "Default")
      (node (ref "U$7") (pin "P$38") (pinfunction "B8_P$38") (pintype "bidirectional"))
    )
    (net (code "1510") (name "ZZ.15.059") (class "Default")
      (node (ref "U$7") (pin "P$98") (pinfunction "D8_P$98") (pintype "bidirectional"))
    )
    (net (code "1511") (name "ZZ.15.060") (class "Default")
      (node (ref "U$7") (pin "P$35") (pinfunction "B5_P$35") (pintype "bidirectional"))
    )
    (net (code "1512") (name "ZZ.15.061") (class "Default")
      (node (ref "U$7") (pin "P$95") (pinfunction "D5_P$95") (pintype "bidirectional"))
    )
    (net (code "1513") (name "ZZ.15.062") (class "Default")
      (node (ref "U$9") (pin "P$59") (pinfunction "B29_P$59") (pintype "bidirectional"))
    )
    (net (code "1514") (name "ZZ.15.063") (class "Default")
      (node (ref "U$9") (pin "P$57") (pinfunction "B27_P$57") (pintype "bidirectional"))
    )
    (net (code "1515") (name "ZZ.15.064") (class "Default")
      (node (ref "U$9") (pin "P$178") (pinfunction "F28_P$178") (pintype "bidirectional"))
    )
    (net (code "1516") (name "ZZ.15.065") (class "Default")
      (node (ref "U$9") (pin "P$146") (pinfunction "E26_P$146") (pintype "bidirectional"))
    )
    (net (code "1517") (name "ZZ.15.066") (class "Default")
      (node (ref "U$9") (pin "P$52") (pinfunction "B22_P$52") (pintype "bidirectional"))
    )
    (net (code "1518") (name "ZZ.15.067") (class "Default")
      (node (ref "U$9") (pin "P$112") (pinfunction "D22_P$112") (pintype "bidirectional"))
    )
    (net (code "1519") (name "ZZ.15.068") (class "Default")
      (node (ref "U$9") (pin "P$49") (pinfunction "B19_P$49") (pintype "bidirectional"))
    )
    (net (code "1520") (name "ZZ.15.069") (class "Default")
      (node (ref "U$9") (pin "P$109") (pinfunction "D19_P$109") (pintype "bidirectional"))
    )
    (net (code "1521") (name "ZZ.15.070") (class "Default")
      (node (ref "U$9") (pin "P$45") (pinfunction "B15_P$45") (pintype "bidirectional"))
    )
    (net (code "1522") (name "ZZ.15.071") (class "Default")
      (node (ref "U$9") (pin "P$105") (pinfunction "D15_P$105") (pintype "bidirectional"))
    )
    (net (code "1523") (name "ZZ.15.072") (class "Default")
      (node (ref "U$9") (pin "P$42") (pinfunction "B12_P$42") (pintype "bidirectional"))
    )
    (net (code "1524") (name "ZZ.15.073") (class "Default")
      (node (ref "U$9") (pin "P$102") (pinfunction "D12_P$102") (pintype "bidirectional"))
    )
    (net (code "1525") (name "ZZ.15.074") (class "Default")
      (node (ref "U$9") (pin "P$38") (pinfunction "B8_P$38") (pintype "bidirectional"))
    )
    (net (code "1526") (name "ZZ.15.075") (class "Default")
      (node (ref "U$9") (pin "P$98") (pinfunction "D8_P$98") (pintype "bidirectional"))
    )
    (net (code "1527") (name "ZZ.15.076") (class "Default")
      (node (ref "U$9") (pin "P$35") (pinfunction "B5_P$35") (pintype "bidirectional"))
    )
    (net (code "1528") (name "ZZ.15.077") (class "Default")
      (node (ref "U$9") (pin "P$95") (pinfunction "D5_P$95") (pintype "bidirectional"))
    )
    (net (code "1529") (name "ZZ.15.078") (class "Default")
      (node (ref "U$11") (pin "P$59") (pinfunction "B29_P$59") (pintype "bidirectional"))
    )
    (net (code "1530") (name "ZZ.15.079") (class "Default")
      (node (ref "U$11") (pin "P$88") (pinfunction "C28_P$88") (pintype "bidirectional"))
    )
    (net (code "1531") (name "ZZ.15.080") (class "Default")
      (node (ref "U$11") (pin "P$56") (pinfunction "B26_P$56") (pintype "bidirectional"))
    )
    (net (code "1532") (name "ZZ.15.081") (class "Default")
      (node (ref "U$11") (pin "P$85") (pinfunction "C25_P$85") (pintype "bidirectional"))
    )
    (net (code "1533") (name "ZZ.15.082") (class "Default")
      (node (ref "U$11") (pin "P$52") (pinfunction "B22_P$52") (pintype "bidirectional"))
    )
    (net (code "1534") (name "ZZ.15.083") (class "Default")
      (node (ref "U$11") (pin "P$81") (pinfunction "C21_P$81") (pintype "bidirectional"))
    )
    (net (code "1535") (name "ZZ.15.084") (class "Default")
      (node (ref "U$11") (pin "P$49") (pinfunction "B19_P$49") (pintype "bidirectional"))
    )
    (net (code "1536") (name "ZZ.15.085") (class "Default")
      (node (ref "U$11") (pin "P$78") (pinfunction "C18_P$78") (pintype "bidirectional"))
    )
    (net (code "1537") (name "ZZ.15.086") (class "Default")
      (node (ref "U$11") (pin "P$45") (pinfunction "B15_P$45") (pintype "bidirectional"))
    )
    (net (code "1538") (name "ZZ.15.087") (class "Default")
      (node (ref "U$11") (pin "P$74") (pinfunction "C14_P$74") (pintype "bidirectional"))
    )
    (net (code "1539") (name "ZZ.15.088") (class "Default")
      (node (ref "U$11") (pin "P$42") (pinfunction "B12_P$42") (pintype "bidirectional"))
    )
    (net (code "1540") (name "ZZ.15.089") (class "Default")
      (node (ref "U$11") (pin "P$71") (pinfunction "C11_P$71") (pintype "bidirectional"))
    )
    (net (code "1541") (name "ZZ.15.090") (class "Default")
      (node (ref "U$11") (pin "P$38") (pinfunction "B8_P$38") (pintype "bidirectional"))
    )
    (net (code "1542") (name "ZZ.15.091") (class "Default")
      (node (ref "U$11") (pin "P$67") (pinfunction "C7_P$67") (pintype "bidirectional"))
    )
    (net (code "1543") (name "ZZ.15.092") (class "Default")
      (node (ref "U$11") (pin "P$35") (pinfunction "B5_P$35") (pintype "bidirectional"))
    )
    (net (code "1544") (name "ZZ.15.093") (class "Default")
      (node (ref "U$11") (pin "P$64") (pinfunction "C4_P$64") (pintype "bidirectional"))
    )
    (net (code "1545") (name "unconnected-(U$2-A30-PadP$30)") (class "Default")
      (node (ref "U$2") (pin "P$30") (pinfunction "A30_P$30") (pintype "bidirectional"))
    )
    (net (code "1546") (name "unconnected-(U$4-A30-PadP$30)") (class "Default")
      (node (ref "U$4") (pin "P$30") (pinfunction "A30_P$30") (pintype "bidirectional"))
    )
    (net (code "1547") (name "unconnected-(U$6-A30-PadP$30)") (class "Default")
      (node (ref "U$6") (pin "P$30") (pinfunction "A30_P$30") (pintype "bidirectional"))
    )
    (net (code "1548") (name "unconnected-(U$8-A30-PadP$30)") (class "Default")
      (node (ref "U$8") (pin "P$30") (pinfunction "A30_P$30") (pintype "bidirectional"))
    )
    (net (code "1549") (name "unconnected-(U$10-A30-PadP$30)") (class "Default")
      (node (ref "U$10") (pin "P$30") (pinfunction "A30_P$30") (pintype "bidirectional"))
    )
    (net (code "1550") (name "unconnected-(U$12-A30-PadP$30)") (class "Default")
      (node (ref "U$12") (pin "P$30") (pinfunction "A30_P$30") (pintype "bidirectional"))
    )
  )
)
